# quantum_AnalougeEngine_V5_0.net
KiCad netlist of a schematic drawn in EAGLE
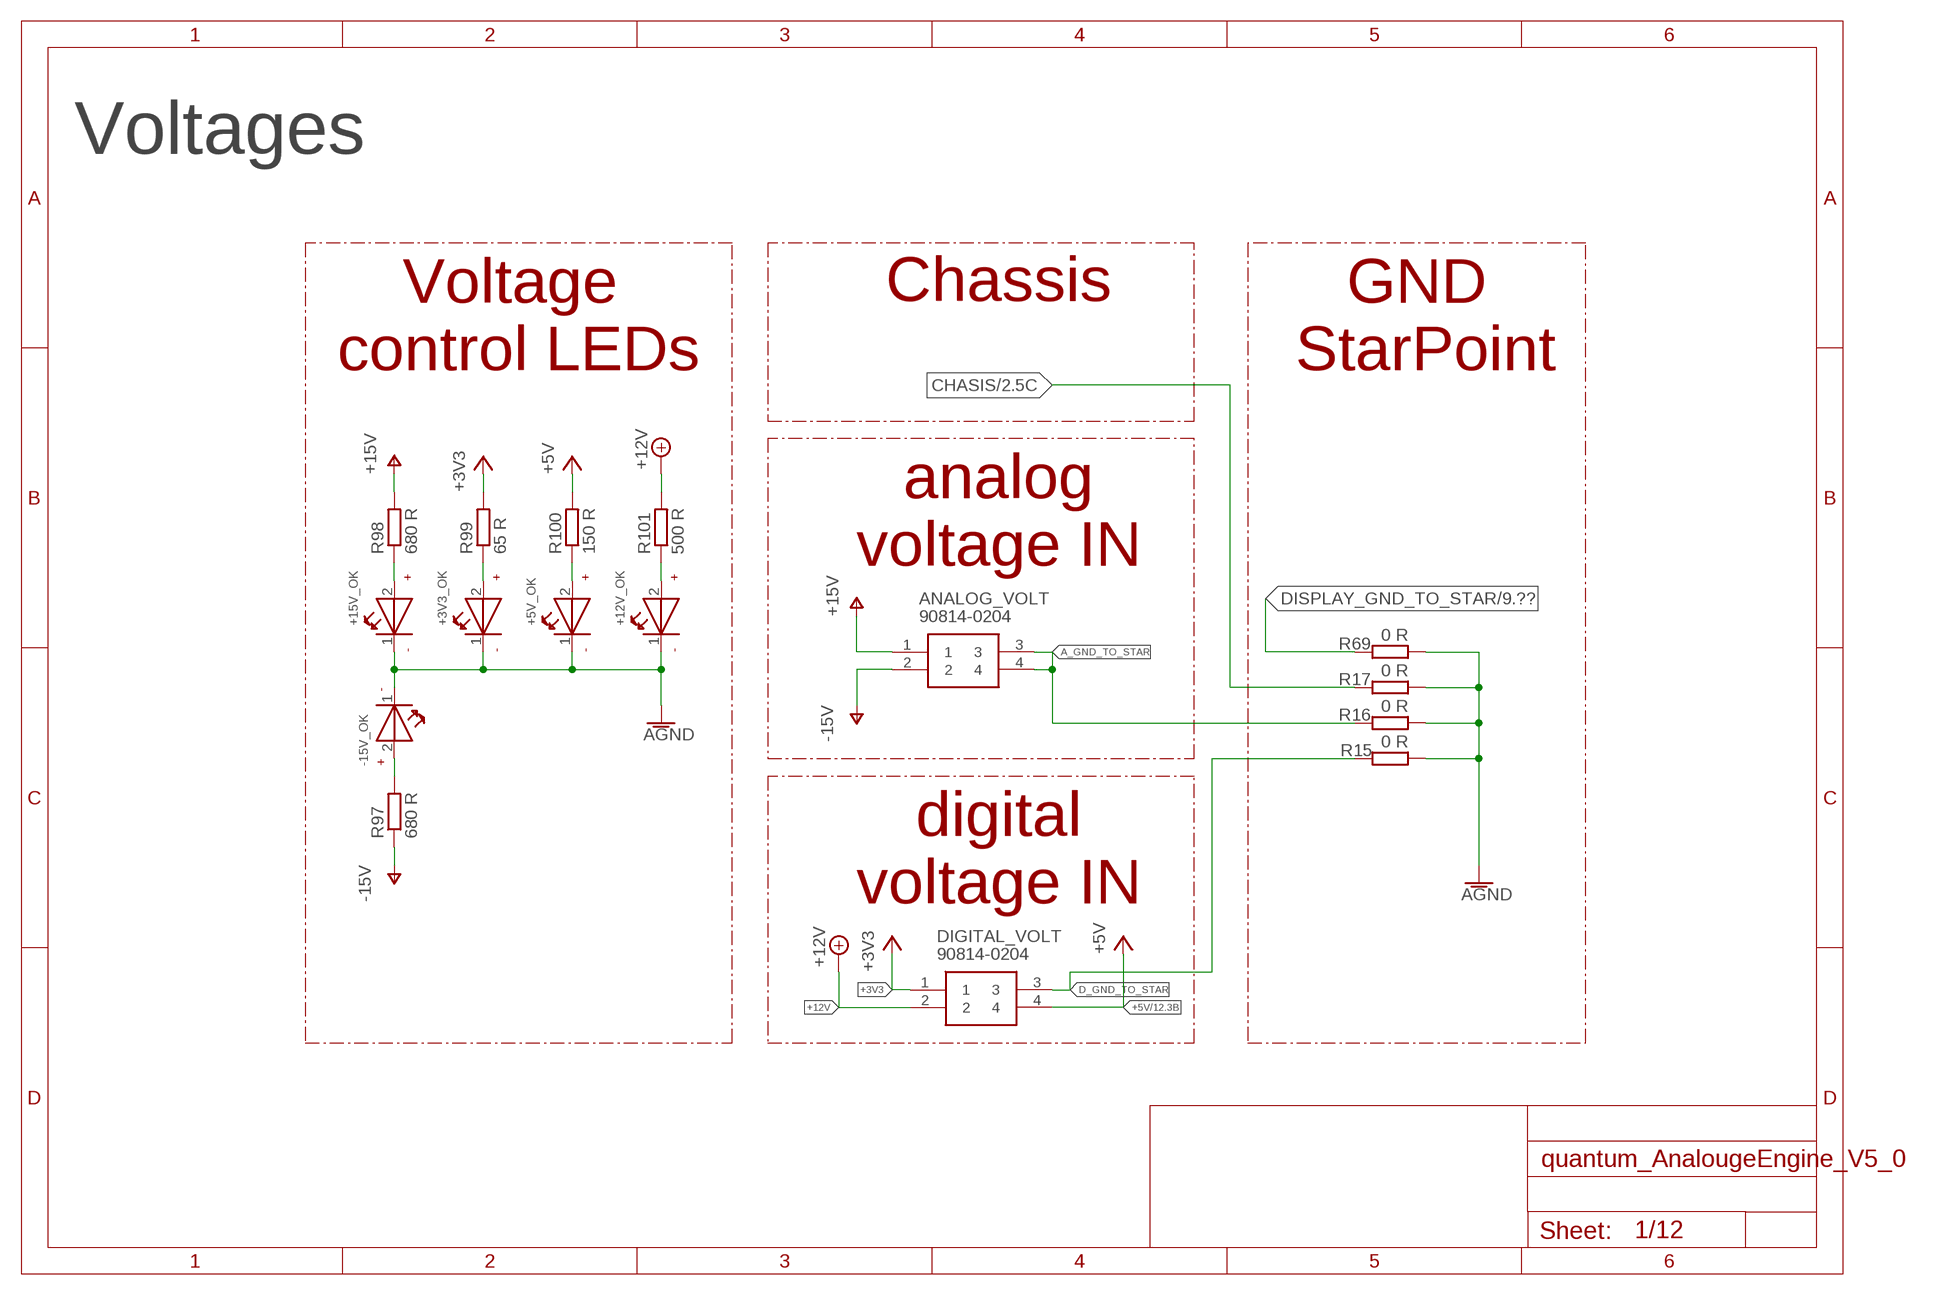
[diagram p0: schematic, sheet 1]
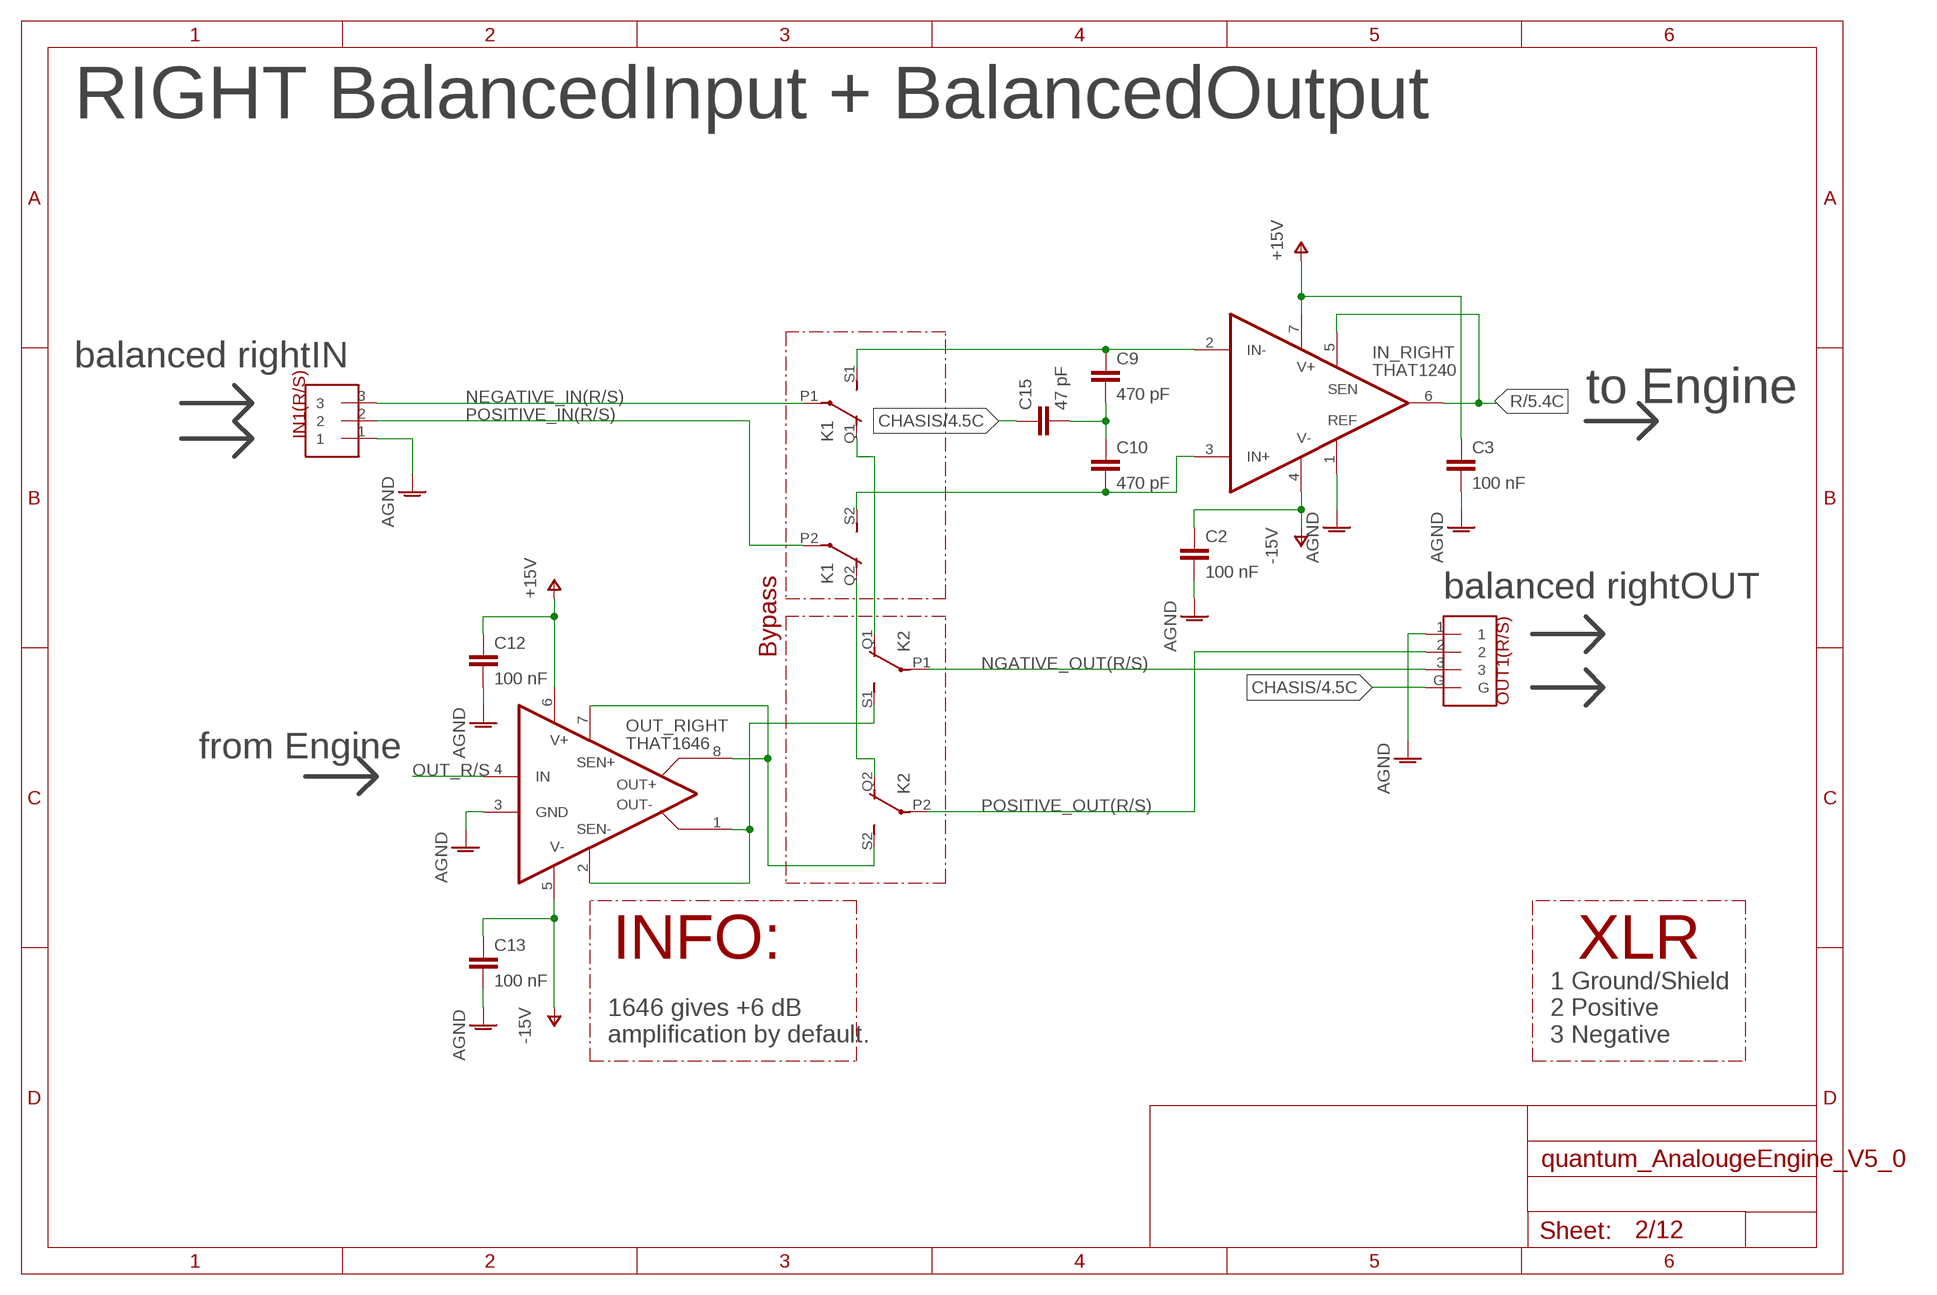
[diagram p1: schematic, sheet 2]
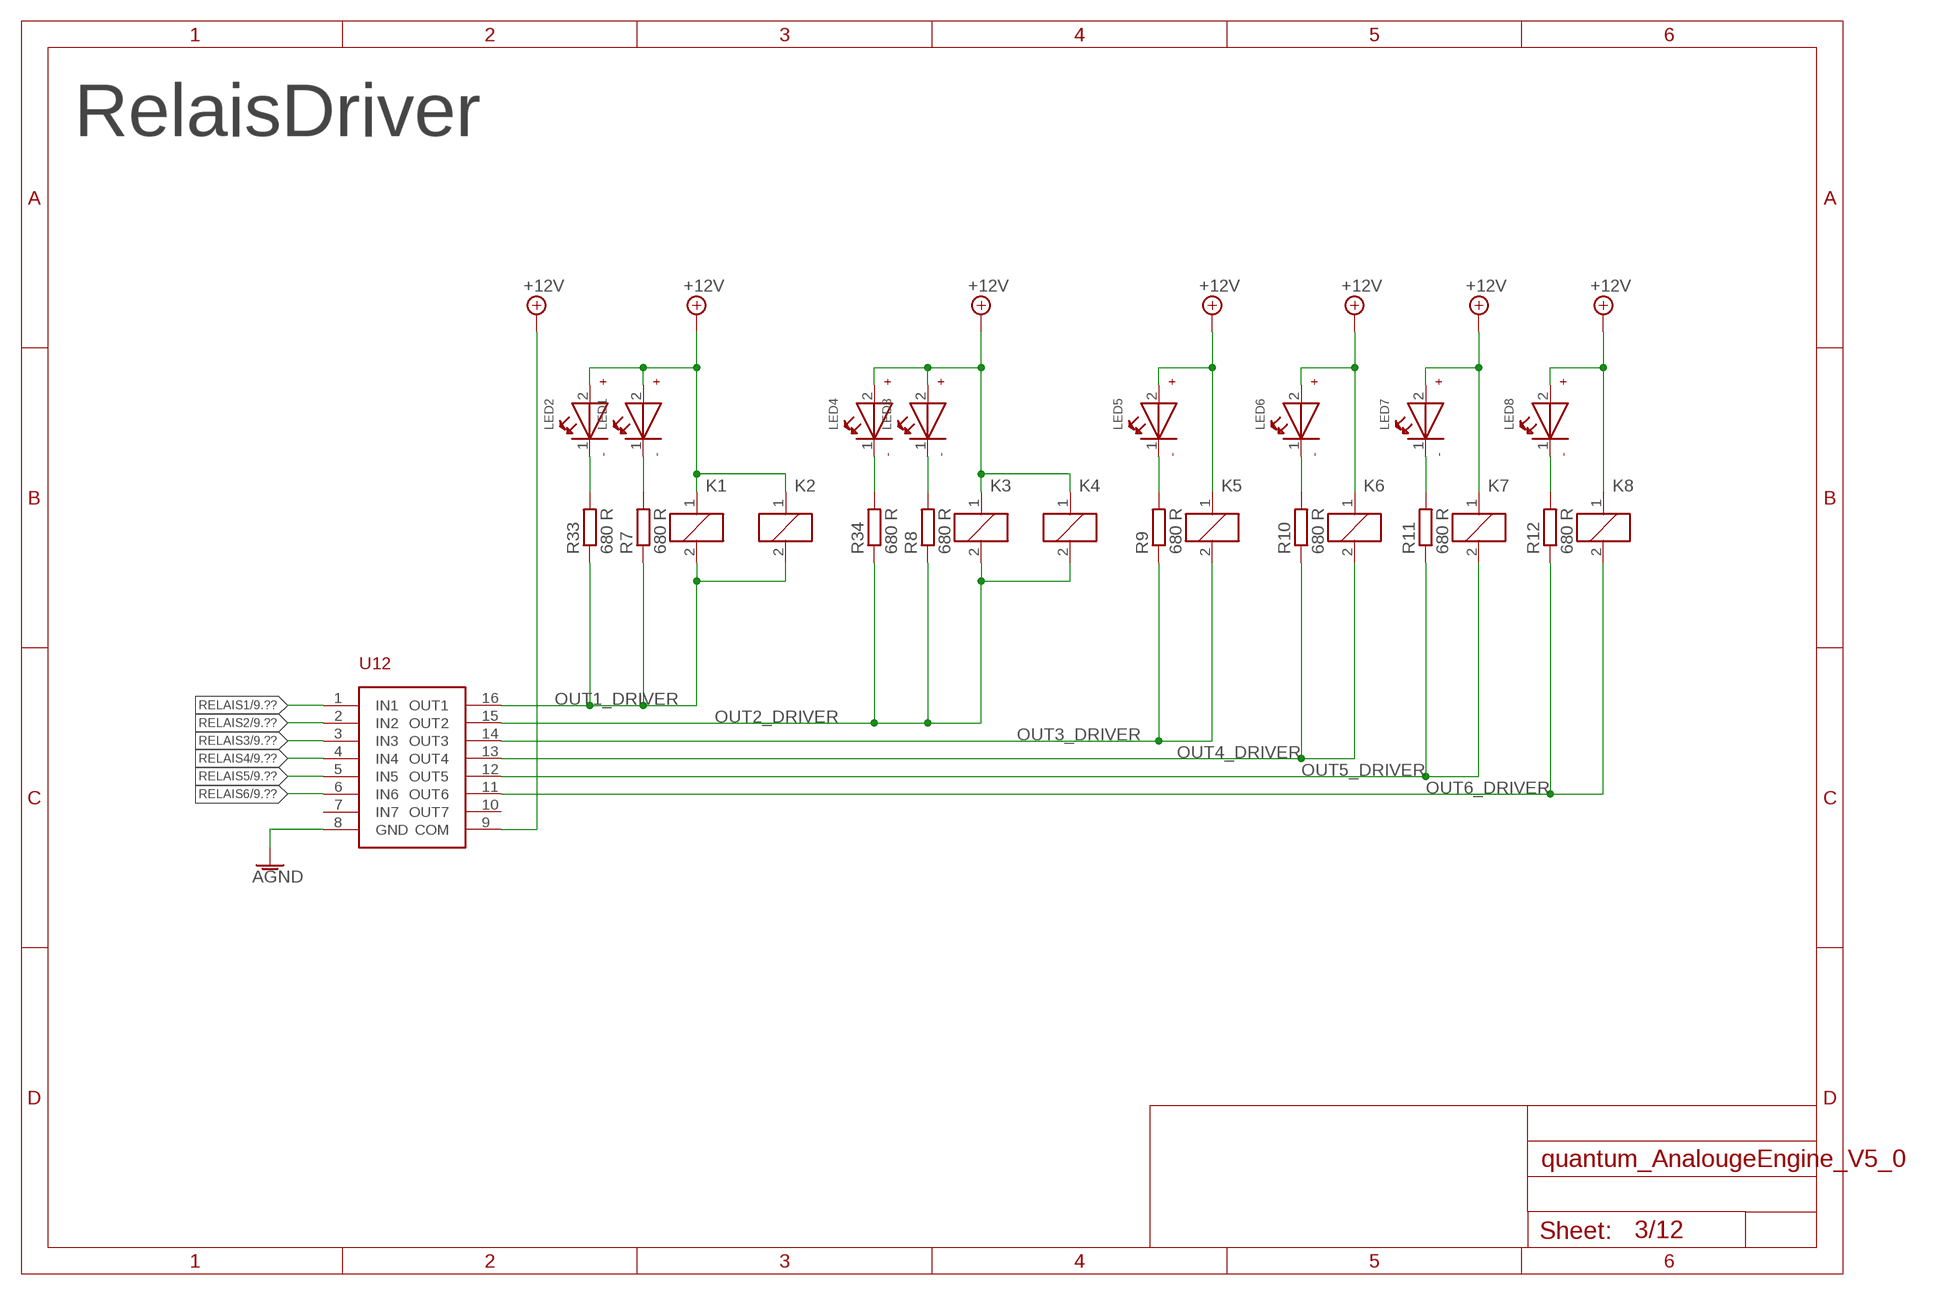
[diagram p2: schematic, sheet 3]
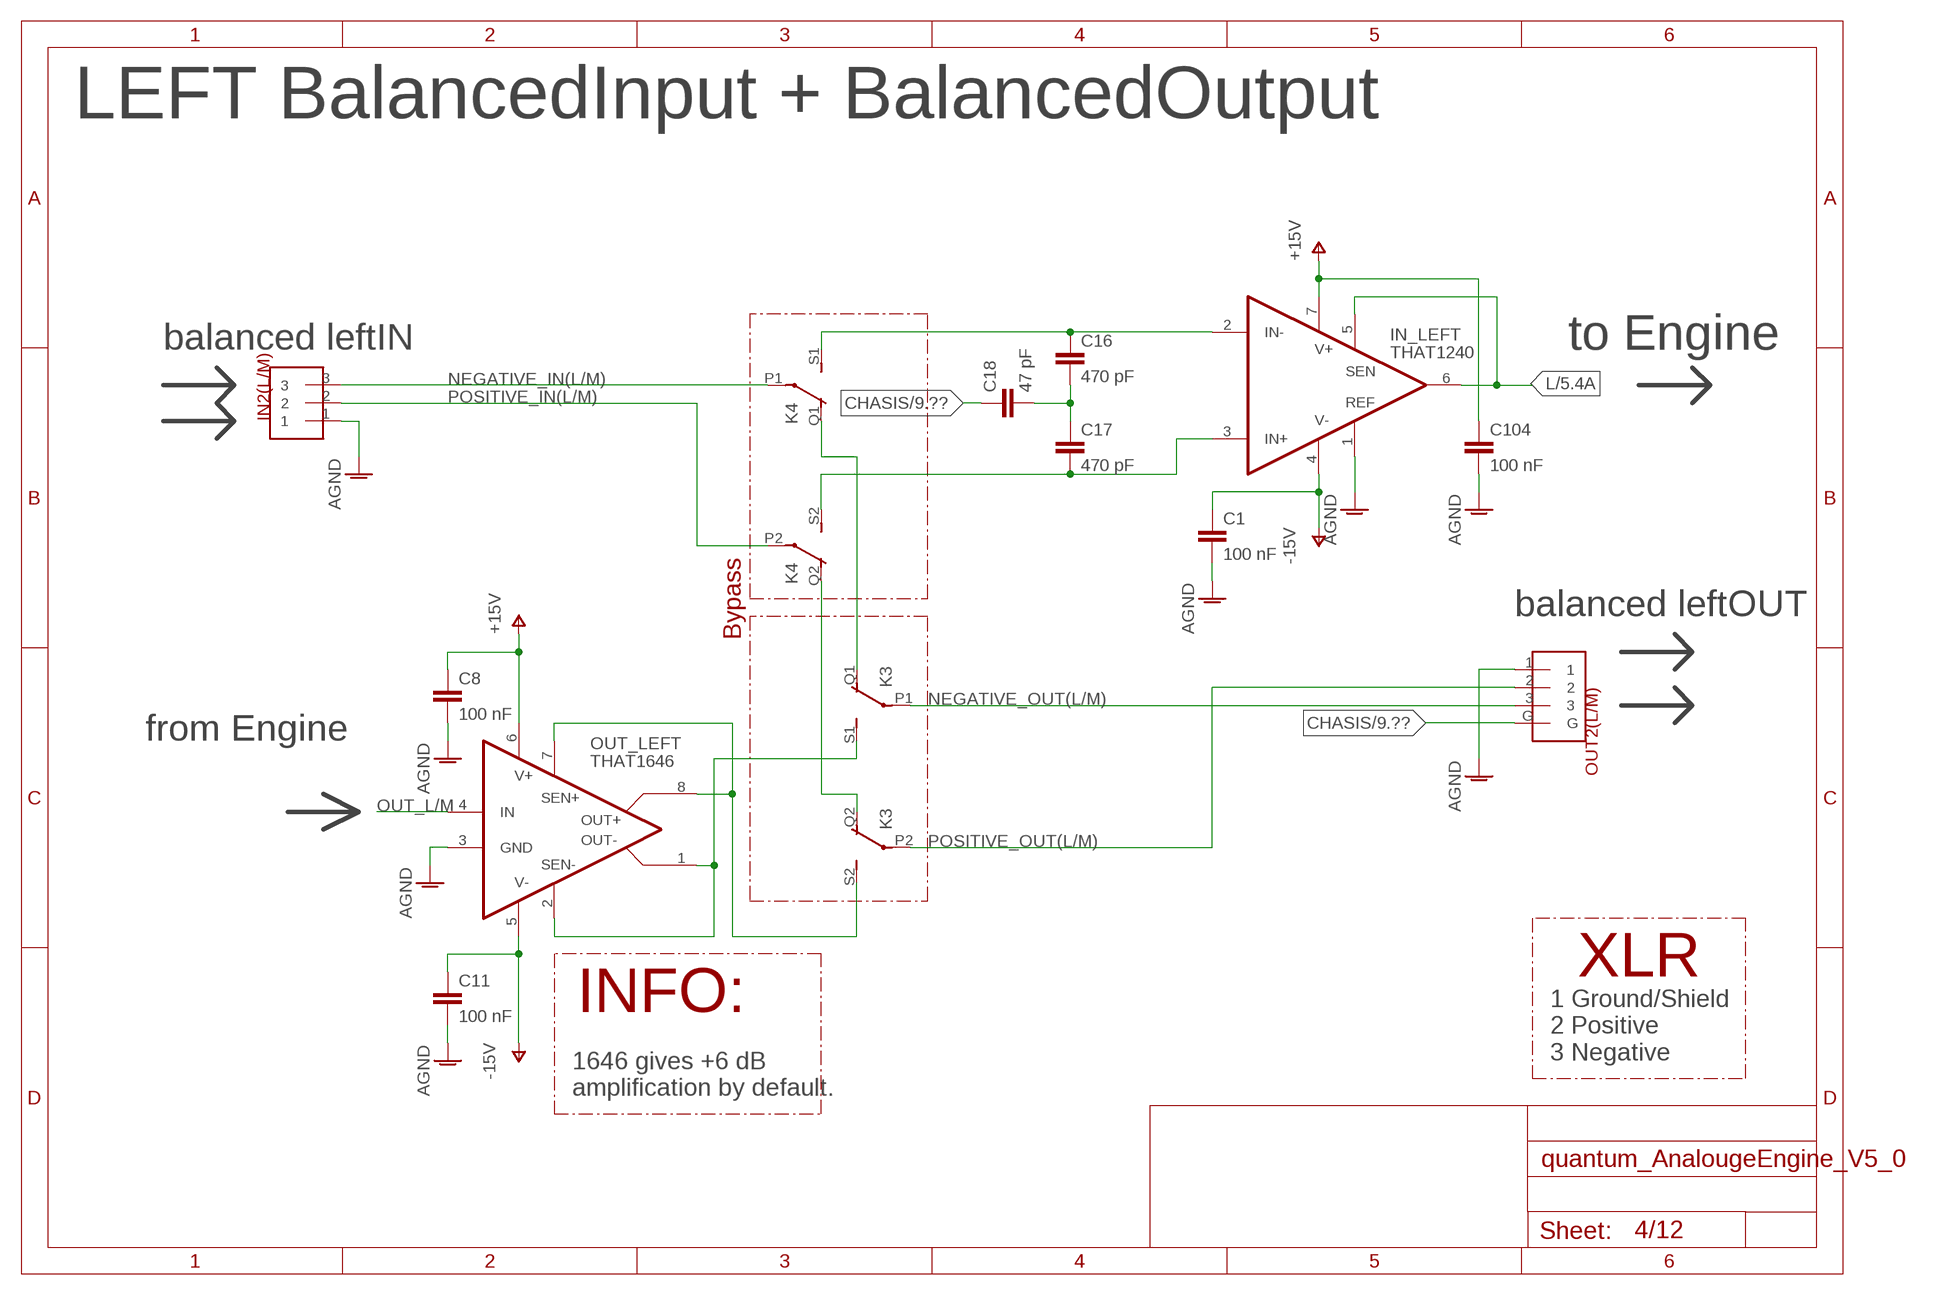
[diagram p3: schematic, sheet 4]
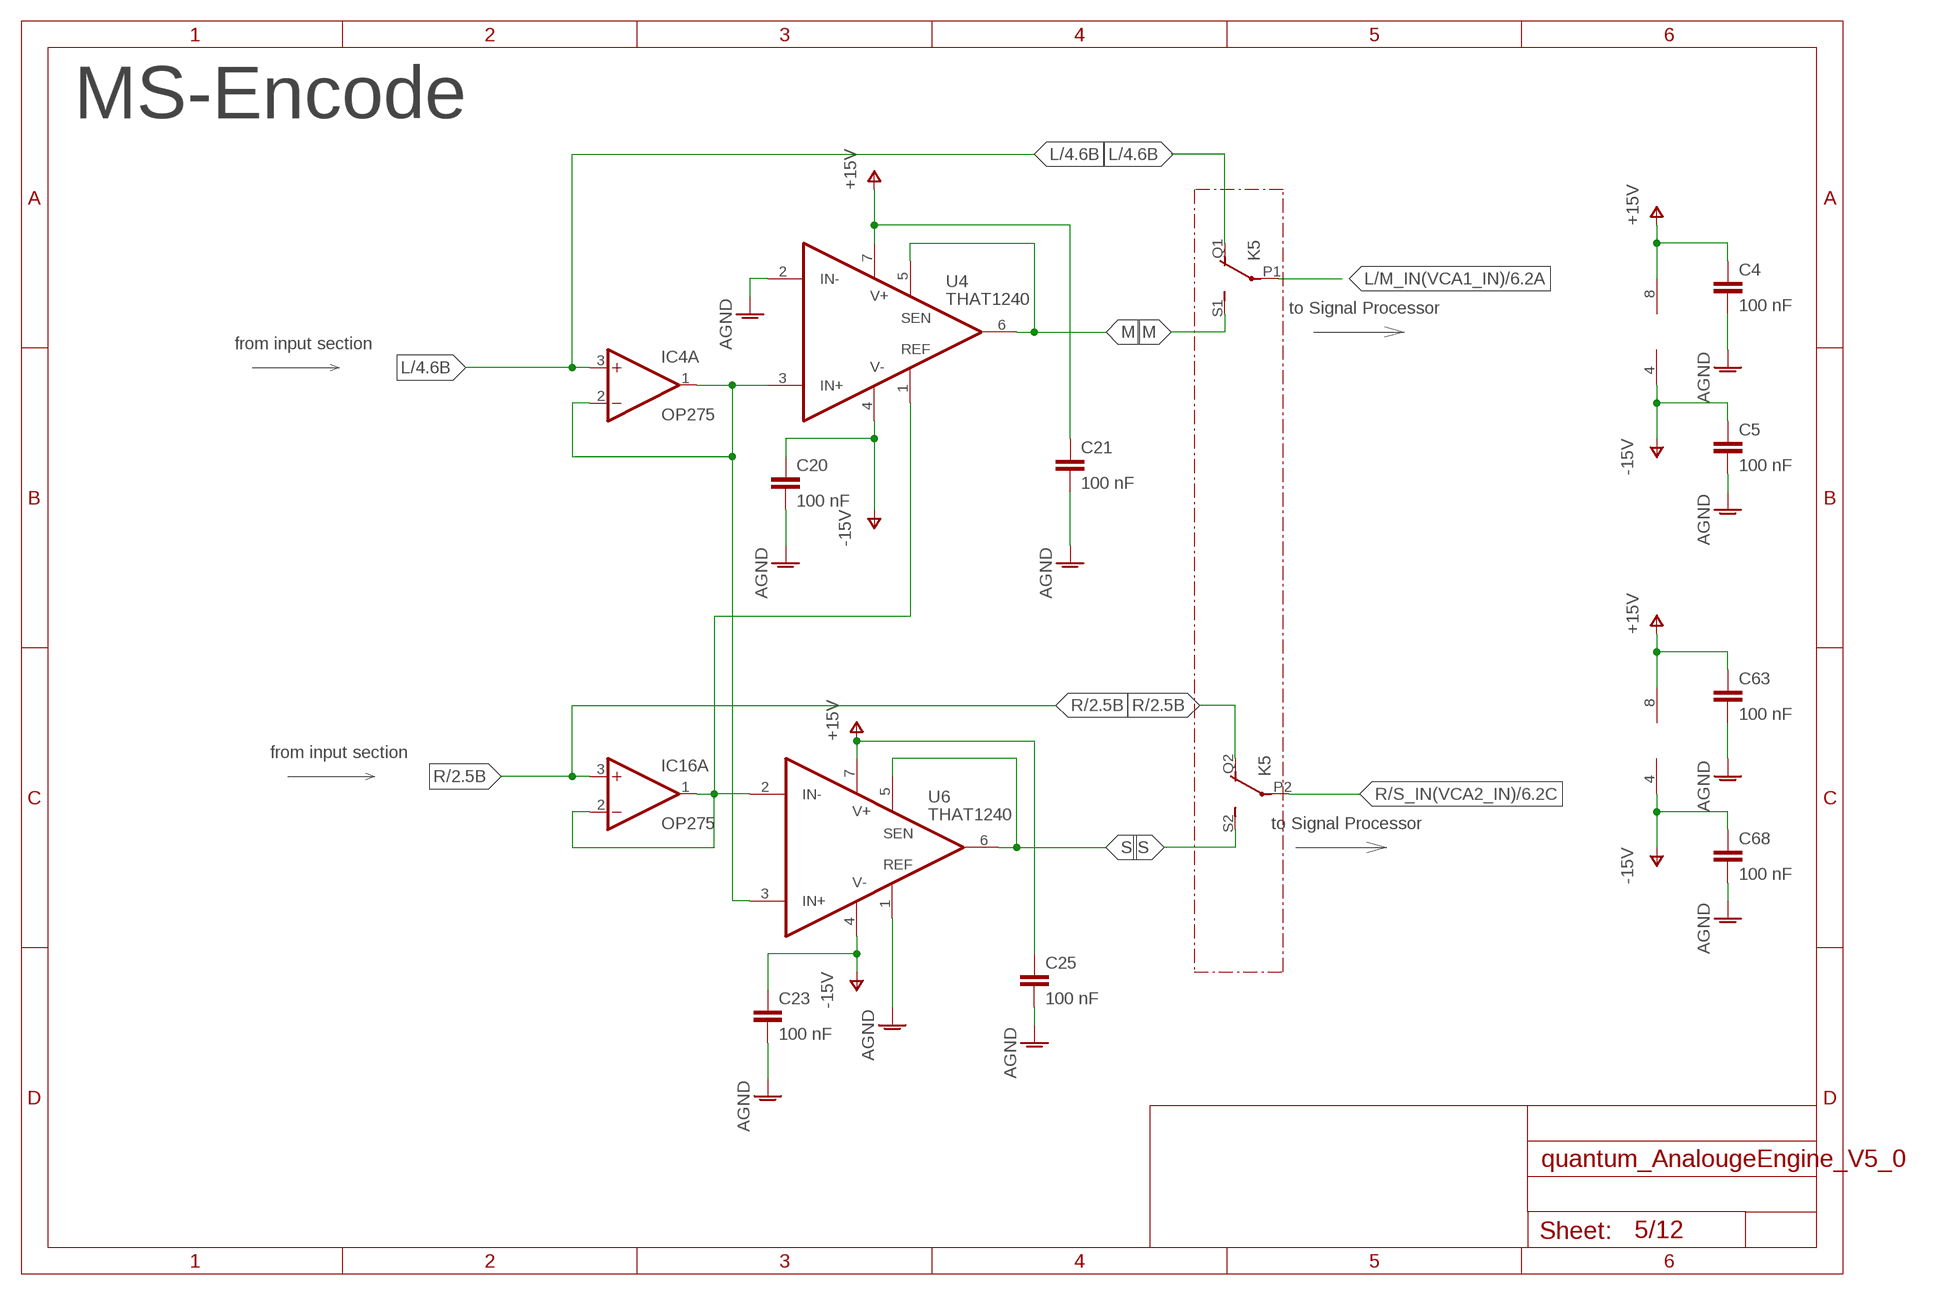
[diagram p4: schematic, sheet 5]
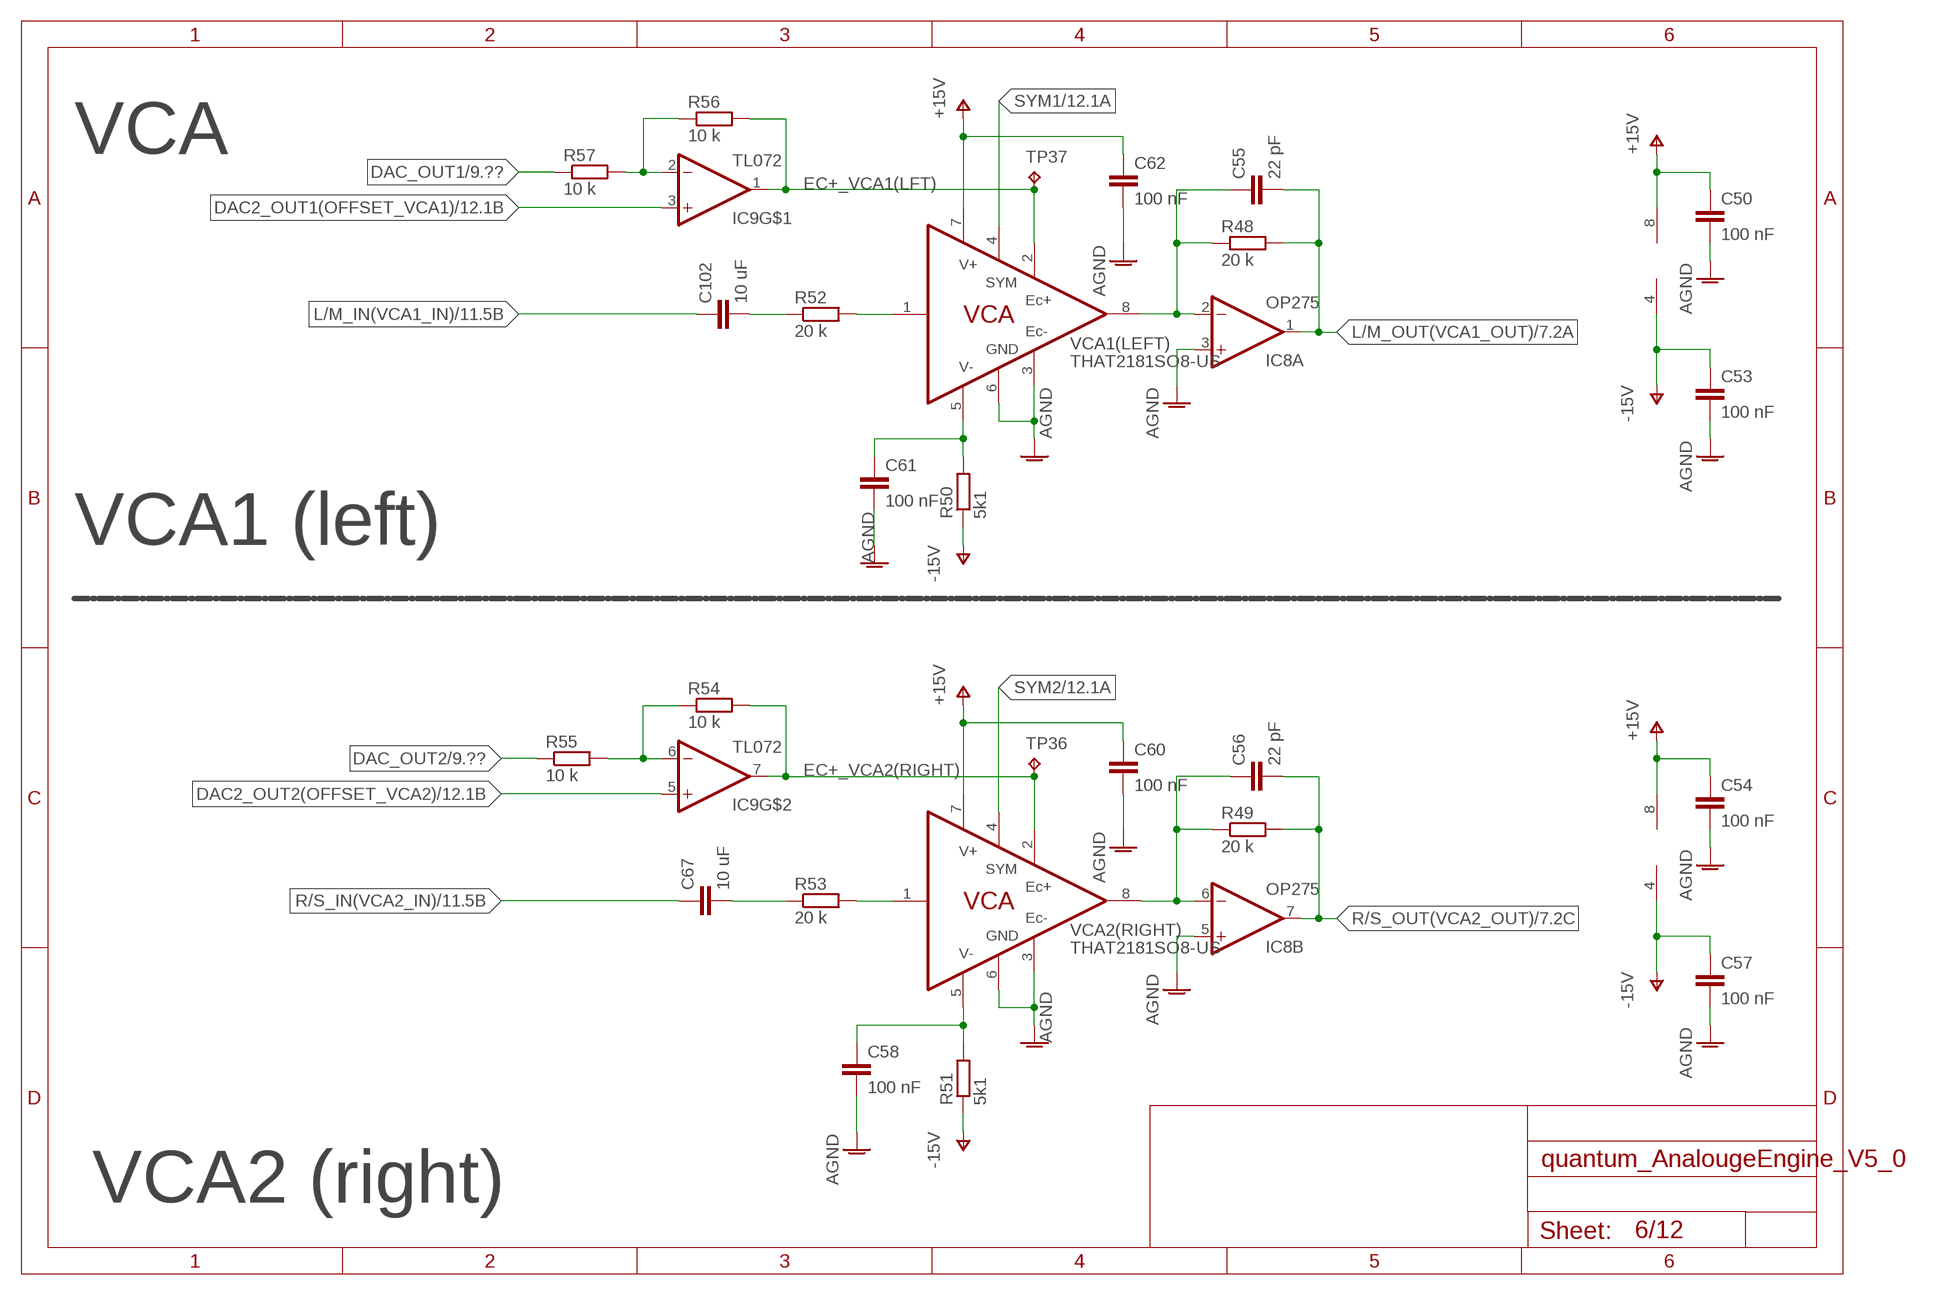
[diagram p5: schematic, sheet 6]
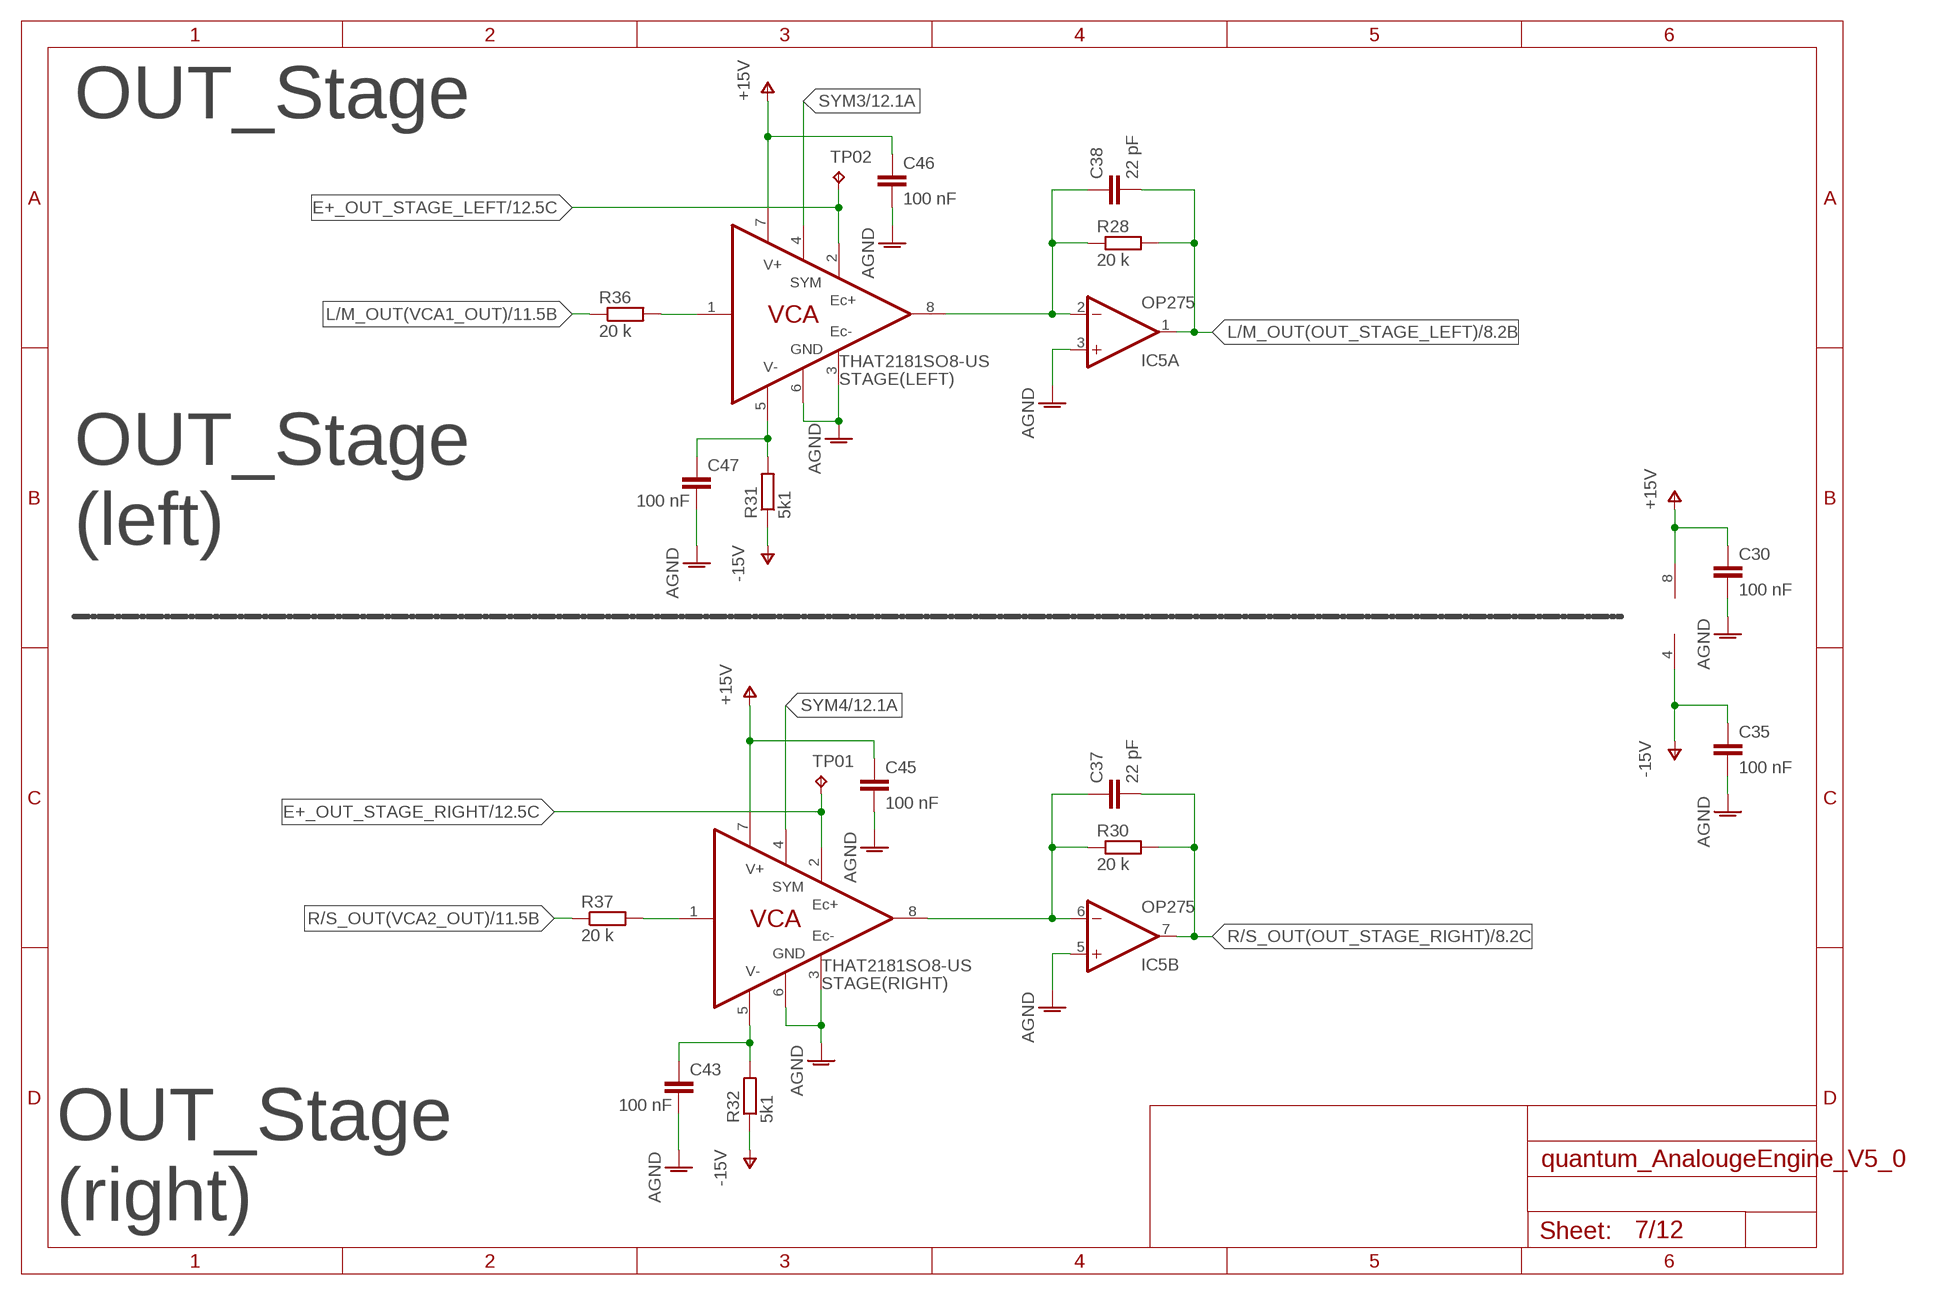
[diagram p6: schematic, sheet 7]
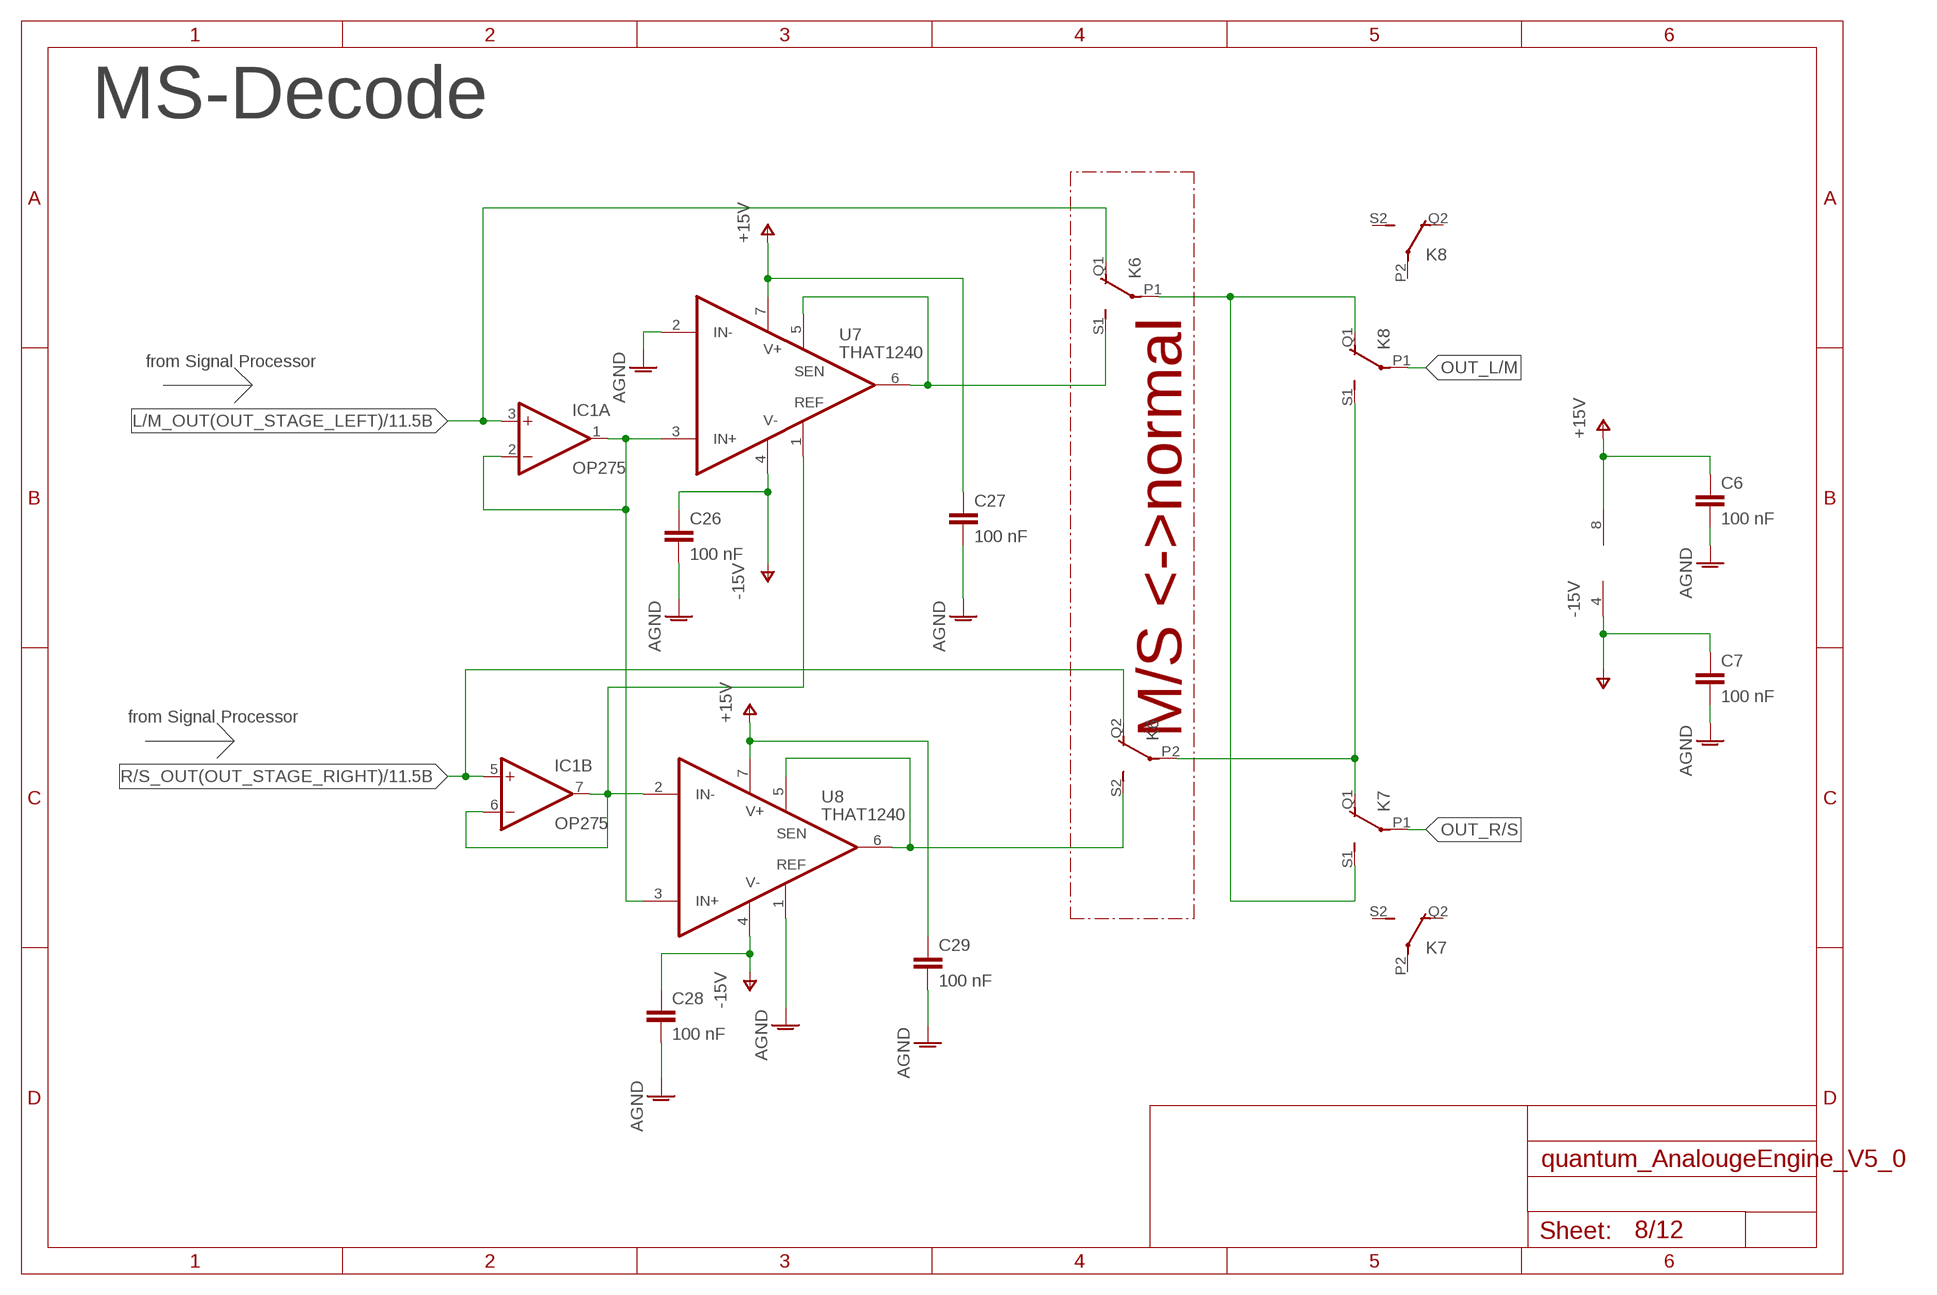
[diagram p7: schematic, sheet 8]
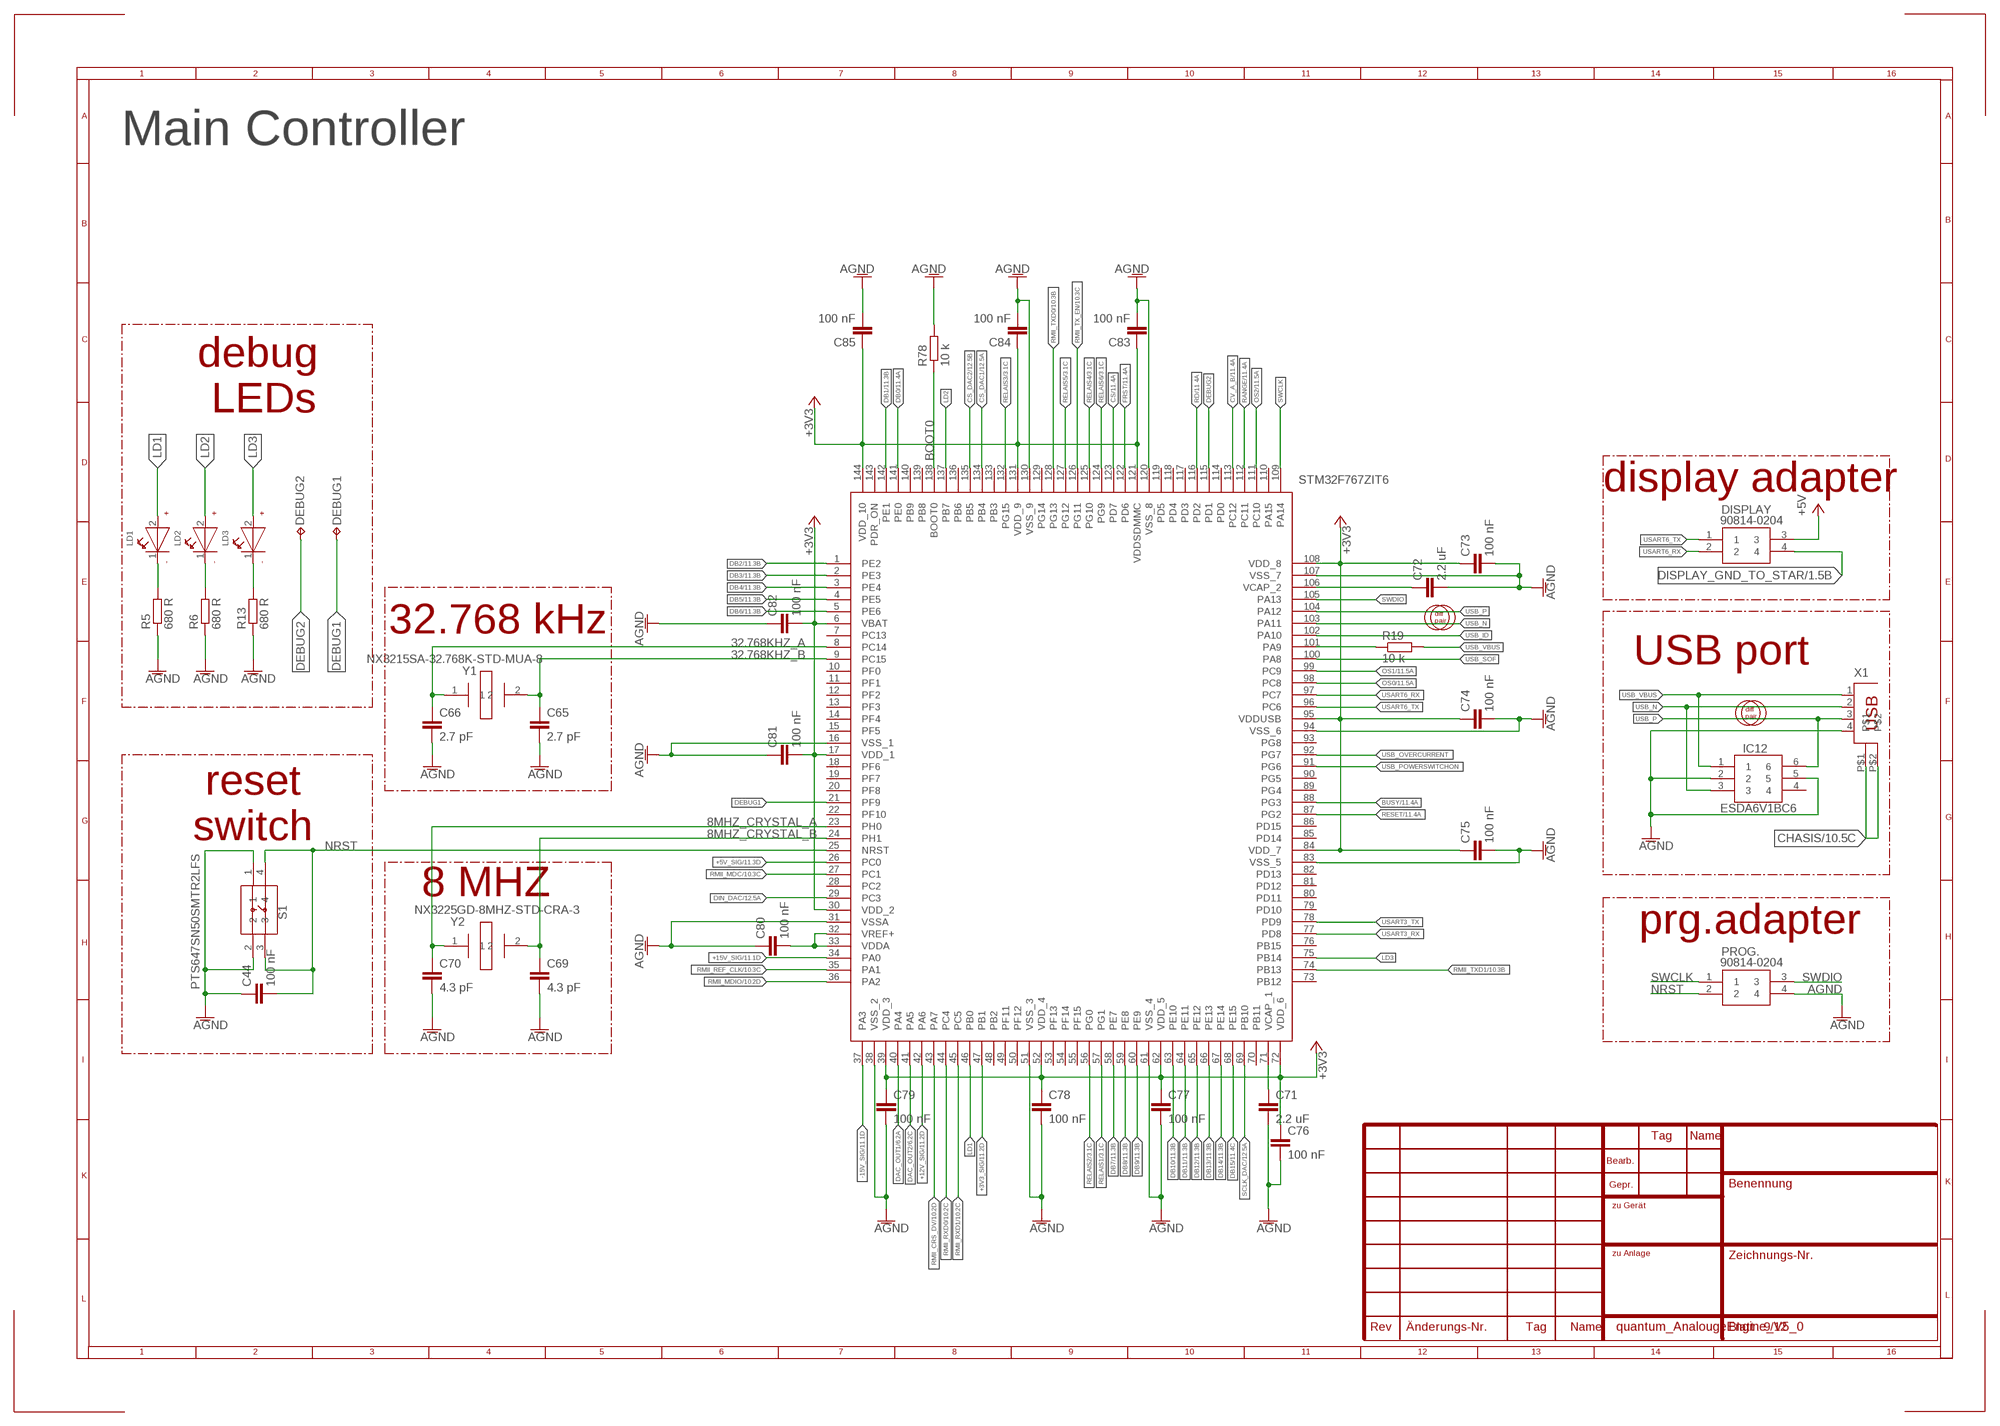
[diagram p8: schematic, sheet 9]
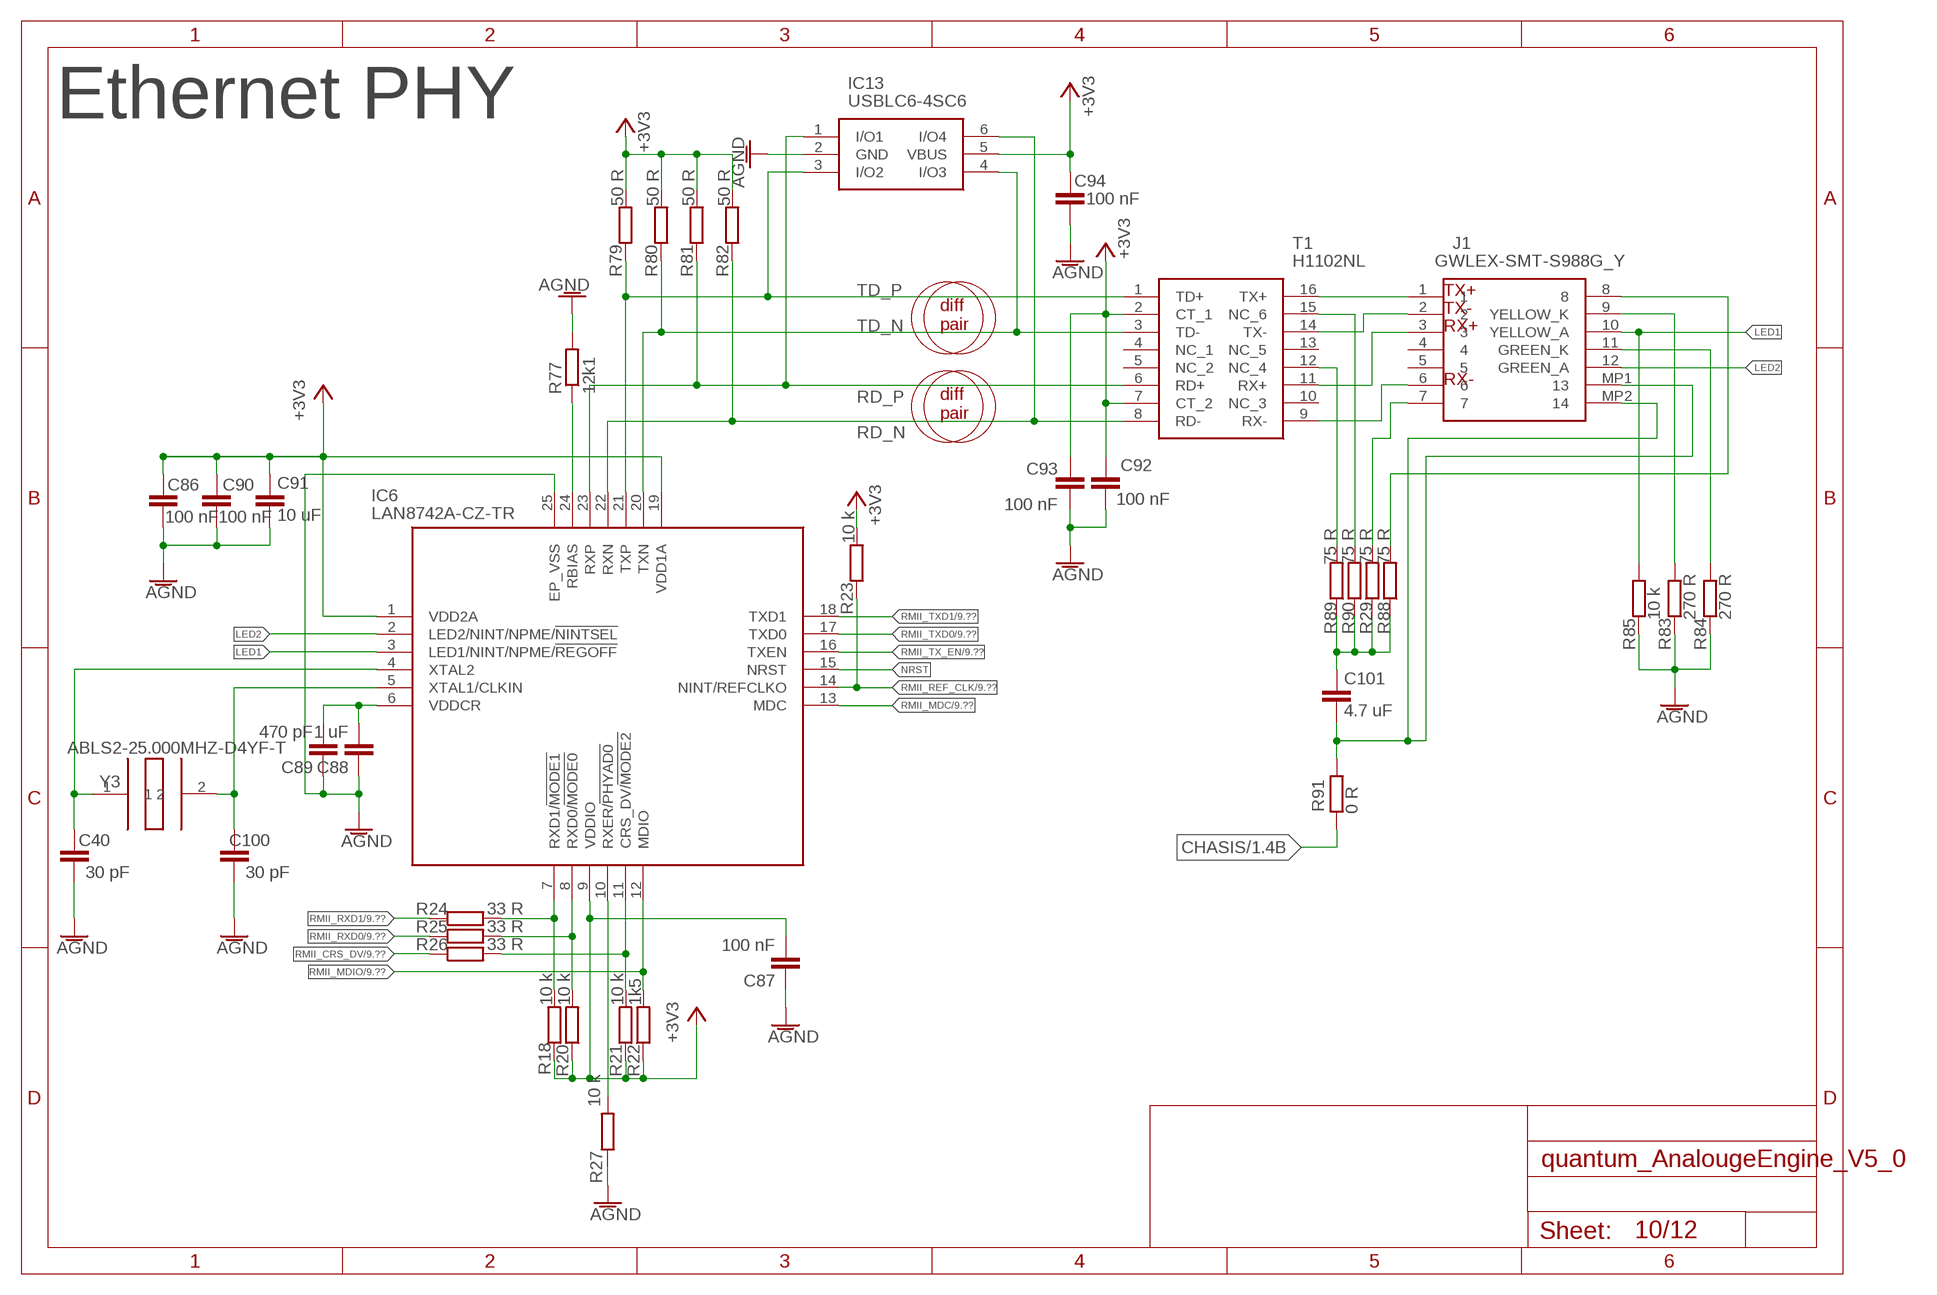
[diagram p9: schematic, sheet 10]
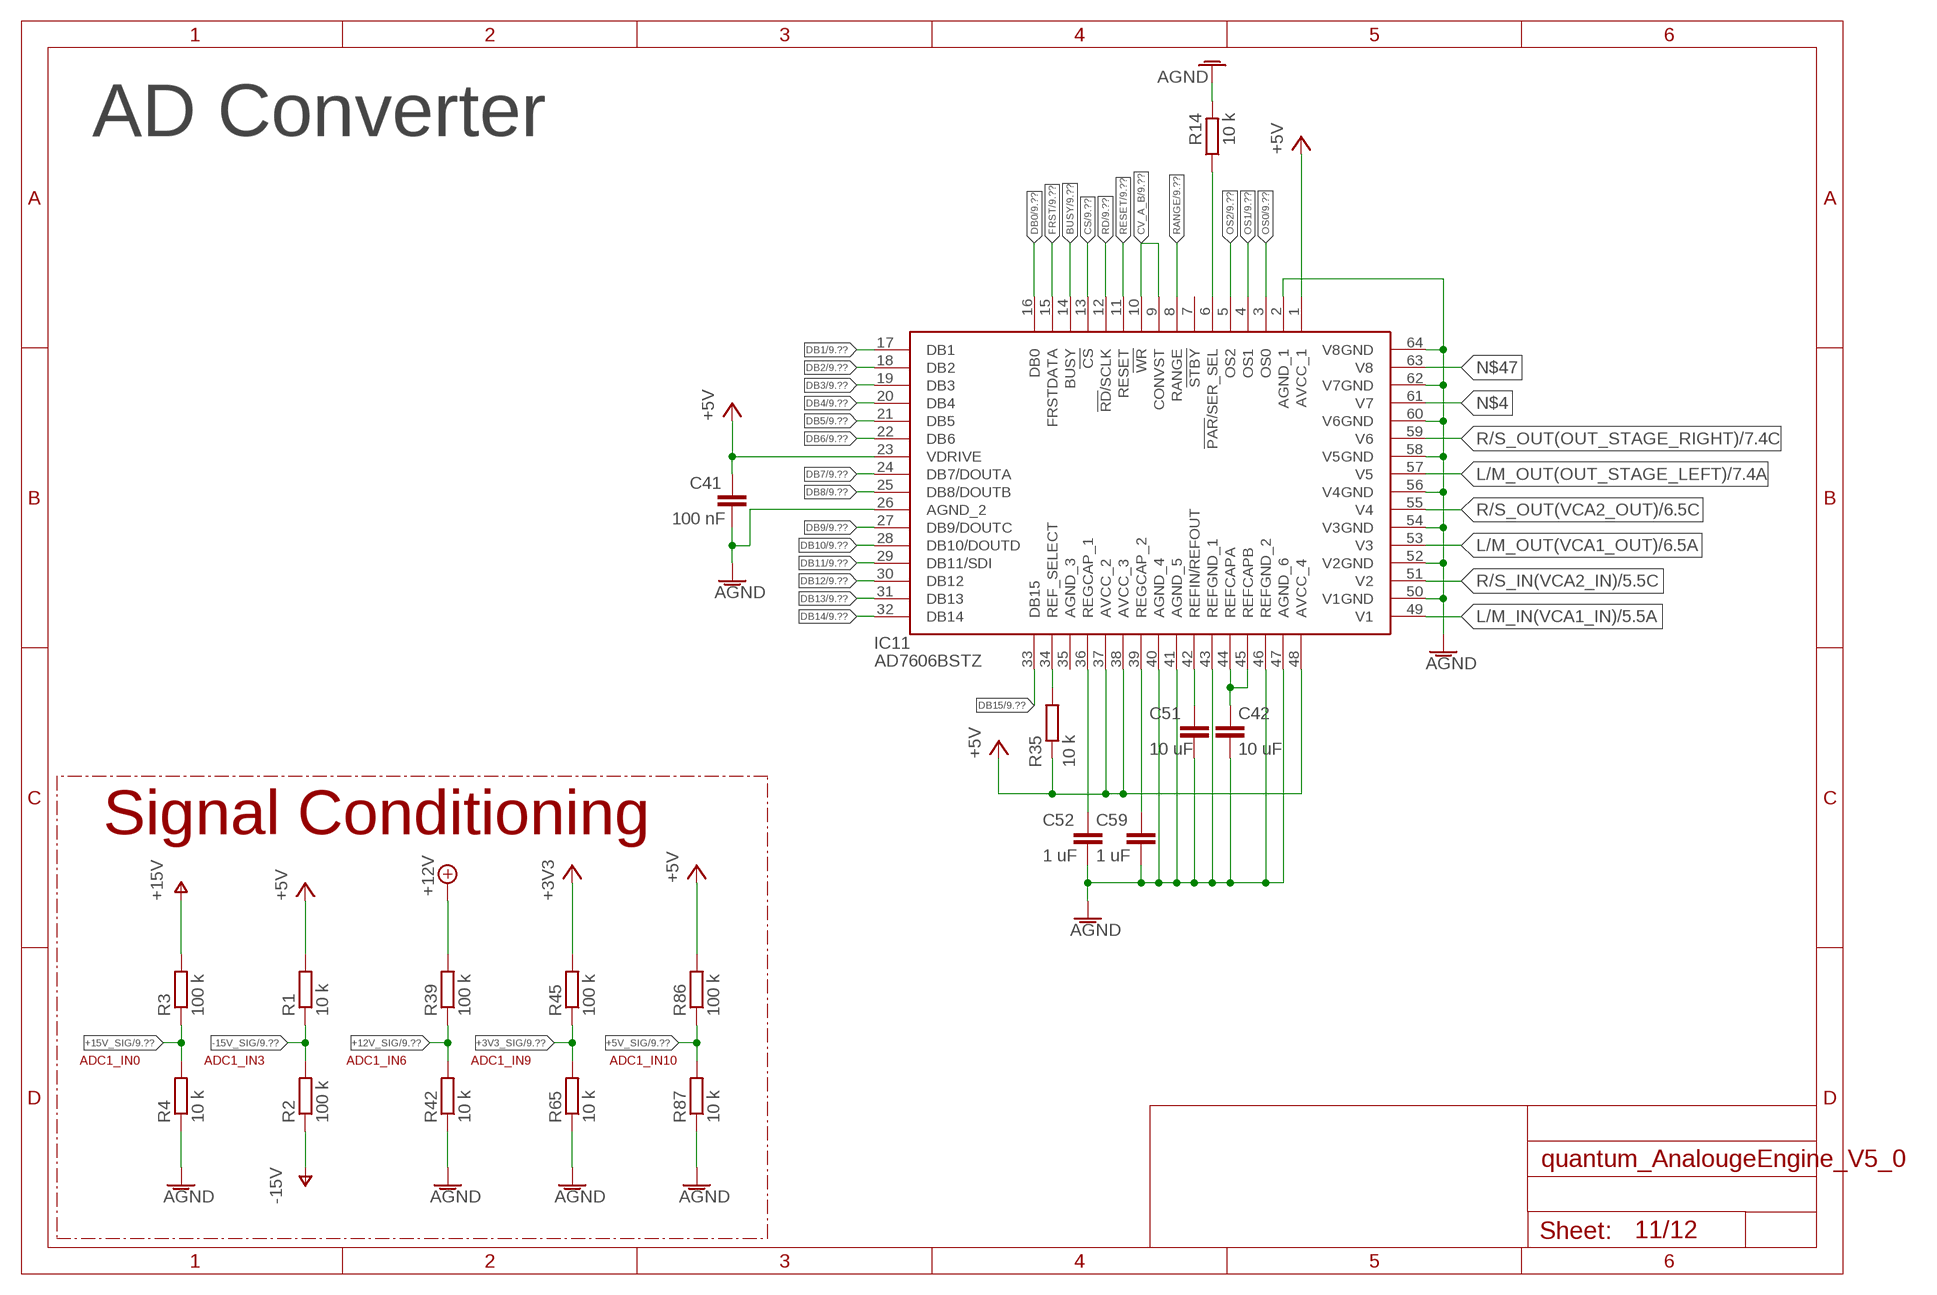
[diagram p10: schematic, sheet 11]
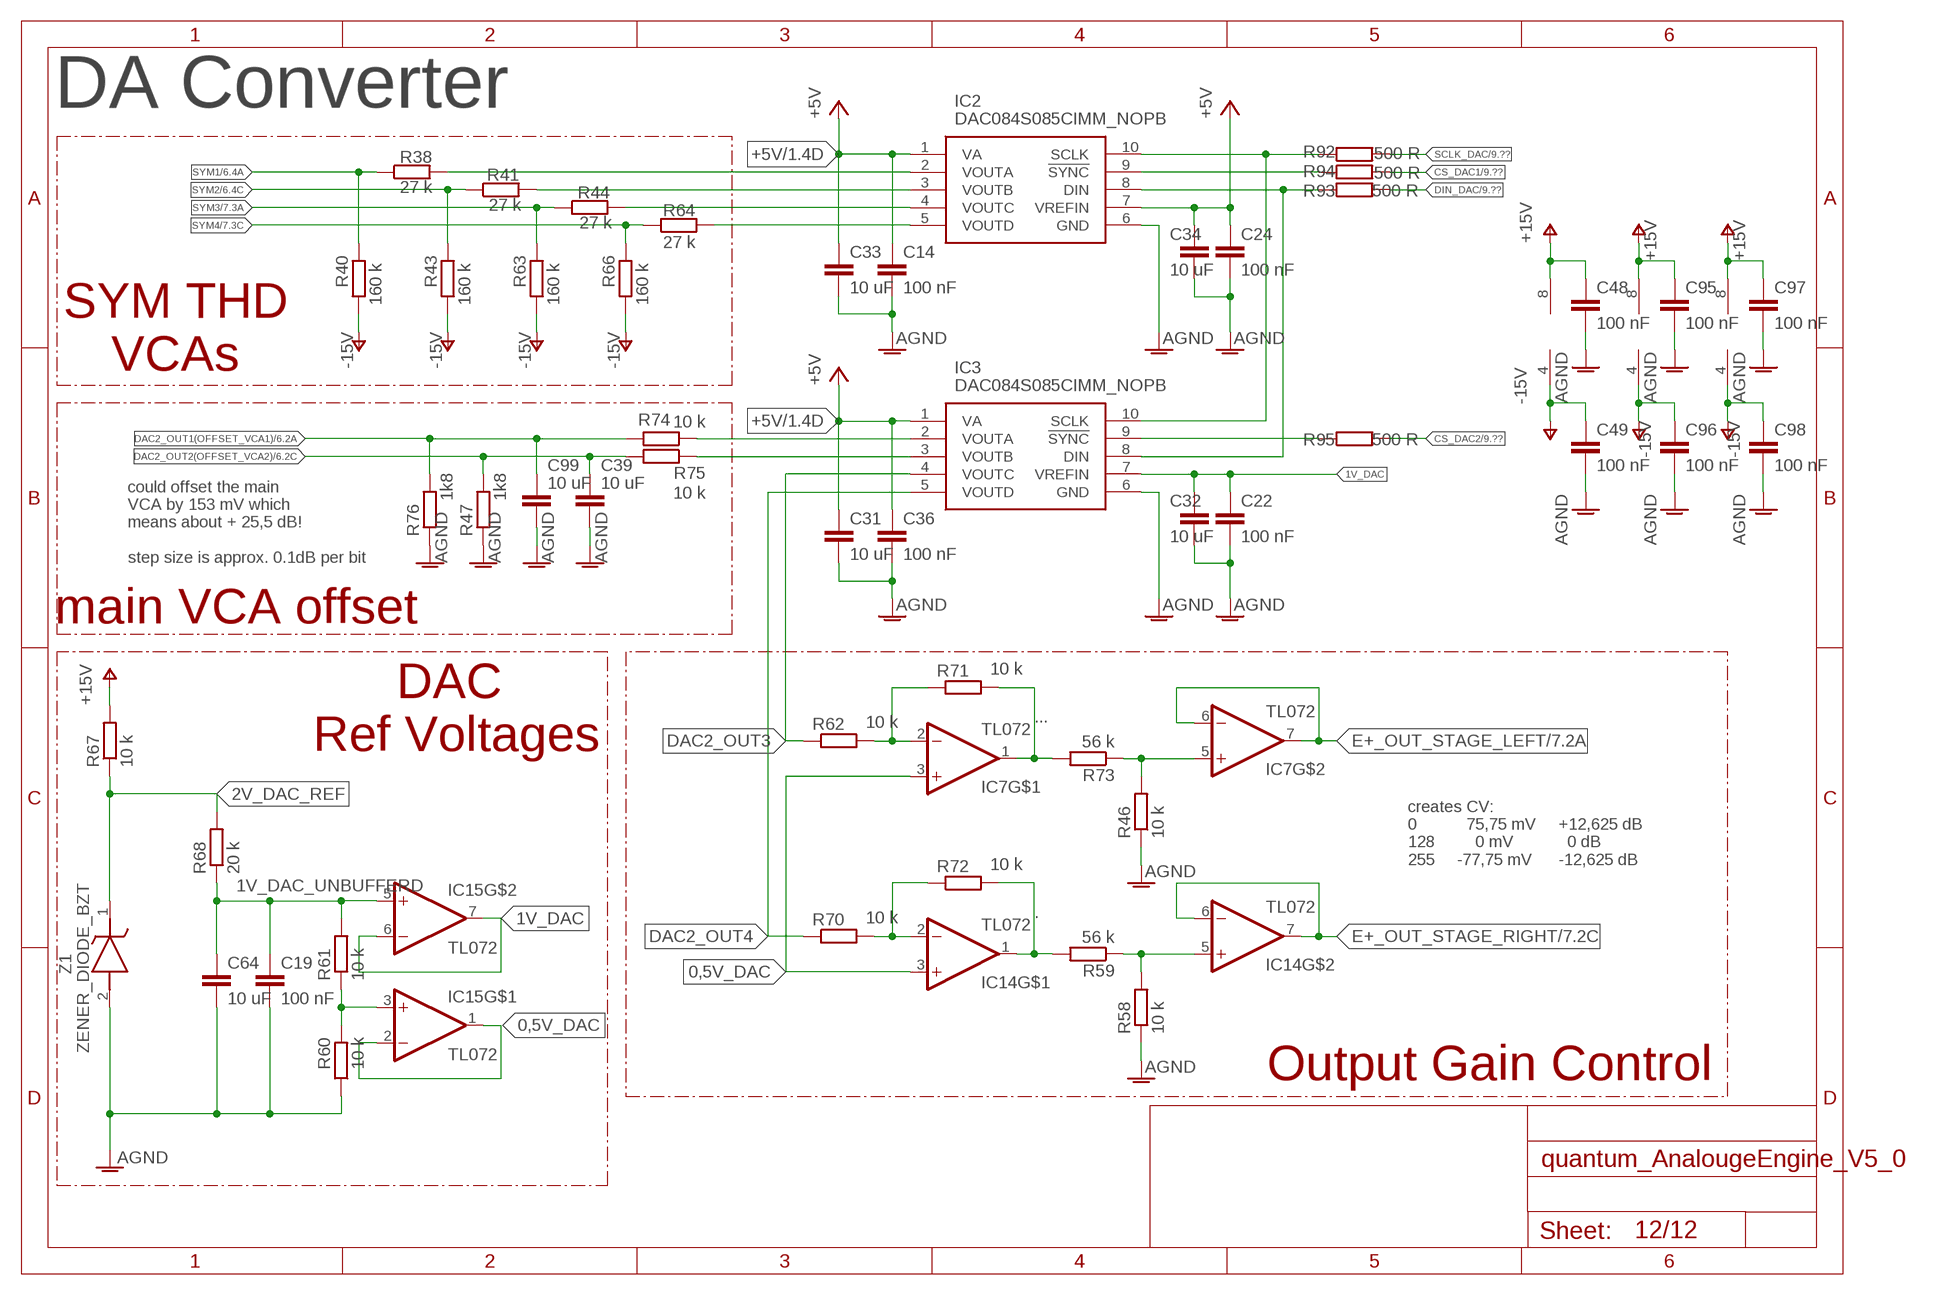
[diagram p11: schematic, sheet 12]

(export (version "E")
  (design (tool "Eeschema 10.0.6"))
  (components
    (comp (ref "C1")
      (value "100 nF")
      (footprint "eagle-import:C0603")
      (libsource (lib "eagle-import") (part "CAPACITOR_0603"))
    )
    (comp (ref "C8")
      (value "100 nF")
      (footprint "eagle-import:C0603")
      (libsource (lib "eagle-import") (part "CAPACITOR_0603"))
    )
    (comp (ref "C11")
      (value "100 nF")
      (footprint "eagle-import:C0603")
      (libsource (lib "eagle-import") (part "CAPACITOR_0603"))
    )
    (comp (ref "C16")
      (value "470 pF")
      (footprint "eagle-import:C0603")
      (libsource (lib "eagle-import") (part "CAPACITOR_0603"))
    )
    (comp (ref "C17")
      (value "470 pF")
      (footprint "eagle-import:C0603")
      (libsource (lib "eagle-import") (part "CAPACITOR_0603"))
    )
    (comp (ref "C18")
      (value "47 pF")
      (footprint "eagle-import:C0603")
      (libsource (lib "eagle-import") (part "CAPACITOR_0603"))
    )
    (comp (ref "C104")
      (value "100 nF")
      (footprint "eagle-import:C0603")
      (libsource (lib "eagle-import") (part "CAPACITOR_0603"))
    )
    (comp (ref "IN2(L/M)")
      (value "NEUTRIK_NC3FAH")
      (footprint "eagle-import:NEUTRIK_NC3FAH")
      (libsource (lib "eagle-import") (part "NEUTRIK_NC3FAH"))
    )
    (comp (ref "IN_LEFT")
      (value "THAT1240")
      (footprint "eagle-import:SO08")
      (fields (field (name "MOUSER_PART_NUMBER") "887-1240S08-U"))
      (libsource (lib "eagle-import") (part "THAT1240SO8-USO8-U"))
    )
    (comp (ref "K3")
      (value "Relay")
      (footprint "eagle-import:351")
      (libsource (lib "eagle-import") (part "RELAY_EE2-5NU"))
    )
    (comp (ref "K4")
      (value "Relay")
      (footprint "eagle-import:351")
      (libsource (lib "eagle-import") (part "RELAY_EE2-5NU"))
    )
    (comp (ref "OUT2(L/M)")
      (value "NEUTRIK_NC3MAH")
      (footprint "eagle-import:NEUTRIK_NC3MAH")
      (libsource (lib "eagle-import") (part "NEUTRIK_NC3MAH"))
    )
    (comp (ref "OUT_LEFT")
      (value "THAT1646")
      (footprint "eagle-import:SO08")
      (fields (field (name "MOUSER_PART_NUMBER") "887-1646S08-U"))
      (libsource (lib "eagle-import") (part "THAT1646SO8-USO8-U"))
    )
    (comp (ref "C40")
      (value "30 pF")
      (footprint "eagle-import:C0603")
      (libsource (lib "eagle-import") (part "CAPACITOR_0603"))
    )
    (comp (ref "C86")
      (value "100 nF")
      (footprint "eagle-import:C0603")
      (libsource (lib "eagle-import") (part "CAPACITOR_0603"))
    )
    (comp (ref "C87")
      (value "100 nF")
      (footprint "eagle-import:C0603")
      (libsource (lib "eagle-import") (part "CAPACITOR_0603"))
    )
    (comp (ref "C88")
      (value "1 uF")
      (footprint "eagle-import:C0603")
      (libsource (lib "eagle-import") (part "CAPACITOR_0603"))
    )
    (comp (ref "C89")
      (value "470 pF")
      (footprint "eagle-import:C0603")
      (libsource (lib "eagle-import") (part "CAPACITOR_0603"))
    )
    (comp (ref "C90")
      (value "100 nF")
      (footprint "eagle-import:C0603")
      (libsource (lib "eagle-import") (part "CAPACITOR_0603"))
    )
    (comp (ref "C91")
      (value "10 uF")
      (footprint "eagle-import:C1206")
      (libsource (lib "eagle-import") (part "CAPACITOR_1206"))
    )
    (comp (ref "C92")
      (value "100 nF")
      (footprint "eagle-import:C0603")
      (libsource (lib "eagle-import") (part "CAPACITOR_0603"))
    )
    (comp (ref "C93")
      (value "100 nF")
      (footprint "eagle-import:C0603")
      (libsource (lib "eagle-import") (part "CAPACITOR_0603"))
    )
    (comp (ref "C94")
      (value "100 nF")
      (footprint "eagle-import:C0603")
      (libsource (lib "eagle-import") (part "CAPACITOR_0603"))
    )
    (comp (ref "C100")
      (value "30 pF")
      (footprint "eagle-import:C0603")
      (libsource (lib "eagle-import") (part "CAPACITOR_0603"))
    )
    (comp (ref "C101")
      (value "4.7 uF")
      (footprint "eagle-import:C1206")
      (libsource (lib "eagle-import") (part "CAPACITOR_1206"))
    )
    (comp (ref "IC6")
      (value "LAN8742A-CZ-TR")
      (footprint "eagle-import:QFN50P400X400X100-25N")
      (fields (field (name "MOUSER_PART_NUMBER") "579-LAN8742A-CZ-TR"))
      (libsource (lib "eagle-import") (part "LAN8742A-CZ-TR"))
    )
    (comp (ref "IC13")
      (value "USBLC6-4SC6")
      (footprint "eagle-import:SOT95P280X145-6N")
      (fields (field (name "MOUSER_PART_NUMBER") "511-USBLC6-4SC6"))
      (libsource (lib "eagle-import") (part "USBLC6-4SC6"))
    )
    (comp (ref "J1")
      (value "GWLEX-SMT-S988G_Y")
      (footprint "eagle-import:GWLEXSMTS988GY")
      (fields
        (field (name "MANUFACTURER_PART_NUMBER") "GWLEX-SMT-S988G/Y")
        (field (name "MOUSER_PART_NUMBER") "806-GWLEX-SMT-S988GY")
      )
      (libsource (lib "eagle-import") (part "GWLEX-SMT-S988G_Y"))
    )
    (comp (ref "R18")
      (value "10 k")
      (footprint "eagle-import:R0603")
      (libsource (lib "eagle-import") (part "RESISTOR_0603"))
    )
    (comp (ref "R20")
      (value "10 k")
      (footprint "eagle-import:R0603")
      (libsource (lib "eagle-import") (part "RESISTOR_0603"))
    )
    (comp (ref "R21")
      (value "10 k")
      (footprint "eagle-import:R0603")
      (libsource (lib "eagle-import") (part "RESISTOR_0603"))
    )
    (comp (ref "R22")
      (value "1k5")
      (footprint "eagle-import:R0603")
      (libsource (lib "eagle-import") (part "RESISTOR_0603"))
    )
    (comp (ref "R23")
      (value "10 k")
      (footprint "eagle-import:R0603")
      (libsource (lib "eagle-import") (part "RESISTOR_0603"))
    )
    (comp (ref "R24")
      (value "33 R")
      (footprint "eagle-import:R0603")
      (libsource (lib "eagle-import") (part "RESISTOR_0603"))
    )
    (comp (ref "R25")
      (value "33 R")
      (footprint "eagle-import:R0603")
      (libsource (lib "eagle-import") (part "RESISTOR_0603"))
    )
    (comp (ref "R26")
      (value "33 R")
      (footprint "eagle-import:R0603")
      (libsource (lib "eagle-import") (part "RESISTOR_0603"))
    )
    (comp (ref "R27")
      (value "10 k")
      (footprint "eagle-import:R0603")
      (libsource (lib "eagle-import") (part "RESISTOR_0603"))
    )
    (comp (ref "R29")
      (value "75 R")
      (footprint "eagle-import:R0603")
      (libsource (lib "eagle-import") (part "RESISTOR_0603"))
    )
    (comp (ref "R77")
      (value "12k1")
      (footprint "eagle-import:R0603")
      (libsource (lib "eagle-import") (part "RESISTOR_0603"))
    )
    (comp (ref "R79")
      (value "50 R")
      (footprint "eagle-import:R0603")
      (libsource (lib "eagle-import") (part "RESISTOR_0603"))
    )
    (comp (ref "R80")
      (value "50 R")
      (footprint "eagle-import:R0603")
      (libsource (lib "eagle-import") (part "RESISTOR_0603"))
    )
    (comp (ref "R81")
      (value "50 R")
      (footprint "eagle-import:R0603")
      (libsource (lib "eagle-import") (part "RESISTOR_0603"))
    )
    (comp (ref "R82")
      (value "50 R")
      (footprint "eagle-import:R0603")
      (libsource (lib "eagle-import") (part "RESISTOR_0603"))
    )
    (comp (ref "R83")
      (value "270 R")
      (footprint "eagle-import:R0603")
      (libsource (lib "eagle-import") (part "RESISTOR_0603"))
    )
    (comp (ref "R84")
      (value "270 R")
      (footprint "eagle-import:R0603")
      (libsource (lib "eagle-import") (part "RESISTOR_0603"))
    )
    (comp (ref "R85")
      (value "10 k")
      (footprint "eagle-import:R0603")
      (libsource (lib "eagle-import") (part "RESISTOR_0603"))
    )
    (comp (ref "R88")
      (value "75 R")
      (footprint "eagle-import:R0603")
      (libsource (lib "eagle-import") (part "RESISTOR_0603"))
    )
    (comp (ref "R89")
      (value "75 R")
      (footprint "eagle-import:R0603")
      (libsource (lib "eagle-import") (part "RESISTOR_0603"))
    )
    (comp (ref "R90")
      (value "75 R")
      (footprint "eagle-import:R0603")
      (libsource (lib "eagle-import") (part "RESISTOR_0603"))
    )
    (comp (ref "R91")
      (value "0 R")
      (footprint "eagle-import:R0603")
      (libsource (lib "eagle-import") (part "RESISTOR_0603"))
    )
    (comp (ref "T1")
      (value "H1102NL")
      (footprint "eagle-import:SOIC127P940X597-16N")
      (fields (field (name "MOUSER_PART_NUMBER") "673-H1102NL"))
      (libsource (lib "eagle-import") (part "H1102NL"))
    )
    (comp (ref "Y3")
      (value "ABLS2-25.000MHZ-D4YF-T")
      (footprint "eagle-import:ABLS")
      (fields (field (name "MOUSER_PART_NUMBER") "815-ABLS2-25-D4YF-T"))
      (libsource (lib "eagle-import") (part "ABLS2-25.000MHZ-D4YF-T"))
    )
    (comp (ref "C14")
      (value "100 nF")
      (footprint "eagle-import:C0603")
      (libsource (lib "eagle-import") (part "CAPACITOR_0603"))
    )
    (comp (ref "C19")
      (value "100 nF")
      (footprint "eagle-import:C0603")
      (libsource (lib "eagle-import") (part "CAPACITOR_0603"))
    )
    (comp (ref "C22")
      (value "100 nF")
      (footprint "eagle-import:C0603")
      (libsource (lib "eagle-import") (part "CAPACITOR_0603"))
    )
    (comp (ref "C24")
      (value "100 nF")
      (footprint "eagle-import:C0603")
      (libsource (lib "eagle-import") (part "CAPACITOR_0603"))
    )
    (comp (ref "C31")
      (value "10 uF")
      (footprint "eagle-import:C1206")
      (libsource (lib "eagle-import") (part "CAPACITOR_1206"))
    )
    (comp (ref "C32")
      (value "10 uF")
      (footprint "eagle-import:C1206")
      (libsource (lib "eagle-import") (part "CAPACITOR_1206"))
    )
    (comp (ref "C33")
      (value "10 uF")
      (footprint "eagle-import:C1206")
      (libsource (lib "eagle-import") (part "CAPACITOR_1206"))
    )
    (comp (ref "C34")
      (value "10 uF")
      (footprint "eagle-import:C1206")
      (libsource (lib "eagle-import") (part "CAPACITOR_1206"))
    )
    (comp (ref "C36")
      (value "100 nF")
      (footprint "eagle-import:C0603")
      (libsource (lib "eagle-import") (part "CAPACITOR_0603"))
    )
    (comp (ref "C39")
      (value "10 uF")
      (footprint "eagle-import:C1206")
      (libsource (lib "eagle-import") (part "CAPACITOR_1206"))
    )
    (comp (ref "C48")
      (value "100 nF")
      (footprint "eagle-import:C0603")
      (libsource (lib "eagle-import") (part "CAPACITOR_0603"))
    )
    (comp (ref "C49")
      (value "100 nF")
      (footprint "eagle-import:C0603")
      (libsource (lib "eagle-import") (part "CAPACITOR_0603"))
    )
    (comp (ref "C64")
      (value "10 uF")
      (footprint "eagle-import:C1206")
      (libsource (lib "eagle-import") (part "CAPACITOR_1206"))
    )
    (comp (ref "C95")
      (value "100 nF")
      (footprint "eagle-import:C0603")
      (libsource (lib "eagle-import") (part "CAPACITOR_0603"))
    )
    (comp (ref "C96")
      (value "100 nF")
      (footprint "eagle-import:C0603")
      (libsource (lib "eagle-import") (part "CAPACITOR_0603"))
    )
    (comp (ref "C97")
      (value "100 nF")
      (footprint "eagle-import:C0603")
      (libsource (lib "eagle-import") (part "CAPACITOR_0603"))
    )
    (comp (ref "C98")
      (value "100 nF")
      (footprint "eagle-import:C0603")
      (libsource (lib "eagle-import") (part "CAPACITOR_0603"))
    )
    (comp (ref "C99")
      (value "10 uF")
      (footprint "eagle-import:C1206")
      (libsource (lib "eagle-import") (part "CAPACITOR_1206"))
    )
    (comp (ref "IC2")
      (value "DAC084S085CIMM_NOPB")
      (footprint "eagle-import:SOP50P490X110-10N")
      (fields (field (name "MOUSER_PART_NUMBER") "926-DAC084S085CIMMNO"))
      (libsource (lib "eagle-import") (part "DAC084S085CIMM_NOPB"))
    )
    (comp (ref "IC3")
      (value "DAC084S085CIMM_NOPB")
      (footprint "eagle-import:SOP50P490X110-10N")
      (fields (field (name "MOUSER_PART_NUMBER") "926-DAC084S085CIMMNO"))
      (libsource (lib "eagle-import") (part "DAC084S085CIMM_NOPB"))
    )
    (comp (ref "IC7")
      (value "TL072")
      (footprint "eagle-import:SOIC8")
      (libsource (lib "eagle-import") (part "TL072"))
    )
    (comp (ref "IC14")
      (value "TL072")
      (footprint "eagle-import:SOIC8")
      (libsource (lib "eagle-import") (part "TL072"))
    )
    (comp (ref "IC15")
      (value "TL072")
      (footprint "eagle-import:SOIC8")
      (libsource (lib "eagle-import") (part "TL072"))
    )
    (comp (ref "R38")
      (value "27 k")
      (footprint "eagle-import:R0603")
      (libsource (lib "eagle-import") (part "RESISTOR_0603"))
    )
    (comp (ref "R40")
      (value "160 k")
      (footprint "eagle-import:R0603")
      (libsource (lib "eagle-import") (part "RESISTOR_0603"))
    )
    (comp (ref "R41")
      (value "27 k")
      (footprint "eagle-import:R0603")
      (libsource (lib "eagle-import") (part "RESISTOR_0603"))
    )
    (comp (ref "R43")
      (value "160 k")
      (footprint "eagle-import:R0603")
      (libsource (lib "eagle-import") (part "RESISTOR_0603"))
    )
    (comp (ref "R44")
      (value "27 k")
      (footprint "eagle-import:R0603")
      (libsource (lib "eagle-import") (part "RESISTOR_0603"))
    )
    (comp (ref "R46")
      (value "10 k")
      (footprint "eagle-import:R0603")
      (libsource (lib "eagle-import") (part "RESISTOR_0603"))
    )
    (comp (ref "R47")
      (value "1k8")
      (footprint "eagle-import:R0603")
      (libsource (lib "eagle-import") (part "RESISTOR_0603"))
    )
    (comp (ref "R58")
      (value "10 k")
      (footprint "eagle-import:R0603")
      (libsource (lib "eagle-import") (part "RESISTOR_0603"))
    )
    (comp (ref "R59")
      (value "56 k")
      (footprint "eagle-import:R0603")
      (libsource (lib "eagle-import") (part "RESISTOR_0603"))
    )
    (comp (ref "R60")
      (value "10 k")
      (footprint "eagle-import:R0603")
      (libsource (lib "eagle-import") (part "RESISTOR_0603"))
    )
    (comp (ref "R61")
      (value "10 k")
      (footprint "eagle-import:R0603")
      (libsource (lib "eagle-import") (part "RESISTOR_0603"))
    )
    (comp (ref "R62")
      (value "10 k")
      (footprint "eagle-import:R0603")
      (libsource (lib "eagle-import") (part "RESISTOR_0603"))
    )
    (comp (ref "R63")
      (value "160 k")
      (footprint "eagle-import:R0603")
      (libsource (lib "eagle-import") (part "RESISTOR_0603"))
    )
    (comp (ref "R64")
      (value "27 k")
      (footprint "eagle-import:R0603")
      (libsource (lib "eagle-import") (part "RESISTOR_0603"))
    )
    (comp (ref "R66")
      (value "160 k")
      (footprint "eagle-import:R0603")
      (libsource (lib "eagle-import") (part "RESISTOR_0603"))
    )
    (comp (ref "R67")
      (value "10 k")
      (footprint "eagle-import:R0603")
      (libsource (lib "eagle-import") (part "RESISTOR_0603"))
    )
    (comp (ref "R68")
      (value "20 k")
      (footprint "eagle-import:R0603")
      (libsource (lib "eagle-import") (part "RESISTOR_0603"))
    )
    (comp (ref "R70")
      (value "10 k")
      (footprint "eagle-import:R0603")
      (libsource (lib "eagle-import") (part "RESISTOR_0603"))
    )
    (comp (ref "R71")
      (value "10 k")
      (footprint "eagle-import:R0603")
      (libsource (lib "eagle-import") (part "RESISTOR_0603"))
    )
    (comp (ref "R72")
      (value "10 k")
      (footprint "eagle-import:R0603")
      (libsource (lib "eagle-import") (part "RESISTOR_0603"))
    )
    (comp (ref "R73")
      (value "56 k")
      (footprint "eagle-import:R0603")
      (libsource (lib "eagle-import") (part "RESISTOR_0603"))
    )
    (comp (ref "R74")
      (value "10 k")
      (footprint "eagle-import:R0603")
      (libsource (lib "eagle-import") (part "RESISTOR_0603"))
    )
    (comp (ref "R75")
      (value "10 k")
      (footprint "eagle-import:R0603")
      (libsource (lib "eagle-import") (part "RESISTOR_0603"))
    )
    (comp (ref "R76")
      (value "1k8")
      (footprint "eagle-import:R0603")
      (libsource (lib "eagle-import") (part "RESISTOR_0603"))
    )
    (comp (ref "R92")
      (value "500 R")
      (footprint "eagle-import:R0603")
      (libsource (lib "eagle-import") (part "RESISTOR_0603"))
    )
    (comp (ref "R93")
      (value "500 R")
      (footprint "eagle-import:R0603")
      (libsource (lib "eagle-import") (part "RESISTOR_0603"))
    )
    (comp (ref "R94")
      (value "500 R")
      (footprint "eagle-import:R0603")
      (libsource (lib "eagle-import") (part "RESISTOR_0603"))
    )
    (comp (ref "R95")
      (value "500 R")
      (footprint "eagle-import:R0603")
      (libsource (lib "eagle-import") (part "RESISTOR_0603"))
    )
    (comp (ref "Z1")
      (value "ZENER_DIODE_BZT")
      (footprint "eagle-import:SODFL1608X65N")
      (fields (field (name "MOUSER_PART_NUMBER") "621-BZT52C2V0T-7"))
      (libsource (lib "eagle-import") (part "ZENER_DIODE_BZT"))
    )
    (comp (ref "C44")
      (value "100 nF")
      (footprint "eagle-import:C0603")
      (libsource (lib "eagle-import") (part "CAPACITOR_0603"))
    )
    (comp (ref "C65")
      (value "2.7 pF")
      (footprint "eagle-import:C0603")
      (libsource (lib "eagle-import") (part "CAPACITOR_0603"))
    )
    (comp (ref "C66")
      (value "2.7 pF")
      (footprint "eagle-import:C0603")
      (libsource (lib "eagle-import") (part "CAPACITOR_0603"))
    )
    (comp (ref "C69")
      (value "4.3 pF")
      (footprint "eagle-import:C0603")
      (libsource (lib "eagle-import") (part "CAPACITOR_0603"))
    )
    (comp (ref "C70")
      (value "4.3 pF")
      (footprint "eagle-import:C0603")
      (libsource (lib "eagle-import") (part "CAPACITOR_0603"))
    )
    (comp (ref "C71")
      (value "2.2 uF")
      (footprint "eagle-import:C1206")
      (libsource (lib "eagle-import") (part "CAPACITOR_1206"))
    )
    (comp (ref "C72")
      (value "2.2 uF")
      (footprint "eagle-import:C1206")
      (libsource (lib "eagle-import") (part "CAPACITOR_1206"))
    )
    (comp (ref "C73")
      (value "100 nF")
      (footprint "eagle-import:C0603")
      (libsource (lib "eagle-import") (part "CAPACITOR_0603"))
    )
    (comp (ref "C74")
      (value "100 nF")
      (footprint "eagle-import:C0603")
      (libsource (lib "eagle-import") (part "CAPACITOR_0603"))
    )
    (comp (ref "C75")
      (value "100 nF")
      (footprint "eagle-import:C0603")
      (libsource (lib "eagle-import") (part "CAPACITOR_0603"))
    )
    (comp (ref "C76")
      (value "100 nF")
      (footprint "eagle-import:C0603")
      (libsource (lib "eagle-import") (part "CAPACITOR_0603"))
    )
    (comp (ref "C77")
      (value "100 nF")
      (footprint "eagle-import:C0603")
      (libsource (lib "eagle-import") (part "CAPACITOR_0603"))
    )
    (comp (ref "C78")
      (value "100 nF")
      (footprint "eagle-import:C0603")
      (libsource (lib "eagle-import") (part "CAPACITOR_0603"))
    )
    (comp (ref "C79")
      (value "100 nF")
      (footprint "eagle-import:C0603")
      (libsource (lib "eagle-import") (part "CAPACITOR_0603"))
    )
    (comp (ref "C80")
      (value "100 nF")
      (footprint "eagle-import:C0603")
      (libsource (lib "eagle-import") (part "CAPACITOR_0603"))
    )
    (comp (ref "C81")
      (value "100 nF")
      (footprint "eagle-import:C0603")
      (libsource (lib "eagle-import") (part "CAPACITOR_0603"))
    )
    (comp (ref "C82")
      (value "100 nF")
      (footprint "eagle-import:C0603")
      (libsource (lib "eagle-import") (part "CAPACITOR_0603"))
    )
    (comp (ref "C83")
      (value "100 nF")
      (footprint "eagle-import:C0603")
      (libsource (lib "eagle-import") (part "CAPACITOR_0603"))
    )
    (comp (ref "C84")
      (value "100 nF")
      (footprint "eagle-import:C0603")
      (libsource (lib "eagle-import") (part "CAPACITOR_0603"))
    )
    (comp (ref "C85")
      (value "100 nF")
      (footprint "eagle-import:C0603")
      (libsource (lib "eagle-import") (part "CAPACITOR_0603"))
    )
    (comp (ref "DEBUG1")
      (value "TPTHT")
      (footprint "eagle-import:THT_PIN")
      (libsource (lib "eagle-import") (part "TPTHT"))
    )
    (comp (ref "DEBUG2")
      (value "TPTHT")
      (footprint "eagle-import:THT_PIN")
      (libsource (lib "eagle-import") (part "TPTHT"))
    )
    (comp (ref "DISPLAY")
      (value "90814-0204")
      (footprint "eagle-import:MOLEX_90814-0204")
      (fields (field (name "MOUSER_PART_NUMBER") "538-90814-0204"))
      (libsource (lib "eagle-import") (part "90814-0204"))
    )
    (comp (ref "IC10")
      (value "STM32F767ZIT6")
      (footprint "eagle-import:QFP50P2200X2200X160-144N")
      (fields (field (name "MOUSER_PART_NUMBER") "511-STM32F767ZIT6"))
      (libsource (lib "eagle-import") (part "STM32F767ZIT6"))
    )
    (comp (ref "IC12")
      (value "ESDA6V1BC6")
      (footprint "eagle-import:SOT95P280X145-6N")
      (fields (field (name "MOUSER_PART_NUMBER") "511-ESDA6V1BC6"))
      (libsource (lib "eagle-import") (part "ESDA6V1BC6"))
    )
    (comp (ref "LD1")
      (value "LED_YELOW_SMD")
      (footprint "eagle-import:WL-SMCW_0603")
      (fields (field (name "MOUSER_PART_NUMBER") "..."))
      (libsource (lib "eagle-import") (part "LED_SMD_YELOW"))
    )
    (comp (ref "LD2")
      (value "LED_RED_SMD")
      (footprint "eagle-import:WL-SMCW_0603")
      (fields (field (name "MOUSER_PART_NUMBER") "..."))
      (libsource (lib "eagle-import") (part "LED_SMD_RED"))
    )
    (comp (ref "LD3")
      (value "LED_GREEN_SMD")
      (footprint "eagle-import:WL-SMCW_0603")
      (fields (field (name "MOUSER_PART_NUMBER") "..."))
      (libsource (lib "eagle-import") (part "LED_SMD_GREEN"))
    )
    (comp (ref "PROG.")
      (value "90814-0204")
      (footprint "eagle-import:MOLEX_90814-0204")
      (fields (field (name "MOUSER_PART_NUMBER") "538-90814-0204"))
      (libsource (lib "eagle-import") (part "90814-0204"))
    )
    (comp (ref "R5")
      (value "680 R")
      (footprint "eagle-import:R0603")
      (libsource (lib "eagle-import") (part "RESISTOR_0603"))
    )
    (comp (ref "R6")
      (value "680 R")
      (footprint "eagle-import:R0603")
      (libsource (lib "eagle-import") (part "RESISTOR_0603"))
    )
    (comp (ref "R13")
      (value "680 R")
      (footprint "eagle-import:R0603")
      (libsource (lib "eagle-import") (part "RESISTOR_0603"))
    )
    (comp (ref "R19")
      (value "10 k")
      (footprint "eagle-import:R0603")
      (libsource (lib "eagle-import") (part "RESISTOR_0603"))
    )
    (comp (ref "R78")
      (value "10 k")
      (footprint "eagle-import:R0603")
      (libsource (lib "eagle-import") (part "RESISTOR_0603"))
    )
    (comp (ref "S1")
      (value "PTS647SN50SMTR2LFS")
      (footprint "eagle-import:PTS647SN50SMTR2LFS")
      (fields (field (name "MOUSER_PART_NUMBER") "611-PTS647SN50SMTR2L"))
      (libsource (lib "eagle-import") (part "PTS647SN50SMTR2LFS"))
    )
    (comp (ref "X1")
      (value "USB_B_CONNECTOR")
      (footprint "eagle-import:SMARTPRJ_PN61729")
      (fields (field (name "MOUSER_PART_NUMBER") "649-61729-0010BLF"))
      (libsource (lib "eagle-import") (part "USB_B_CONNECTOR"))
    )
    (comp (ref "Y1")
      (value "NX3215SA-32.768K-STD-MUA-8")
      (footprint "eagle-import:NX3215SA")
      (fields (field (name "MOUSER_PART_NUMBER") "344-NX3215SA32768K8"))
      (libsource (lib "eagle-import") (part "NX3215SA-32.768K-STD-MUA-8"))
    )
    (comp (ref "Y2")
      (value "NX3225GD-8MHZ-STD-CRA-3")
      (footprint "eagle-import:RESC3226X100N")
      (fields (field (name "MOUSER_PART_NUMBER") "344-NX3225GD8MCRA3"))
      (libsource (lib "eagle-import") (part "NX3225GD-8MHZ-STD-CRA-3"))
    )
    (comp (ref "K1")
      (value "Relay")
      (footprint "eagle-import:351")
      (libsource (lib "eagle-import") (part "RELAY_EE2-5NU"))
    )
    (comp (ref "K2")
      (value "Relay")
      (footprint "eagle-import:351")
      (libsource (lib "eagle-import") (part "RELAY_EE2-5NU"))
    )
    (comp (ref "K5")
      (value "Relay")
      (footprint "eagle-import:351")
      (fields (field (name "SPICEPREFIX") "B"))
      (libsource (lib "eagle-import") (part "RELAY_EE2-5NU"))
    )
    (comp (ref "K6")
      (value "Relay")
      (footprint "eagle-import:351")
      (fields (field (name "SPICEPREFIX") "B"))
      (libsource (lib "eagle-import") (part "RELAY_EE2-5NU"))
    )
    (comp (ref "K7")
      (value "Relay")
      (footprint "eagle-import:351")
      (libsource (lib "eagle-import") (part "RELAY_EE2-5NU"))
    )
    (comp (ref "K8")
      (value "Relay")
      (footprint "eagle-import:351")
      (libsource (lib "eagle-import") (part "RELAY_EE2-5NU"))
    )
    (comp (ref "LED1")
      (value "LED_BLUE_SMD")
      (footprint "eagle-import:WL-SMCW_0603")
      (fields (field (name "MOUSER_PART_NUMBER") "..."))
      (libsource (lib "eagle-import") (part "LED_SMD_BLUE"))
    )
    (comp (ref "LED2")
      (value "LED_BLUE_SMD")
      (footprint "eagle-import:WL-SMCW_0603")
      (fields (field (name "MOUSER_PART_NUMBER") "..."))
      (libsource (lib "eagle-import") (part "LED_SMD_BLUE"))
    )
    (comp (ref "LED3")
      (value "LED_BLUE_SMD")
      (footprint "eagle-import:WL-SMCW_0603")
      (fields (field (name "MOUSER_PART_NUMBER") "..."))
      (libsource (lib "eagle-import") (part "LED_SMD_BLUE"))
    )
    (comp (ref "LED4")
      (value "LED_BLUE_SMD")
      (footprint "eagle-import:WL-SMCW_0603")
      (fields (field (name "MOUSER_PART_NUMBER") "..."))
      (libsource (lib "eagle-import") (part "LED_SMD_BLUE"))
    )
    (comp (ref "LED5")
      (value "LED_BLUE_SMD")
      (footprint "eagle-import:WL-SMCW_0603")
      (fields (field (name "MOUSER_PART_NUMBER") "..."))
      (libsource (lib "eagle-import") (part "LED_SMD_BLUE"))
    )
    (comp (ref "LED6")
      (value "LED_BLUE_SMD")
      (footprint "eagle-import:WL-SMCW_0603")
      (fields (field (name "MOUSER_PART_NUMBER") "..."))
      (libsource (lib "eagle-import") (part "LED_SMD_BLUE"))
    )
    (comp (ref "LED7")
      (value "LED_BLUE_SMD")
      (footprint "eagle-import:WL-SMCW_0603")
      (fields (field (name "MOUSER_PART_NUMBER") "..."))
      (libsource (lib "eagle-import") (part "LED_SMD_BLUE"))
    )
    (comp (ref "LED8")
      (value "LED_BLUE_SMD")
      (footprint "eagle-import:WL-SMCW_0603")
      (fields (field (name "MOUSER_PART_NUMBER") "..."))
      (libsource (lib "eagle-import") (part "LED_SMD_BLUE"))
    )
    (comp (ref "R7")
      (value "680 R")
      (footprint "eagle-import:R0603")
      (libsource (lib "eagle-import") (part "RESISTOR_0603"))
    )
    (comp (ref "R8")
      (value "680 R")
      (footprint "eagle-import:R0603")
      (libsource (lib "eagle-import") (part "RESISTOR_0603"))
    )
    (comp (ref "R9")
      (value "680 R")
      (footprint "eagle-import:R0603")
      (libsource (lib "eagle-import") (part "RESISTOR_0603"))
    )
    (comp (ref "R10")
      (value "680 R")
      (footprint "eagle-import:R0603")
      (libsource (lib "eagle-import") (part "RESISTOR_0603"))
    )
    (comp (ref "R11")
      (value "680 R")
      (footprint "eagle-import:R0603")
      (libsource (lib "eagle-import") (part "RESISTOR_0603"))
    )
    (comp (ref "R12")
      (value "680 R")
      (footprint "eagle-import:R0603")
      (libsource (lib "eagle-import") (part "RESISTOR_0603"))
    )
    (comp (ref "R33")
      (value "680 R")
      (footprint "eagle-import:R0603")
      (libsource (lib "eagle-import") (part "RESISTOR_0603"))
    )
    (comp (ref "R34")
      (value "680 R")
      (footprint "eagle-import:R0603")
      (libsource (lib "eagle-import") (part "RESISTOR_0603"))
    )
    (comp (ref "U12")
      (value "ULN2003")
      (footprint "eagle-import:SOIC16")
      (libsource (lib "eagle-import") (part "ULN2003"))
    )
    (comp (ref "C41")
      (value "100 nF")
      (footprint "eagle-import:C0603")
      (libsource (lib "eagle-import") (part "CAPACITOR_0603"))
    )
    (comp (ref "C42")
      (value "10 uF")
      (footprint "eagle-import:C1206")
      (libsource (lib "eagle-import") (part "CAPACITOR_1206"))
    )
    (comp (ref "C51")
      (value "10 uF")
      (footprint "eagle-import:C1206")
      (libsource (lib "eagle-import") (part "CAPACITOR_1206"))
    )
    (comp (ref "C52")
      (value "1 uF")
      (footprint "eagle-import:C0603")
      (libsource (lib "eagle-import") (part "CAPACITOR_0603"))
    )
    (comp (ref "C59")
      (value "1 uF")
      (footprint "eagle-import:C0603")
      (libsource (lib "eagle-import") (part "CAPACITOR_0603"))
    )
    (comp (ref "IC11")
      (value "AD7606BSTZ")
      (footprint "eagle-import:QFP50P1200X1200X160-64N")
      (fields (field (name "MOUSER_PART_NUMBER") "584-AD7606BSTZ"))
      (libsource (lib "eagle-import") (part "AD7606BSTZ"))
    )
    (comp (ref "R1")
      (value "10 k")
      (footprint "eagle-import:R0603")
      (libsource (lib "eagle-import") (part "RESISTOR_0603"))
    )
    (comp (ref "R2")
      (value "100 k")
      (footprint "eagle-import:R0603")
      (libsource (lib "eagle-import") (part "RESISTOR_0603"))
    )
    (comp (ref "R3")
      (value "100 k")
      (footprint "eagle-import:R0603")
      (libsource (lib "eagle-import") (part "RESISTOR_0603"))
    )
    (comp (ref "R4")
      (value "10 k")
      (footprint "eagle-import:R0603")
      (libsource (lib "eagle-import") (part "RESISTOR_0603"))
    )
    (comp (ref "R14")
      (value "10 k")
      (footprint "eagle-import:R0603")
      (libsource (lib "eagle-import") (part "RESISTOR_0603"))
    )
    (comp (ref "R35")
      (value "10 k")
      (footprint "eagle-import:R0603")
      (libsource (lib "eagle-import") (part "RESISTOR_0603"))
    )
    (comp (ref "R39")
      (value "100 k")
      (footprint "eagle-import:R0603")
      (libsource (lib "eagle-import") (part "RESISTOR_0603"))
    )
    (comp (ref "R42")
      (value "10 k")
      (footprint "eagle-import:R0603")
      (libsource (lib "eagle-import") (part "RESISTOR_0603"))
    )
    (comp (ref "R45")
      (value "100 k")
      (footprint "eagle-import:R0603")
      (libsource (lib "eagle-import") (part "RESISTOR_0603"))
    )
    (comp (ref "R65")
      (value "10 k")
      (footprint "eagle-import:R0603")
      (libsource (lib "eagle-import") (part "RESISTOR_0603"))
    )
    (comp (ref "R86")
      (value "100 k")
      (footprint "eagle-import:R0603")
      (libsource (lib "eagle-import") (part "RESISTOR_0603"))
    )
    (comp (ref "R87")
      (value "10 k")
      (footprint "eagle-import:R0603")
      (libsource (lib "eagle-import") (part "RESISTOR_0603"))
    )
    (comp (ref "C50")
      (value "100 nF")
      (footprint "eagle-import:C0603")
      (libsource (lib "eagle-import") (part "CAPACITOR_0603"))
    )
    (comp (ref "C53")
      (value "100 nF")
      (footprint "eagle-import:C0603")
      (libsource (lib "eagle-import") (part "CAPACITOR_0603"))
    )
    (comp (ref "C54")
      (value "100 nF")
      (footprint "eagle-import:C0603")
      (libsource (lib "eagle-import") (part "CAPACITOR_0603"))
    )
    (comp (ref "C55")
      (value "22 pF")
      (footprint "eagle-import:C0603")
      (libsource (lib "eagle-import") (part "CAPACITOR_0603"))
    )
    (comp (ref "C56")
      (value "22 pF")
      (footprint "eagle-import:C0603")
      (libsource (lib "eagle-import") (part "CAPACITOR_0603"))
    )
    (comp (ref "C57")
      (value "100 nF")
      (footprint "eagle-import:C0603")
      (libsource (lib "eagle-import") (part "CAPACITOR_0603"))
    )
    (comp (ref "C58")
      (value "100 nF")
      (footprint "eagle-import:C0603")
      (libsource (lib "eagle-import") (part "CAPACITOR_0603"))
    )
    (comp (ref "C60")
      (value "100 nF")
      (footprint "eagle-import:C0603")
      (libsource (lib "eagle-import") (part "CAPACITOR_0603"))
    )
    (comp (ref "C61")
      (value "100 nF")
      (footprint "eagle-import:C0603")
      (libsource (lib "eagle-import") (part "CAPACITOR_0603"))
    )
    (comp (ref "C62")
      (value "100 nF")
      (footprint "eagle-import:C0603")
      (libsource (lib "eagle-import") (part "CAPACITOR_0603"))
    )
    (comp (ref "C67")
      (value "10 uF")
      (footprint "eagle-import:C1206")
      (libsource (lib "eagle-import") (part "CAPACITOR_1206"))
    )
    (comp (ref "C102")
      (value "10 uF")
      (footprint "eagle-import:C1206")
      (libsource (lib "eagle-import") (part "CAPACITOR_1206"))
    )
    (comp (ref "IC8")
      (value "OP275")
      (footprint "eagle-import:SOIC8")
      (libsource (lib "eagle-import") (part "OP275"))
    )
    (comp (ref "IC9")
      (value "TL072")
      (footprint "eagle-import:SOIC8")
      (libsource (lib "eagle-import") (part "TL072"))
    )
    (comp (ref "R48")
      (value "20 k")
      (footprint "eagle-import:R0603")
      (libsource (lib "eagle-import") (part "RESISTOR_0603"))
    )
    (comp (ref "R49")
      (value "20 k")
      (footprint "eagle-import:R0603")
      (libsource (lib "eagle-import") (part "RESISTOR_0603"))
    )
    (comp (ref "R50")
      (value "5k1")
      (footprint "eagle-import:R0603")
      (libsource (lib "eagle-import") (part "RESISTOR_0603"))
    )
    (comp (ref "R51")
      (value "5k1")
      (footprint "eagle-import:R0603")
      (libsource (lib "eagle-import") (part "RESISTOR_0603"))
    )
    (comp (ref "R52")
      (value "20 k")
      (footprint "eagle-import:R0603")
      (libsource (lib "eagle-import") (part "RESISTOR_0603"))
    )
    (comp (ref "R53")
      (value "20 k")
      (footprint "eagle-import:R0603")
      (libsource (lib "eagle-import") (part "RESISTOR_0603"))
    )
    (comp (ref "R54")
      (value "10 k")
      (footprint "eagle-import:R0603")
      (libsource (lib "eagle-import") (part "RESISTOR_0603"))
    )
    (comp (ref "R55")
      (value "10 k")
      (footprint "eagle-import:R0603")
      (libsource (lib "eagle-import") (part "RESISTOR_0603"))
    )
    (comp (ref "R56")
      (value "10 k")
      (footprint "eagle-import:R0603")
      (libsource (lib "eagle-import") (part "RESISTOR_0603"))
    )
    (comp (ref "R57")
      (value "10 k")
      (footprint "eagle-import:R0603")
      (libsource (lib "eagle-import") (part "RESISTOR_0603"))
    )
    (comp (ref "TP36")
      (value "TPTHT")
      (footprint "eagle-import:THT_PIN")
      (libsource (lib "eagle-import") (part "TPTHT"))
    )
    (comp (ref "TP37")
      (value "TPTHT")
      (footprint "eagle-import:THT_PIN")
      (libsource (lib "eagle-import") (part "TPTHT"))
    )
    (comp (ref "VCA1(LEFT)")
      (value "THAT2181SO8-US")
      (footprint "eagle-import:SO08")
      (fields (field (name "MOUSER_PART_NUMBER") "887-2181CS08-U"))
      (libsource (lib "eagle-import") (part "THAT2181SSO8-U"))
    )
    (comp (ref "VCA2(RIGHT)")
      (value "THAT2181SO8-US")
      (footprint "eagle-import:SO08")
      (fields (field (name "MOUSER_PART_NUMBER") "887-2181CS08-U"))
      (libsource (lib "eagle-import") (part "THAT2181SSO8-U"))
    )
    (comp (ref "C6")
      (value "100 nF")
      (footprint "eagle-import:C0603")
      (libsource (lib "eagle-import") (part "CAPACITOR_0603"))
    )
    (comp (ref "C7")
      (value "100 nF")
      (footprint "eagle-import:C0603")
      (libsource (lib "eagle-import") (part "CAPACITOR_0603"))
    )
    (comp (ref "C26")
      (value "100 nF")
      (footprint "eagle-import:C0603")
      (libsource (lib "eagle-import") (part "CAPACITOR_0603"))
    )
    (comp (ref "C27")
      (value "100 nF")
      (footprint "eagle-import:C0603")
      (libsource (lib "eagle-import") (part "CAPACITOR_0603"))
    )
    (comp (ref "C28")
      (value "100 nF")
      (footprint "eagle-import:C0603")
      (libsource (lib "eagle-import") (part "CAPACITOR_0603"))
    )
    (comp (ref "C29")
      (value "100 nF")
      (footprint "eagle-import:C0603")
      (libsource (lib "eagle-import") (part "CAPACITOR_0603"))
    )
    (comp (ref "IC1")
      (value "OP275")
      (footprint "eagle-import:SOIC8")
      (libsource (lib "eagle-import") (part "OP275"))
    )
    (comp (ref "U7")
      (value "THAT1240")
      (footprint "eagle-import:SO08")
      (fields (field (name "MOUSER_PART_NUMBER") "887-1240S08-U"))
      (libsource (lib "eagle-import") (part "THAT1240SO8-USO8-U"))
    )
    (comp (ref "U8")
      (value "THAT1240")
      (footprint "eagle-import:SO08")
      (fields (field (name "MOUSER_PART_NUMBER") "887-1240S08-U"))
      (libsource (lib "eagle-import") (part "THAT1240SO8-USO8-U"))
    )
    (comp (ref "C2")
      (value "100 nF")
      (footprint "eagle-import:C0603")
      (libsource (lib "eagle-import") (part "CAPACITOR_0603"))
    )
    (comp (ref "C3")
      (value "100 nF")
      (footprint "eagle-import:C0603")
      (libsource (lib "eagle-import") (part "CAPACITOR_0603"))
    )
    (comp (ref "C9")
      (value "470 pF")
      (footprint "eagle-import:C0603")
      (libsource (lib "eagle-import") (part "CAPACITOR_0603"))
    )
    (comp (ref "C10")
      (value "470 pF")
      (footprint "eagle-import:C0603")
      (libsource (lib "eagle-import") (part "CAPACITOR_0603"))
    )
    (comp (ref "C12")
      (value "100 nF")
      (footprint "eagle-import:C0603")
      (libsource (lib "eagle-import") (part "CAPACITOR_0603"))
    )
    (comp (ref "C13")
      (value "100 nF")
      (footprint "eagle-import:C0603")
      (libsource (lib "eagle-import") (part "CAPACITOR_0603"))
    )
    (comp (ref "C15")
      (value "47 pF")
      (footprint "eagle-import:C0603")
      (libsource (lib "eagle-import") (part "CAPACITOR_0603"))
    )
    (comp (ref "IN1(R/S)")
      (value "NEUTRIK_NC3FAH")
      (footprint "eagle-import:NEUTRIK_NC3FAH")
      (libsource (lib "eagle-import") (part "NEUTRIK_NC3FAH"))
    )
    (comp (ref "IN_RIGHT")
      (value "THAT1240")
      (footprint "eagle-import:SO08")
      (fields (field (name "MOUSER_PART_NUMBER") "887-1240S08-U"))
      (libsource (lib "eagle-import") (part "THAT1240SO8-USO8-U"))
    )
    (comp (ref "OUT1(R/S)")
      (value "NEUTRIK_NC3MAH")
      (footprint "eagle-import:NEUTRIK_NC3MAH")
      (libsource (lib "eagle-import") (part "NEUTRIK_NC3MAH"))
    )
    (comp (ref "OUT_RIGHT")
      (value "THAT1646")
      (footprint "eagle-import:SO08")
      (fields (field (name "MOUSER_PART_NUMBER") "887-1646S08-U"))
      (libsource (lib "eagle-import") (part "THAT1646SO8-USO8-U"))
    )
    (comp (ref "C4")
      (value "100 nF")
      (footprint "eagle-import:C0603")
      (libsource (lib "eagle-import") (part "CAPACITOR_0603"))
    )
    (comp (ref "C5")
      (value "100 nF")
      (footprint "eagle-import:C0603")
      (libsource (lib "eagle-import") (part "CAPACITOR_0603"))
    )
    (comp (ref "C20")
      (value "100 nF")
      (footprint "eagle-import:C0603")
      (libsource (lib "eagle-import") (part "CAPACITOR_0603"))
    )
    (comp (ref "C21")
      (value "100 nF")
      (footprint "eagle-import:C0603")
      (libsource (lib "eagle-import") (part "CAPACITOR_0603"))
    )
    (comp (ref "C23")
      (value "100 nF")
      (footprint "eagle-import:C0603")
      (libsource (lib "eagle-import") (part "CAPACITOR_0603"))
    )
    (comp (ref "C25")
      (value "100 nF")
      (footprint "eagle-import:C0603")
      (libsource (lib "eagle-import") (part "CAPACITOR_0603"))
    )
    (comp (ref "C63")
      (value "100 nF")
      (footprint "eagle-import:C0603")
      (libsource (lib "eagle-import") (part "CAPACITOR_0603"))
    )
    (comp (ref "C68")
      (value "100 nF")
      (footprint "eagle-import:C0603")
      (libsource (lib "eagle-import") (part "CAPACITOR_0603"))
    )
    (comp (ref "IC4")
      (value "OP275")
      (footprint "eagle-import:SOIC8")
      (libsource (lib "eagle-import") (part "OP275"))
    )
    (comp (ref "IC16")
      (value "OP275")
      (footprint "eagle-import:SOIC8")
      (libsource (lib "eagle-import") (part "OP275"))
    )
    (comp (ref "U4")
      (value "THAT1240")
      (footprint "eagle-import:SO08")
      (fields (field (name "MOUSER_PART_NUMBER") "887-1240S08-U"))
      (libsource (lib "eagle-import") (part "THAT1240SO8-USO8-U"))
    )
    (comp (ref "U6")
      (value "THAT1240")
      (footprint "eagle-import:SO08")
      (fields (field (name "MOUSER_PART_NUMBER") "887-1240S08-U"))
      (libsource (lib "eagle-import") (part "THAT1240SO8-USO8-U"))
    )
    (comp (ref "C30")
      (value "100 nF")
      (footprint "eagle-import:C0603")
      (libsource (lib "eagle-import") (part "CAPACITOR_0603"))
    )
    (comp (ref "C35")
      (value "100 nF")
      (footprint "eagle-import:C0603")
      (libsource (lib "eagle-import") (part "CAPACITOR_0603"))
    )
    (comp (ref "C37")
      (value "22 pF")
      (footprint "eagle-import:C0603")
      (libsource (lib "eagle-import") (part "CAPACITOR_0603"))
    )
    (comp (ref "C38")
      (value "22 pF")
      (footprint "eagle-import:C0603")
      (libsource (lib "eagle-import") (part "CAPACITOR_0603"))
    )
    (comp (ref "C43")
      (value "100 nF")
      (footprint "eagle-import:C0603")
      (libsource (lib "eagle-import") (part "CAPACITOR_0603"))
    )
    (comp (ref "C45")
      (value "100 nF")
      (footprint "eagle-import:C0603")
      (libsource (lib "eagle-import") (part "CAPACITOR_0603"))
    )
    (comp (ref "C46")
      (value "100 nF")
      (footprint "eagle-import:C0603")
      (libsource (lib "eagle-import") (part "CAPACITOR_0603"))
    )
    (comp (ref "C47")
      (value "100 nF")
      (footprint "eagle-import:C0603")
      (libsource (lib "eagle-import") (part "CAPACITOR_0603"))
    )
    (comp (ref "IC5")
      (value "OP275")
      (footprint "eagle-import:SOIC8")
      (libsource (lib "eagle-import") (part "OP275"))
    )
    (comp (ref "R28")
      (value "20 k")
      (footprint "eagle-import:R0603")
      (libsource (lib "eagle-import") (part "RESISTOR_0603"))
    )
    (comp (ref "R30")
      (value "20 k")
      (footprint "eagle-import:R0603")
      (libsource (lib "eagle-import") (part "RESISTOR_0603"))
    )
    (comp (ref "R31")
      (value "5k1")
      (footprint "eagle-import:R0603")
      (libsource (lib "eagle-import") (part "RESISTOR_0603"))
    )
    (comp (ref "R32")
      (value "5k1")
      (footprint "eagle-import:R0603")
      (libsource (lib "eagle-import") (part "RESISTOR_0603"))
    )
    (comp (ref "R36")
      (value "20 k")
      (footprint "eagle-import:R0603")
      (libsource (lib "eagle-import") (part "RESISTOR_0603"))
    )
    (comp (ref "R37")
      (value "20 k")
      (footprint "eagle-import:R0603")
      (libsource (lib "eagle-import") (part "RESISTOR_0603"))
    )
    (comp (ref "STAGE(LEFT)")
      (value "THAT2181SO8-US")
      (footprint "eagle-import:SO08")
      (fields (field (name "MOUSER_PART_NUMBER") "887-2181CS08-U"))
      (libsource (lib "eagle-import") (part "THAT2181SSO8-U"))
    )
    (comp (ref "STAGE(RIGHT)")
      (value "THAT2181SO8-US")
      (footprint "eagle-import:SO08")
      (fields (field (name "MOUSER_PART_NUMBER") "887-2181CS08-U"))
      (libsource (lib "eagle-import") (part "THAT2181SSO8-U"))
    )
    (comp (ref "TP01")
      (value "TPTHT")
      (footprint "eagle-import:THT_PIN")
      (libsource (lib "eagle-import") (part "TPTHT"))
    )
    (comp (ref "TP02")
      (value "TPTHT")
      (footprint "eagle-import:THT_PIN")
      (libsource (lib "eagle-import") (part "TPTHT"))
    )
    (comp (ref "+3V3_OK")
      (value "LED_GREEN_SMD")
      (footprint "eagle-import:WL-SMCW_0603")
      (fields (field (name "MOUSER_PART_NUMBER") "..."))
      (libsource (lib "eagle-import") (part "LED_SMD_GREEN"))
    )
    (comp (ref "+5V_OK")
      (value "LED_GREEN_SMD")
      (footprint "eagle-import:WL-SMCW_0603")
      (fields (field (name "MOUSER_PART_NUMBER") "..."))
      (libsource (lib "eagle-import") (part "LED_SMD_GREEN"))
    )
    (comp (ref "+12V_OK")
      (value "LED_GREEN_SMD")
      (footprint "eagle-import:WL-SMCW_0603")
      (fields (field (name "MOUSER_PART_NUMBER") "..."))
      (libsource (lib "eagle-import") (part "LED_SMD_GREEN"))
    )
    (comp (ref "+15V_OK")
      (value "LED_GREEN_SMD")
      (footprint "eagle-import:WL-SMCW_0603")
      (fields (field (name "MOUSER_PART_NUMBER") "..."))
      (libsource (lib "eagle-import") (part "LED_SMD_GREEN"))
    )
    (comp (ref "-15V_OK")
      (value "LED_GREEN_SMD")
      (footprint "eagle-import:WL-SMCW_0603")
      (fields (field (name "MOUSER_PART_NUMBER") "..."))
      (libsource (lib "eagle-import") (part "LED_SMD_GREEN"))
    )
    (comp (ref "ANALOG_VOLT")
      (value "90814-0204")
      (footprint "eagle-import:MOLEX_90814-0204")
      (fields (field (name "MOUSER_PART_NUMBER") "538-90814-0204"))
      (libsource (lib "eagle-import") (part "90814-0204"))
    )
    (comp (ref "DIGITAL_VOLT")
      (value "90814-0204")
      (footprint "eagle-import:MOLEX_90814-0204")
      (fields (field (name "MOUSER_PART_NUMBER") "538-90814-0204"))
      (libsource (lib "eagle-import") (part "90814-0204"))
    )
    (comp (ref "R15")
      (value "0 R")
      (footprint "eagle-import:R0603")
      (libsource (lib "eagle-import") (part "RESISTOR_0603"))
    )
    (comp (ref "R16")
      (value "0 R")
      (footprint "eagle-import:R0603")
      (libsource (lib "eagle-import") (part "RESISTOR_0603"))
    )
    (comp (ref "R17")
      (value "0 R")
      (footprint "eagle-import:R0603")
      (libsource (lib "eagle-import") (part "RESISTOR_0603"))
    )
    (comp (ref "R69")
      (value "0 R")
      (footprint "eagle-import:R0603")
      (libsource (lib "eagle-import") (part "RESISTOR_0603"))
    )
    (comp (ref "R97")
      (value "680 R")
      (footprint "eagle-import:R0603")
      (libsource (lib "eagle-import") (part "RESISTOR_0603"))
    )
    (comp (ref "R98")
      (value "680 R")
      (footprint "eagle-import:R0603")
      (libsource (lib "eagle-import") (part "RESISTOR_0603"))
    )
    (comp (ref "R99")
      (value "65 R")
      (footprint "eagle-import:R0603")
      (libsource (lib "eagle-import") (part "RESISTOR_0603"))
    )
    (comp (ref "R100")
      (value "150 R")
      (footprint "eagle-import:R0603")
      (libsource (lib "eagle-import") (part "RESISTOR_0603"))
    )
    (comp (ref "R101")
      (value "500 R")
      (footprint "eagle-import:R0603")
      (libsource (lib "eagle-import") (part "RESISTOR_0603"))
    )
  )
  (nets
    (net (code "1") (name "+3V3") (class "Default")
      (node (ref "C73") (pin "1") (pinfunction "1_1") (pintype "passive"))
      (node (ref "C74") (pin "1") (pinfunction "1_1") (pintype "passive"))
      (node (ref "C75") (pin "1") (pinfunction "1_1") (pintype "passive"))
      (node (ref "C76") (pin "1") (pinfunction "1_1") (pintype "passive"))
      (node (ref "C77") (pin "1") (pinfunction "1_1") (pintype "passive"))
      (node (ref "C78") (pin "1") (pinfunction "1_1") (pintype "passive"))
      (node (ref "C79") (pin "1") (pinfunction "1_1") (pintype "passive"))
      (node (ref "C81") (pin "2") (pinfunction "2_2") (pintype "passive"))
      (node (ref "C82") (pin "2") (pinfunction "2_2") (pintype "passive"))
      (node (ref "C83") (pin "1") (pinfunction "1_1") (pintype "passive"))
      (node (ref "C84") (pin "1") (pinfunction "1_1") (pintype "passive"))
      (node (ref "C85") (pin "1") (pinfunction "1_1") (pintype "passive"))
      (node (ref "C86") (pin "2") (pinfunction "2_2") (pintype "passive"))
      (node (ref "C87") (pin "2") (pinfunction "2_2") (pintype "passive"))
      (node (ref "C90") (pin "2") (pinfunction "2_2") (pintype "passive"))
      (node (ref "C91") (pin "1") (pinfunction "1_1") (pintype "passive"))
      (node (ref "C92") (pin "2") (pinfunction "2_2") (pintype "passive"))
      (node (ref "C93") (pin "2") (pinfunction "2_2") (pintype "passive"))
      (node (ref "C94") (pin "2") (pinfunction "2_2") (pintype "passive"))
      (node (ref "DIGITAL_VOLT") (pin "1") (pinfunction "1_1") (pintype "bidirectional"))
      (node (ref "IC10") (pin "108") (pinfunction "VDD_8_108") (pintype "bidirectional"))
      (node (ref "IC10") (pin "121") (pinfunction "VDDSDMMC_121") (pintype "bidirectional"))
      (node (ref "IC10") (pin "131") (pinfunction "VDD_9_131") (pintype "bidirectional"))
      (node (ref "IC10") (pin "144") (pinfunction "VDD_10_144") (pintype "bidirectional"))
      (node (ref "IC10") (pin "17") (pinfunction "VDD_1_17") (pintype "bidirectional"))
      (node (ref "IC10") (pin "30") (pinfunction "VDD_2_30") (pintype "bidirectional"))
      (node (ref "IC10") (pin "39") (pinfunction "VDD_3_39") (pintype "bidirectional"))
      (node (ref "IC10") (pin "52") (pinfunction "VDD_4_52") (pintype "bidirectional"))
      (node (ref "IC10") (pin "6") (pinfunction "VBAT_6") (pintype "bidirectional"))
      (node (ref "IC10") (pin "62") (pinfunction "VDD_5_62") (pintype "bidirectional"))
      (node (ref "IC10") (pin "72") (pinfunction "VDD_6_72") (pintype "bidirectional"))
      (node (ref "IC10") (pin "84") (pinfunction "VDD_7_84") (pintype "bidirectional"))
      (node (ref "IC10") (pin "95") (pinfunction "VDDUSB_95") (pintype "bidirectional"))
      (node (ref "IC13") (pin "5") (pinfunction "VBUS_5") (pintype "bidirectional"))
      (node (ref "IC6") (pin "1") (pinfunction "VDD2A_1") (pintype "power_in"))
      (node (ref "IC6") (pin "19") (pinfunction "VDD1A_19") (pintype "power_in"))
      (node (ref "IC6") (pin "9") (pinfunction "VDDIO_9") (pintype "power_in"))
      (node (ref "R18") (pin "1") (pinfunction "1_1") (pintype "passive"))
      (node (ref "R20") (pin "1") (pinfunction "1_1") (pintype "passive"))
      (node (ref "R21") (pin "1") (pinfunction "1_1") (pintype "passive"))
      (node (ref "R22") (pin "1") (pinfunction "1_1") (pintype "passive"))
      (node (ref "R23") (pin "2") (pinfunction "2_2") (pintype "passive"))
      (node (ref "R45") (pin "2") (pinfunction "2_2") (pintype "passive"))
      (node (ref "R79") (pin "2") (pinfunction "2_2") (pintype "passive"))
      (node (ref "R80") (pin "2") (pinfunction "2_2") (pintype "passive"))
      (node (ref "R81") (pin "2") (pinfunction "2_2") (pintype "passive"))
      (node (ref "R82") (pin "2") (pinfunction "2_2") (pintype "passive"))
      (node (ref "R99") (pin "2") (pinfunction "2_2") (pintype "passive"))
      (node (ref "T1") (pin "2") (pinfunction "CT_1_2") (pintype "bidirectional"))
      (node (ref "T1") (pin "7") (pinfunction "CT_2_7") (pintype "bidirectional"))
    )
    (net (code "2") (name "+3V3_SIG") (class "Default")
      (node (ref "IC10") (pin "47") (pinfunction "PB1_47") (pintype "bidirectional"))
      (node (ref "R45") (pin "1") (pinfunction "1_1") (pintype "passive"))
      (node (ref "R65") (pin "2") (pinfunction "2_2") (pintype "passive"))
    )
    (net (code "3") (name "+5V") (class "Default")
      (node (ref "C14") (pin "1") (pinfunction "1_1") (pintype "passive"))
      (node (ref "C24") (pin "1") (pinfunction "1_1") (pintype "passive"))
      (node (ref "C31") (pin "1") (pinfunction "1_1") (pintype "passive"))
      (node (ref "C33") (pin "1") (pinfunction "1_1") (pintype "passive"))
      (node (ref "C34") (pin "1") (pinfunction "1_1") (pintype "passive"))
      (node (ref "C36") (pin "1") (pinfunction "1_1") (pintype "passive"))
      (node (ref "C41") (pin "1") (pinfunction "1_1") (pintype "passive"))
      (node (ref "DIGITAL_VOLT") (pin "4") (pinfunction "4_4") (pintype "bidirectional"))
      (node (ref "DISPLAY") (pin "3") (pinfunction "3_3") (pintype "bidirectional"))
      (node (ref "IC11") (pin "1") (pinfunction "AVCC_1_1") (pintype "bidirectional"))
      (node (ref "IC11") (pin "23") (pinfunction "VDRIVE_23") (pintype "bidirectional"))
      (node (ref "IC11") (pin "37") (pinfunction "AVCC_2_37") (pintype "bidirectional"))
      (node (ref "IC11") (pin "38") (pinfunction "AVCC_3_38") (pintype "bidirectional"))
      (node (ref "IC11") (pin "48") (pinfunction "AVCC_4_48") (pintype "bidirectional"))
      (node (ref "IC2") (pin "1") (pinfunction "VA_1") (pintype "bidirectional"))
      (node (ref "IC2") (pin "7") (pinfunction "VREFIN_7") (pintype "bidirectional"))
      (node (ref "IC3") (pin "1") (pinfunction "VA_1") (pintype "bidirectional"))
      (node (ref "R1") (pin "2") (pinfunction "2_2") (pintype "passive"))
      (node (ref "R100") (pin "2") (pinfunction "2_2") (pintype "passive"))
      (node (ref "R35") (pin "1") (pinfunction "1_1") (pintype "passive"))
      (node (ref "R86") (pin "2") (pinfunction "2_2") (pintype "passive"))
    )
    (net (code "4") (name "+5V_SIG") (class "Default")
      (node (ref "IC10") (pin "26") (pinfunction "PC0_26") (pintype "bidirectional"))
      (node (ref "R86") (pin "1") (pinfunction "1_1") (pintype "passive"))
      (node (ref "R87") (pin "2") (pinfunction "2_2") (pintype "passive"))
    )
    (net (code "5") (name "+12V") (class "Default")
      (node (ref "DIGITAL_VOLT") (pin "2") (pinfunction "2_2") (pintype "bidirectional"))
      (node (ref "K1") (pin "1") (pinfunction "1_1") (pintype "passive"))
      (node (ref "K2") (pin "1") (pinfunction "1_1") (pintype "passive"))
      (node (ref "K3") (pin "1") (pinfunction "1_1") (pintype "passive"))
      (node (ref "K4") (pin "1") (pinfunction "1_1") (pintype "passive"))
      (node (ref "K5") (pin "1") (pinfunction "1_1") (pintype "passive"))
      (node (ref "K6") (pin "1") (pinfunction "1_1") (pintype "passive"))
      (node (ref "K7") (pin "1") (pinfunction "1_1") (pintype "passive"))
      (node (ref "K8") (pin "1") (pinfunction "1_1") (pintype "passive"))
      (node (ref "LED1") (pin "2") (pinfunction "+_2") (pintype "passive"))
      (node (ref "LED2") (pin "2") (pinfunction "+_2") (pintype "passive"))
      (node (ref "LED3") (pin "2") (pinfunction "+_2") (pintype "passive"))
      (node (ref "LED4") (pin "2") (pinfunction "+_2") (pintype "passive"))
      (node (ref "LED5") (pin "2") (pinfunction "+_2") (pintype "passive"))
      (node (ref "LED6") (pin "2") (pinfunction "+_2") (pintype "passive"))
      (node (ref "LED7") (pin "2") (pinfunction "+_2") (pintype "passive"))
      (node (ref "LED8") (pin "2") (pinfunction "+_2") (pintype "passive"))
      (node (ref "R101") (pin "2") (pinfunction "2_2") (pintype "passive"))
      (node (ref "R39") (pin "2") (pinfunction "2_2") (pintype "passive"))
      (node (ref "U12") (pin "9") (pinfunction "COM_9") (pintype "bidirectional"))
    )
    (net (code "6") (name "+12V_SIG") (class "Default")
      (node (ref "IC10") (pin "42") (pinfunction "PA6_42") (pintype "bidirectional"))
      (node (ref "R39") (pin "1") (pinfunction "1_1") (pintype "passive"))
      (node (ref "R42") (pin "2") (pinfunction "2_2") (pintype "passive"))
    )
    (net (code "7") (name "+15V_SIG") (class "Default")
      (node (ref "IC10") (pin "34") (pinfunction "PA0_34") (pintype "bidirectional"))
      (node (ref "R3") (pin "1") (pinfunction "1_1") (pintype "passive"))
      (node (ref "R4") (pin "2") (pinfunction "2_2") (pintype "passive"))
    )
    (net (code "8") (name "-15V_SIG") (class "Default")
      (node (ref "IC10") (pin "37") (pinfunction "PA3_37") (pintype "bidirectional"))
      (node (ref "R1") (pin "1") (pinfunction "1_1") (pintype "passive"))
      (node (ref "R2") (pin "2") (pinfunction "2_2") (pintype "passive"))
    )
    (net (code "9") (name ".") (class "Default")
      (node (ref "IC14") (pin "1") (pinfunction "OUT_1") (pintype "output"))
      (node (ref "R59") (pin "2") (pinfunction "2_2") (pintype "passive"))
      (node (ref "R72") (pin "2") (pinfunction "2_2") (pintype "passive"))
    )
    (net (code "10") (name "...") (class "Default")
      (node (ref "IC7") (pin "1") (pinfunction "OUT_1") (pintype "output"))
      (node (ref "R71") (pin "2") (pinfunction "2_2") (pintype "passive"))
      (node (ref "R73") (pin "2") (pinfunction "2_2") (pintype "passive"))
    )
    (net (code "11") (name "0,5V_DAC") (class "Default")
      (node (ref "IC14") (pin "3") (pinfunction "+IN_3") (pintype "input"))
      (node (ref "IC15") (pin "1") (pinfunction "OUT_1") (pintype "output"))
      (node (ref "IC15") (pin "2") (pinfunction "-IN_2") (pintype "input"))
      (node (ref "IC7") (pin "3") (pinfunction "+IN_3") (pintype "input"))
    )
    (net (code "12") (name "1V_DAC") (class "Default")
      (node (ref "C22") (pin "1") (pinfunction "1_1") (pintype "passive"))
      (node (ref "C32") (pin "1") (pinfunction "1_1") (pintype "passive"))
      (node (ref "IC15") (pin "6") (pinfunction "-IN_6") (pintype "input"))
      (node (ref "IC15") (pin "7") (pinfunction "OUT_7") (pintype "output"))
      (node (ref "IC3") (pin "7") (pinfunction "VREFIN_7") (pintype "bidirectional"))
    )
    (net (code "13") (name "1V_DAC_UNBUFFERD") (class "Default")
      (node (ref "C19") (pin "1") (pinfunction "1_1") (pintype "passive"))
      (node (ref "C64") (pin "1") (pinfunction "1_1") (pintype "passive"))
      (node (ref "IC15") (pin "5") (pinfunction "+IN_5") (pintype "input"))
      (node (ref "R61") (pin "2") (pinfunction "2_2") (pintype "passive"))
      (node (ref "R68") (pin "1") (pinfunction "1_1") (pintype "passive"))
    )
    (net (code "14") (name "2V_DAC_REF") (class "Default")
      (node (ref "R67") (pin "1") (pinfunction "1_1") (pintype "passive"))
      (node (ref "R68") (pin "2") (pinfunction "2_2") (pintype "passive"))
      (node (ref "Z1") (pin "1") (pinfunction "K_1") (pintype "bidirectional"))
    )
    (net (code "15") (name "8MHZ_CRYSTAL_A") (class "Default")
      (node (ref "C70") (pin "1") (pinfunction "1_1") (pintype "passive"))
      (node (ref "IC10") (pin "23") (pinfunction "PH0_23") (pintype "bidirectional"))
      (node (ref "Y2") (pin "1") (pinfunction "1_1") (pintype "bidirectional"))
    )
    (net (code "16") (name "8MHZ_CRYSTAL_B") (class "Default")
      (node (ref "C69") (pin "1") (pinfunction "1_1") (pintype "passive"))
      (node (ref "IC10") (pin "24") (pinfunction "PH1_24") (pintype "bidirectional"))
      (node (ref "Y2") (pin "2") (pinfunction "2_2") (pintype "bidirectional"))
    )
    (net (code "17") (name "32.768KHZ_A") (class "Default")
      (node (ref "C66") (pin "1") (pinfunction "1_1") (pintype "passive"))
      (node (ref "IC10") (pin "8") (pinfunction "PC14_8") (pintype "bidirectional"))
      (node (ref "Y1") (pin "1") (pinfunction "1_1") (pintype "bidirectional"))
    )
    (net (code "18") (name "32.768KHZ_B") (class "Default")
      (node (ref "C65") (pin "1") (pinfunction "1_1") (pintype "passive"))
      (node (ref "IC10") (pin "9") (pinfunction "PC15_9") (pintype "bidirectional"))
      (node (ref "Y1") (pin "2") (pinfunction "2_2") (pintype "bidirectional"))
    )
    (net (code "19") (name "AGND") (class "Default")
      (node (ref "+12V_OK") (pin "1") (pinfunction "-_1") (pintype "passive"))
      (node (ref "+15V_OK") (pin "1") (pinfunction "-_1") (pintype "passive"))
      (node (ref "+3V3_OK") (pin "1") (pinfunction "-_1") (pintype "passive"))
      (node (ref "+5V_OK") (pin "1") (pinfunction "-_1") (pintype "passive"))
      (node (ref "-15V_OK") (pin "1") (pinfunction "-_1") (pintype "passive"))
      (node (ref "C1") (pin "2") (pinfunction "2_2") (pintype "passive"))
      (node (ref "C100") (pin "1") (pinfunction "1_1") (pintype "passive"))
      (node (ref "C104") (pin "2") (pinfunction "2_2") (pintype "passive"))
      (node (ref "C11") (pin "2") (pinfunction "2_2") (pintype "passive"))
      (node (ref "C12") (pin "2") (pinfunction "2_2") (pintype "passive"))
      (node (ref "C13") (pin "2") (pinfunction "2_2") (pintype "passive"))
      (node (ref "C14") (pin "2") (pinfunction "2_2") (pintype "passive"))
      (node (ref "C19") (pin "2") (pinfunction "2_2") (pintype "passive"))
      (node (ref "C2") (pin "2") (pinfunction "2_2") (pintype "passive"))
      (node (ref "C20") (pin "2") (pinfunction "2_2") (pintype "passive"))
      (node (ref "C21") (pin "2") (pinfunction "2_2") (pintype "passive"))
      (node (ref "C22") (pin "2") (pinfunction "2_2") (pintype "passive"))
      (node (ref "C23") (pin "2") (pinfunction "2_2") (pintype "passive"))
      (node (ref "C24") (pin "2") (pinfunction "2_2") (pintype "passive"))
      (node (ref "C25") (pin "2") (pinfunction "2_2") (pintype "passive"))
      (node (ref "C26") (pin "2") (pinfunction "2_2") (pintype "passive"))
      (node (ref "C27") (pin "2") (pinfunction "2_2") (pintype "passive"))
      (node (ref "C28") (pin "2") (pinfunction "2_2") (pintype "passive"))
      (node (ref "C29") (pin "2") (pinfunction "2_2") (pintype "passive"))
      (node (ref "C3") (pin "2") (pinfunction "2_2") (pintype "passive"))
      (node (ref "C30") (pin "2") (pinfunction "2_2") (pintype "passive"))
      (node (ref "C31") (pin "2") (pinfunction "2_2") (pintype "passive"))
      (node (ref "C32") (pin "2") (pinfunction "2_2") (pintype "passive"))
      (node (ref "C33") (pin "2") (pinfunction "2_2") (pintype "passive"))
      (node (ref "C34") (pin "2") (pinfunction "2_2") (pintype "passive"))
      (node (ref "C35") (pin "2") (pinfunction "2_2") (pintype "passive"))
      (node (ref "C36") (pin "2") (pinfunction "2_2") (pintype "passive"))
      (node (ref "C39") (pin "2") (pinfunction "2_2") (pintype "passive"))
      (node (ref "C4") (pin "2") (pinfunction "2_2") (pintype "passive"))
      (node (ref "C40") (pin "1") (pinfunction "1_1") (pintype "passive"))
      (node (ref "C41") (pin "2") (pinfunction "2_2") (pintype "passive"))
      (node (ref "C42") (pin "2") (pinfunction "2_2") (pintype "passive"))
      (node (ref "C43") (pin "2") (pinfunction "2_2") (pintype "passive"))
      (node (ref "C44") (pin "1") (pinfunction "1_1") (pintype "passive"))
      (node (ref "C45") (pin "2") (pinfunction "2_2") (pintype "passive"))
      (node (ref "C46") (pin "2") (pinfunction "2_2") (pintype "passive"))
      (node (ref "C47") (pin "2") (pinfunction "2_2") (pintype "passive"))
      (node (ref "C48") (pin "2") (pinfunction "2_2") (pintype "passive"))
      (node (ref "C49") (pin "2") (pinfunction "2_2") (pintype "passive"))
      (node (ref "C5") (pin "2") (pinfunction "2_2") (pintype "passive"))
      (node (ref "C50") (pin "2") (pinfunction "2_2") (pintype "passive"))
      (node (ref "C51") (pin "2") (pinfunction "2_2") (pintype "passive"))
      (node (ref "C52") (pin "2") (pinfunction "2_2") (pintype "passive"))
      (node (ref "C53") (pin "2") (pinfunction "2_2") (pintype "passive"))
      (node (ref "C54") (pin "2") (pinfunction "2_2") (pintype "passive"))
      (node (ref "C57") (pin "2") (pinfunction "2_2") (pintype "passive"))
      (node (ref "C58") (pin "2") (pinfunction "2_2") (pintype "passive"))
      (node (ref "C59") (pin "2") (pinfunction "2_2") (pintype "passive"))
      (node (ref "C6") (pin "2") (pinfunction "2_2") (pintype "passive"))
      (node (ref "C60") (pin "2") (pinfunction "2_2") (pintype "passive"))
      (node (ref "C61") (pin "2") (pinfunction "2_2") (pintype "passive"))
      (node (ref "C62") (pin "2") (pinfunction "2_2") (pintype "passive"))
      (node (ref "C63") (pin "2") (pinfunction "2_2") (pintype "passive"))
      (node (ref "C64") (pin "2") (pinfunction "2_2") (pintype "passive"))
      (node (ref "C65") (pin "2") (pinfunction "2_2") (pintype "passive"))
      (node (ref "C66") (pin "2") (pinfunction "2_2") (pintype "passive"))
      (node (ref "C68") (pin "2") (pinfunction "2_2") (pintype "passive"))
      (node (ref "C69") (pin "2") (pinfunction "2_2") (pintype "passive"))
      (node (ref "C7") (pin "2") (pinfunction "2_2") (pintype "passive"))
      (node (ref "C70") (pin "2") (pinfunction "2_2") (pintype "passive"))
      (node (ref "C71") (pin "2") (pinfunction "2_2") (pintype "passive"))
      (node (ref "C72") (pin "2") (pinfunction "2_2") (pintype "passive"))
      (node (ref "C73") (pin "2") (pinfunction "2_2") (pintype "passive"))
      (node (ref "C74") (pin "2") (pinfunction "2_2") (pintype "passive"))
      (node (ref "C75") (pin "2") (pinfunction "2_2") (pintype "passive"))
      (node (ref "C76") (pin "2") (pinfunction "2_2") (pintype "passive"))
      (node (ref "C77") (pin "2") (pinfunction "2_2") (pintype "passive"))
      (node (ref "C78") (pin "2") (pinfunction "2_2") (pintype "passive"))
      (node (ref "C79") (pin "2") (pinfunction "2_2") (pintype "passive"))
      (node (ref "C8") (pin "2") (pinfunction "2_2") (pintype "passive"))
      (node (ref "C80") (pin "1") (pinfunction "1_1") (pintype "passive"))
      (node (ref "C81") (pin "1") (pinfunction "1_1") (pintype "passive"))
      (node (ref "C82") (pin "1") (pinfunction "1_1") (pintype "passive"))
      (node (ref "C83") (pin "2") (pinfunction "2_2") (pintype "passive"))
      (node (ref "C84") (pin "2") (pinfunction "2_2") (pintype "passive"))
      (node (ref "C85") (pin "2") (pinfunction "2_2") (pintype "passive"))
      (node (ref "C86") (pin "1") (pinfunction "1_1") (pintype "passive"))
      (node (ref "C87") (pin "1") (pinfunction "1_1") (pintype "passive"))
      (node (ref "C88") (pin "1") (pinfunction "1_1") (pintype "passive"))
      (node (ref "C89") (pin "1") (pinfunction "1_1") (pintype "passive"))
      (node (ref "C90") (pin "1") (pinfunction "1_1") (pintype "passive"))
      (node (ref "C91") (pin "2") (pinfunction "2_2") (pintype "passive"))
      (node (ref "C92") (pin "1") (pinfunction "1_1") (pintype "passive"))
      (node (ref "C93") (pin "1") (pinfunction "1_1") (pintype "passive"))
      (node (ref "C94") (pin "1") (pinfunction "1_1") (pintype "passive"))
      (node (ref "C95") (pin "2") (pinfunction "2_2") (pintype "passive"))
      (node (ref "C96") (pin "2") (pinfunction "2_2") (pintype "passive"))
      (node (ref "C97") (pin "2") (pinfunction "2_2") (pintype "passive"))
      (node (ref "C98") (pin "2") (pinfunction "2_2") (pintype "passive"))
      (node (ref "C99") (pin "2") (pinfunction "2_2") (pintype "passive"))
      (node (ref "IC10") (pin "107") (pinfunction "VSS_7_107") (pintype "bidirectional"))
      (node (ref "IC10") (pin "120") (pinfunction "VSS_8_120") (pintype "bidirectional"))
      (node (ref "IC10") (pin "130") (pinfunction "VSS_9_130") (pintype "bidirectional"))
      (node (ref "IC10") (pin "16") (pinfunction "VSS_1_16") (pintype "bidirectional"))
      (node (ref "IC10") (pin "31") (pinfunction "VSSA_31") (pintype "bidirectional"))
      (node (ref "IC10") (pin "38") (pinfunction "VSS_2_38") (pintype "bidirectional"))
      (node (ref "IC10") (pin "51") (pinfunction "VSS_3_51") (pintype "bidirectional"))
      (node (ref "IC10") (pin "61") (pinfunction "VSS_4_61") (pintype "bidirectional"))
      (node (ref "IC10") (pin "83") (pinfunction "VSS_5_83") (pintype "bidirectional"))
      (node (ref "IC10") (pin "94") (pinfunction "VSS_6_94") (pintype "bidirectional"))
      (node (ref "IC11") (pin "2") (pinfunction "AGND_1_2") (pintype "bidirectional"))
      (node (ref "IC11") (pin "26") (pinfunction "AGND_2_26") (pintype "bidirectional"))
      (node (ref "IC11") (pin "40") (pinfunction "AGND_4_40") (pintype "bidirectional"))
      (node (ref "IC11") (pin "41") (pinfunction "AGND_5_41") (pintype "bidirectional"))
      (node (ref "IC11") (pin "43") (pinfunction "REFGND_1_43") (pintype "bidirectional"))
      (node (ref "IC11") (pin "46") (pinfunction "REFGND_2_46") (pintype "bidirectional"))
      (node (ref "IC11") (pin "47") (pinfunction "AGND_6_47") (pintype "bidirectional"))
      (node (ref "IC11") (pin "50") (pinfunction "V1GND_50") (pintype "bidirectional"))
      (node (ref "IC11") (pin "52") (pinfunction "V2GND_52") (pintype "bidirectional"))
      (node (ref "IC11") (pin "54") (pinfunction "V3GND_54") (pintype "bidirectional"))
      (node (ref "IC11") (pin "56") (pinfunction "V4GND_56") (pintype "bidirectional"))
      (node (ref "IC11") (pin "58") (pinfunction "V5GND_58") (pintype "bidirectional"))
      (node (ref "IC11") (pin "60") (pinfunction "V6GND_60") (pintype "bidirectional"))
      (node (ref "IC11") (pin "62") (pinfunction "V7GND_62") (pintype "bidirectional"))
      (node (ref "IC11") (pin "64") (pinfunction "V8GND_64") (pintype "bidirectional"))
      (node (ref "IC12") (pin "2") (pinfunction "2_2") (pintype "bidirectional"))
      (node (ref "IC12") (pin "5") (pinfunction "5_5") (pintype "bidirectional"))
      (node (ref "IC13") (pin "2") (pinfunction "GND_2") (pintype "power_in"))
      (node (ref "IC2") (pin "6") (pinfunction "GND_6") (pintype "bidirectional"))
      (node (ref "IC3") (pin "6") (pinfunction "GND_6") (pintype "bidirectional"))
      (node (ref "IC5") (pin "3") (pinfunction "+IN_3") (pintype "input"))
      (node (ref "IC5") (pin "5") (pinfunction "+IN_5") (pintype "input"))
      (node (ref "IC6") (pin "25") (pinfunction "EP_VSS_25") (pintype "power_in"))
      (node (ref "IC8") (pin "3") (pinfunction "+IN_3") (pintype "input"))
      (node (ref "IC8") (pin "5") (pinfunction "+IN_5") (pintype "input"))
      (node (ref "IN1(R/S)") (pin "1") (pinfunction "1_1") (pintype "bidirectional"))
      (node (ref "IN2(L/M)") (pin "1") (pinfunction "1_1") (pintype "bidirectional"))
      (node (ref "IN_LEFT") (pin "1") (pinfunction "REF_1") (pintype "passive"))
      (node (ref "IN_RIGHT") (pin "1") (pinfunction "REF_1") (pintype "passive"))
      (node (ref "OUT1(R/S)") (pin "1") (pinfunction "1_1") (pintype "bidirectional"))
      (node (ref "OUT2(L/M)") (pin "1") (pinfunction "1_1") (pintype "bidirectional"))
      (node (ref "OUT_LEFT") (pin "3") (pinfunction "GND_3") (pintype "input"))
      (node (ref "OUT_RIGHT") (pin "3") (pinfunction "GND_3") (pintype "input"))
      (node (ref "PROG.") (pin "4") (pinfunction "4_4") (pintype "bidirectional"))
      (node (ref "R13") (pin "1") (pinfunction "1_1") (pintype "passive"))
      (node (ref "R14") (pin "2") (pinfunction "2_2") (pintype "passive"))
      (node (ref "R15") (pin "2") (pinfunction "2_2") (pintype "passive"))
      (node (ref "R16") (pin "2") (pinfunction "2_2") (pintype "passive"))
      (node (ref "R17") (pin "2") (pinfunction "2_2") (pintype "passive"))
      (node (ref "R27") (pin "1") (pinfunction "1_1") (pintype "passive"))
      (node (ref "R4") (pin "1") (pinfunction "1_1") (pintype "passive"))
      (node (ref "R42") (pin "1") (pinfunction "1_1") (pintype "passive"))
      (node (ref "R46") (pin "1") (pinfunction "1_1") (pintype "passive"))
      (node (ref "R47") (pin "1") (pinfunction "1_1") (pintype "passive"))
      (node (ref "R5") (pin "1") (pinfunction "1_1") (pintype "passive"))
      (node (ref "R58") (pin "1") (pinfunction "1_1") (pintype "passive"))
      (node (ref "R6") (pin "1") (pinfunction "1_1") (pintype "passive"))
      (node (ref "R60") (pin "1") (pinfunction "1_1") (pintype "passive"))
      (node (ref "R65") (pin "1") (pinfunction "1_1") (pintype "passive"))
      (node (ref "R69") (pin "2") (pinfunction "2_2") (pintype "passive"))
      (node (ref "R76") (pin "1") (pinfunction "1_1") (pintype "passive"))
      (node (ref "R77") (pin "2") (pinfunction "2_2") (pintype "passive"))
      (node (ref "R78") (pin "2") (pinfunction "2_2") (pintype "passive"))
      (node (ref "R83") (pin "1") (pinfunction "1_1") (pintype "passive"))
      (node (ref "R84") (pin "1") (pinfunction "1_1") (pintype "passive"))
      (node (ref "R85") (pin "1") (pinfunction "1_1") (pintype "passive"))
      (node (ref "R87") (pin "1") (pinfunction "1_1") (pintype "passive"))
      (node (ref "S1") (pin "1") (pinfunction "1_1") (pintype "bidirectional"))
      (node (ref "S1") (pin "2") (pinfunction "2_2") (pintype "bidirectional"))
      (node (ref "STAGE(LEFT)") (pin "3") (pinfunction "EC-_3") (pintype "output"))
      (node (ref "STAGE(LEFT)") (pin "6") (pinfunction "GND_6") (pintype "passive"))
      (node (ref "STAGE(RIGHT)") (pin "3") (pinfunction "EC-_3") (pintype "output"))
      (node (ref "STAGE(RIGHT)") (pin "6") (pinfunction "GND_6") (pintype "passive"))
      (node (ref "U12") (pin "8") (pinfunction "GND_8") (pintype "bidirectional"))
      (node (ref "U4") (pin "2") (pinfunction "IN-_2") (pintype "input"))
      (node (ref "U6") (pin "1") (pinfunction "REF_1") (pintype "passive"))
      (node (ref "U7") (pin "2") (pinfunction "IN-_2") (pintype "input"))
      (node (ref "U8") (pin "1") (pinfunction "REF_1") (pintype "passive"))
      (node (ref "VCA1(LEFT)") (pin "3") (pinfunction "EC-_3") (pintype "output"))
      (node (ref "VCA1(LEFT)") (pin "6") (pinfunction "GND_6") (pintype "passive"))
      (node (ref "VCA2(RIGHT)") (pin "3") (pinfunction "EC-_3") (pintype "output"))
      (node (ref "VCA2(RIGHT)") (pin "6") (pinfunction "GND_6") (pintype "passive"))
      (node (ref "X1") (pin "4") (pinfunction "4_4") (pintype "bidirectional"))
      (node (ref "Z1") (pin "2") (pinfunction "A_2") (pintype "bidirectional"))
    )
    (net (code "20") (name "A_GND_TO_STAR") (class "Default")
      (node (ref "ANALOG_VOLT") (pin "3") (pinfunction "3_3") (pintype "bidirectional"))
      (node (ref "ANALOG_VOLT") (pin "4") (pinfunction "4_4") (pintype "bidirectional"))
      (node (ref "R16") (pin "1") (pinfunction "1_1") (pintype "passive"))
    )
    (net (code "21") (name "BOOT0") (class "Default")
      (node (ref "IC10") (pin "138") (pinfunction "BOOT0_138") (pintype "bidirectional"))
      (node (ref "R78") (pin "1") (pinfunction "1_1") (pintype "passive"))
    )
    (net (code "22") (name "BUSY") (class "Default")
      (node (ref "IC10") (pin "88") (pinfunction "PG3_88") (pintype "bidirectional"))
      (node (ref "IC11") (pin "14") (pinfunction "BUSY_14") (pintype "bidirectional"))
    )
    (net (code "23") (name "CHASIS") (class "Default")
      (node (ref "C15") (pin "1") (pinfunction "1_1") (pintype "passive"))
      (node (ref "C18") (pin "1") (pinfunction "1_1") (pintype "passive"))
      (node (ref "OUT1(R/S)") (pin "G") (pinfunction "G_G") (pintype "bidirectional"))
      (node (ref "OUT2(L/M)") (pin "G") (pinfunction "G_G") (pintype "bidirectional"))
      (node (ref "R17") (pin "1") (pinfunction "1_1") (pintype "passive"))
      (node (ref "R91") (pin "1") (pinfunction "1_1") (pintype "passive"))
      (node (ref "X1") (pin "P$1") (pinfunction "P$1_P$1") (pintype "bidirectional"))
      (node (ref "X1") (pin "P$2") (pinfunction "P$2_P$2") (pintype "bidirectional"))
    )
    (net (code "24") (name "CS") (class "Default")
      (node (ref "IC10") (pin "123") (pinfunction "PD7_123") (pintype "bidirectional"))
      (node (ref "IC11") (pin "13") (pinfunction "~{CS}_13") (pintype "bidirectional"))
    )
    (net (code "25") (name "CS_DAC1") (class "Default")
      (node (ref "IC10") (pin "134") (pinfunction "PB4_134") (pintype "bidirectional"))
      (node (ref "R94") (pin "2") (pinfunction "2_2") (pintype "passive"))
    )
    (net (code "26") (name "CS_DAC2") (class "Default")
      (node (ref "IC10") (pin "135") (pinfunction "PB5_135") (pintype "bidirectional"))
      (node (ref "R95") (pin "2") (pinfunction "2_2") (pintype "passive"))
    )
    (net (code "27") (name "CV_A_B") (class "Default")
      (node (ref "IC10") (pin "113") (pinfunction "PC12_113") (pintype "bidirectional"))
      (node (ref "IC11") (pin "10") (pinfunction "~{WR}_10") (pintype "bidirectional"))
      (node (ref "IC11") (pin "9") (pinfunction "CONVST_9") (pintype "bidirectional"))
    )
    (net (code "28") (name "DAC2_OUT1(OFFSET_VCA1)") (class "Default")
      (node (ref "C99") (pin "1") (pinfunction "1_1") (pintype "passive"))
      (node (ref "IC9") (pin "3") (pinfunction "+IN_3") (pintype "input"))
      (node (ref "R74") (pin "2") (pinfunction "2_2") (pintype "passive"))
      (node (ref "R76") (pin "2") (pinfunction "2_2") (pintype "passive"))
    )
    (net (code "29") (name "DAC2_OUT2(OFFSET_VCA2)") (class "Default")
      (node (ref "C39") (pin "1") (pinfunction "1_1") (pintype "passive"))
      (node (ref "IC9") (pin "5") (pinfunction "+IN_5") (pintype "input"))
      (node (ref "R47") (pin "2") (pinfunction "2_2") (pintype "passive"))
      (node (ref "R75") (pin "2") (pinfunction "2_2") (pintype "passive"))
    )
    (net (code "30") (name "DAC2_OUT3") (class "Default")
      (node (ref "IC3") (pin "4") (pinfunction "VOUTC_4") (pintype "bidirectional"))
      (node (ref "R62") (pin "1") (pinfunction "1_1") (pintype "passive"))
    )
    (net (code "31") (name "DAC2_OUT4") (class "Default")
      (node (ref "IC3") (pin "5") (pinfunction "VOUTD_5") (pintype "bidirectional"))
      (node (ref "R70") (pin "1") (pinfunction "1_1") (pintype "passive"))
    )
    (net (code "32") (name "DAC_OUT1") (class "Default")
      (node (ref "IC10") (pin "40") (pinfunction "PA4_40") (pintype "bidirectional"))
      (node (ref "R57") (pin "1") (pinfunction "1_1") (pintype "passive"))
    )
    (net (code "33") (name "DAC_OUT2") (class "Default")
      (node (ref "IC10") (pin "41") (pinfunction "PA5_41") (pintype "bidirectional"))
      (node (ref "R55") (pin "1") (pinfunction "1_1") (pintype "passive"))
    )
    (net (code "34") (name "DB0") (class "Default")
      (node (ref "IC10") (pin "141") (pinfunction "PE0_141") (pintype "bidirectional"))
      (node (ref "IC11") (pin "16") (pinfunction "DB0_16") (pintype "bidirectional"))
    )
    (net (code "35") (name "DB1") (class "Default")
      (node (ref "IC10") (pin "142") (pinfunction "PE1_142") (pintype "bidirectional"))
      (node (ref "IC11") (pin "17") (pinfunction "DB1_17") (pintype "bidirectional"))
    )
    (net (code "36") (name "DB2") (class "Default")
      (node (ref "IC10") (pin "1") (pinfunction "PE2_1") (pintype "bidirectional"))
      (node (ref "IC11") (pin "18") (pinfunction "DB2_18") (pintype "bidirectional"))
    )
    (net (code "37") (name "DB3") (class "Default")
      (node (ref "IC10") (pin "2") (pinfunction "PE3_2") (pintype "bidirectional"))
      (node (ref "IC11") (pin "19") (pinfunction "DB3_19") (pintype "bidirectional"))
    )
    (net (code "38") (name "DB4") (class "Default")
      (node (ref "IC10") (pin "3") (pinfunction "PE4_3") (pintype "bidirectional"))
      (node (ref "IC11") (pin "20") (pinfunction "DB4_20") (pintype "bidirectional"))
    )
    (net (code "39") (name "DB5") (class "Default")
      (node (ref "IC10") (pin "4") (pinfunction "PE5_4") (pintype "bidirectional"))
      (node (ref "IC11") (pin "21") (pinfunction "DB5_21") (pintype "bidirectional"))
    )
    (net (code "40") (name "DB6") (class "Default")
      (node (ref "IC10") (pin "5") (pinfunction "PE6_5") (pintype "bidirectional"))
      (node (ref "IC11") (pin "22") (pinfunction "DB6_22") (pintype "bidirectional"))
    )
    (net (code "41") (name "DB7") (class "Default")
      (node (ref "IC10") (pin "58") (pinfunction "PE7_58") (pintype "bidirectional"))
      (node (ref "IC11") (pin "24") (pinfunction "DB7/DOUTA_24") (pintype "bidirectional"))
    )
    (net (code "42") (name "DB8") (class "Default")
      (node (ref "IC10") (pin "59") (pinfunction "PE8_59") (pintype "bidirectional"))
      (node (ref "IC11") (pin "25") (pinfunction "DB8/DOUTB_25") (pintype "bidirectional"))
    )
    (net (code "43") (name "DB9") (class "Default")
      (node (ref "IC10") (pin "60") (pinfunction "PE9_60") (pintype "bidirectional"))
      (node (ref "IC11") (pin "27") (pinfunction "DB9/DOUTC_27") (pintype "bidirectional"))
    )
    (net (code "44") (name "DB10") (class "Default")
      (node (ref "IC10") (pin "63") (pinfunction "PE10_63") (pintype "bidirectional"))
      (node (ref "IC11") (pin "28") (pinfunction "DB10/DOUTD_28") (pintype "bidirectional"))
    )
    (net (code "45") (name "DB11") (class "Default")
      (node (ref "IC10") (pin "64") (pinfunction "PE11_64") (pintype "bidirectional"))
      (node (ref "IC11") (pin "29") (pinfunction "DB11/SDI_29") (pintype "bidirectional"))
    )
    (net (code "46") (name "DB12") (class "Default")
      (node (ref "IC10") (pin "65") (pinfunction "PE12_65") (pintype "bidirectional"))
      (node (ref "IC11") (pin "30") (pinfunction "DB12_30") (pintype "bidirectional"))
    )
    (net (code "47") (name "DB13") (class "Default")
      (node (ref "IC10") (pin "66") (pinfunction "PE13_66") (pintype "bidirectional"))
      (node (ref "IC11") (pin "31") (pinfunction "DB13_31") (pintype "bidirectional"))
    )
    (net (code "48") (name "DB14") (class "Default")
      (node (ref "IC10") (pin "67") (pinfunction "PE14_67") (pintype "bidirectional"))
      (node (ref "IC11") (pin "32") (pinfunction "DB14_32") (pintype "bidirectional"))
    )
    (net (code "49") (name "DB15") (class "Default")
      (node (ref "IC10") (pin "68") (pinfunction "PE15_68") (pintype "bidirectional"))
      (node (ref "IC11") (pin "33") (pinfunction "DB15_33") (pintype "bidirectional"))
    )
    (net (code "50") (name "DEBUG1") (class "Default")
      (node (ref "DEBUG1") (pin "P$1") (pinfunction "TP_P$1") (pintype "input"))
      (node (ref "IC10") (pin "21") (pinfunction "PF9_21") (pintype "bidirectional"))
    )
    (net (code "51") (name "DEBUG2") (class "Default")
      (node (ref "DEBUG2") (pin "P$1") (pinfunction "TP_P$1") (pintype "input"))
      (node (ref "IC10") (pin "115") (pinfunction "PD1_115") (pintype "bidirectional"))
    )
    (net (code "52") (name "DIN_DAC") (class "Default")
      (node (ref "IC10") (pin "29") (pinfunction "PC3_29") (pintype "bidirectional"))
      (node (ref "R93") (pin "2") (pinfunction "2_2") (pintype "passive"))
    )
    (net (code "53") (name "DISPLAY_GND_TO_STAR") (class "Default")
      (node (ref "DISPLAY") (pin "4") (pinfunction "4_4") (pintype "bidirectional"))
      (node (ref "R69") (pin "1") (pinfunction "1_1") (pintype "passive"))
    )
    (net (code "54") (name "D_GND_TO_STAR") (class "Default")
      (node (ref "DIGITAL_VOLT") (pin "3") (pinfunction "3_3") (pintype "bidirectional"))
      (node (ref "R15") (pin "1") (pinfunction "1_1") (pintype "passive"))
    )
    (net (code "55") (name "E+_OUT_STAGE_LEFT") (class "Default")
      (node (ref "IC7") (pin "6") (pinfunction "-IN_6") (pintype "input"))
      (node (ref "IC7") (pin "7") (pinfunction "OUT_7") (pintype "output"))
      (node (ref "STAGE(LEFT)") (pin "2") (pinfunction "EC+_2") (pintype "passive"))
      (node (ref "TP02") (pin "P$1") (pinfunction "TP_P$1") (pintype "input"))
    )
    (net (code "56") (name "E+_OUT_STAGE_RIGHT") (class "Default")
      (node (ref "IC14") (pin "6") (pinfunction "-IN_6") (pintype "input"))
      (node (ref "IC14") (pin "7") (pinfunction "OUT_7") (pintype "output"))
      (node (ref "STAGE(RIGHT)") (pin "2") (pinfunction "EC+_2") (pintype "passive"))
      (node (ref "TP01") (pin "P$1") (pinfunction "TP_P$1") (pintype "input"))
    )
    (net (code "57") (name "EC+_VCA1(LFT)") (class "Default")
      (node (ref "IC9") (pin "1") (pinfunction "OUT_1") (pintype "output"))
      (node (ref "R56") (pin "2") (pinfunction "2_2") (pintype "passive"))
      (node (ref "TP37") (pin "P$1") (pinfunction "TP_P$1") (pintype "input"))
      (node (ref "VCA1(LEFT)") (pin "2") (pinfunction "EC+_2") (pintype "passive"))
    )
    (net (code "58") (name "EC+_VCA2(RIGHT)") (class "Default")
      (node (ref "IC9") (pin "7") (pinfunction "OUT_7") (pintype "output"))
      (node (ref "R54") (pin "2") (pinfunction "2_2") (pintype "passive"))
      (node (ref "TP36") (pin "P$1") (pinfunction "TP_P$1") (pintype "input"))
      (node (ref "VCA2(RIGHT)") (pin "2") (pinfunction "EC+_2") (pintype "passive"))
    )
    (net (code "59") (name "FRST") (class "Default")
      (node (ref "IC10") (pin "122") (pinfunction "PD6_122") (pintype "bidirectional"))
      (node (ref "IC11") (pin "15") (pinfunction "FRSTDATA_15") (pintype "bidirectional"))
    )
    (net (code "60") (name "L") (class "Default")
      (node (ref "IC4") (pin "3") (pinfunction "+IN_3") (pintype "input"))
      (node (ref "IN_LEFT") (pin "5") (pinfunction "SEN_5") (pintype "output"))
      (node (ref "IN_LEFT") (pin "6") (pinfunction "OUT_6") (pintype "output"))
      (node (ref "K5") (pin "Q1") (pinfunction "O_Q1") (pintype "passive"))
    )
    (net (code "61") (name "LD1") (class "Default")
      (node (ref "IC10") (pin "46") (pinfunction "PB0_46") (pintype "bidirectional"))
      (node (ref "LD1") (pin "2") (pinfunction "+_2") (pintype "passive"))
    )
    (net (code "62") (name "LD2") (class "Default")
      (node (ref "IC10") (pin "137") (pinfunction "PB7_137") (pintype "bidirectional"))
      (node (ref "LD2") (pin "2") (pinfunction "+_2") (pintype "passive"))
    )
    (net (code "63") (name "LD3") (class "Default")
      (node (ref "IC10") (pin "75") (pinfunction "PB14_75") (pintype "bidirectional"))
      (node (ref "LD3") (pin "2") (pinfunction "+_2") (pintype "passive"))
    )
    (net (code "64") (name "LED1") (class "Default")
      (node (ref "IC6") (pin "3") (pinfunction "LED1/NINT/NPME/~{REGOFF}_3") (pintype "input"))
      (node (ref "J1") (pin "10") (pinfunction "YELLOW_A_10") (pintype "bidirectional"))
      (node (ref "R85") (pin "2") (pinfunction "2_2") (pintype "passive"))
    )
    (net (code "65") (name "LED2") (class "Default")
      (node (ref "IC6") (pin "2") (pinfunction "LED2/NINT/NPME/~{NINTSEL}_2") (pintype "input"))
      (node (ref "J1") (pin "12") (pinfunction "GREEN_A_12") (pintype "bidirectional"))
    )
    (net (code "66") (name "L{slash}M_IN(VCA1_IN)") (class "Default")
      (node (ref "C102") (pin "1") (pinfunction "1_1") (pintype "passive"))
      (node (ref "IC11") (pin "49") (pinfunction "V1_49") (pintype "bidirectional"))
      (node (ref "K5") (pin "P1") (pinfunction "P_P1") (pintype "passive"))
    )
    (net (code "67") (name "L{slash}M_OUT(OUT_STAGE_LEFT)") (class "Default")
      (node (ref "C38") (pin "2") (pinfunction "2_2") (pintype "passive"))
      (node (ref "IC1") (pin "3") (pinfunction "+IN_3") (pintype "input"))
      (node (ref "IC11") (pin "57") (pinfunction "V5_57") (pintype "bidirectional"))
      (node (ref "IC5") (pin "1") (pinfunction "OUT_1") (pintype "output"))
      (node (ref "K6") (pin "Q1") (pinfunction "O_Q1") (pintype "passive"))
      (node (ref "R28") (pin "2") (pinfunction "2_2") (pintype "passive"))
    )
    (net (code "68") (name "L{slash}M_OUT(VCA1_OUT)") (class "Default")
      (node (ref "C55") (pin "2") (pinfunction "2_2") (pintype "passive"))
      (node (ref "IC11") (pin "53") (pinfunction "V3_53") (pintype "bidirectional"))
      (node (ref "IC8") (pin "1") (pinfunction "OUT_1") (pintype "output"))
      (node (ref "R36") (pin "1") (pinfunction "1_1") (pintype "passive"))
      (node (ref "R48") (pin "2") (pinfunction "2_2") (pintype "passive"))
    )
    (net (code "69") (name "M") (class "Default")
      (node (ref "K5") (pin "S1") (pinfunction "S_S1") (pintype "passive"))
      (node (ref "U4") (pin "5") (pinfunction "SEN_5") (pintype "output"))
      (node (ref "U4") (pin "6") (pinfunction "OUT_6") (pintype "output"))
    )
    (net (code "70") (name "N$4") (class "Default")
      (node (ref "IC11") (pin "61") (pinfunction "V7_61") (pintype "bidirectional"))
    )
    (net (code "71") (name "N$47") (class "Default")
      (node (ref "IC11") (pin "63") (pinfunction "V8_63") (pintype "bidirectional"))
    )
    (net (code "72") (name "NEGATIVE_IN(L{slash}M)") (class "Default")
      (node (ref "IN2(L/M)") (pin "3") (pinfunction "3_3") (pintype "bidirectional"))
      (node (ref "K4") (pin "P1") (pinfunction "P_P1") (pintype "passive"))
    )
    (net (code "73") (name "NEGATIVE_IN(R{slash}S)") (class "Default")
      (node (ref "IN1(R/S)") (pin "3") (pinfunction "3_3") (pintype "bidirectional"))
      (node (ref "K1") (pin "P1") (pinfunction "P_P1") (pintype "passive"))
    )
    (net (code "74") (name "NEGATIVE_OUT(L{slash}M)") (class "Default")
      (node (ref "K3") (pin "P1") (pinfunction "P_P1") (pintype "passive"))
      (node (ref "OUT2(L/M)") (pin "3") (pinfunction "3_3") (pintype "bidirectional"))
    )
    (net (code "75") (name "NGATIVE_OUT(R{slash}S)") (class "Default")
      (node (ref "K2") (pin "P1") (pinfunction "P_P1") (pintype "passive"))
      (node (ref "OUT1(R/S)") (pin "3") (pinfunction "3_3") (pintype "bidirectional"))
    )
    (net (code "76") (name "NRST") (class "Default")
      (node (ref "C44") (pin "2") (pinfunction "2_2") (pintype "passive"))
      (node (ref "IC10") (pin "25") (pinfunction "NRST_25") (pintype "bidirectional"))
      (node (ref "IC6") (pin "15") (pinfunction "NRST_15") (pintype "input"))
      (node (ref "PROG.") (pin "2") (pinfunction "2_2") (pintype "bidirectional"))
      (node (ref "S1") (pin "3") (pinfunction "3_3") (pintype "bidirectional"))
      (node (ref "S1") (pin "4") (pinfunction "4_4") (pintype "bidirectional"))
    )
    (net (code "77") (name "Net-(+3V3_OK-+)") (class "Default")
      (node (ref "+3V3_OK") (pin "2") (pinfunction "+_2") (pintype "passive"))
      (node (ref "R99") (pin "1") (pinfunction "1_1") (pintype "passive"))
    )
    (net (code "78") (name "Net-(+5V_OK-+)") (class "Default")
      (node (ref "+5V_OK") (pin "2") (pinfunction "+_2") (pintype "passive"))
      (node (ref "R100") (pin "1") (pinfunction "1_1") (pintype "passive"))
    )
    (net (code "79") (name "Net-(+12V_OK-+)") (class "Default")
      (node (ref "+12V_OK") (pin "2") (pinfunction "+_2") (pintype "passive"))
      (node (ref "R101") (pin "1") (pinfunction "1_1") (pintype "passive"))
    )
    (net (code "80") (name "Net-(+15V_OK-+)") (class "Default")
      (node (ref "+15V_OK") (pin "2") (pinfunction "+_2") (pintype "passive"))
      (node (ref "R98") (pin "1") (pinfunction "1_1") (pintype "passive"))
    )
    (net (code "81") (name "Net-(-15V_OK-+)") (class "Default")
      (node (ref "-15V_OK") (pin "2") (pinfunction "+_2") (pintype "passive"))
      (node (ref "R97") (pin "2") (pinfunction "2_2") (pintype "passive"))
    )
    (net (code "82") (name "Net-(C10-Pad1)") (class "Default")
      (node (ref "C10") (pin "1") (pinfunction "1_1") (pintype "passive"))
      (node (ref "C15") (pin "2") (pinfunction "2_2") (pintype "passive"))
      (node (ref "C9") (pin "2") (pinfunction "2_2") (pintype "passive"))
    )
    (net (code "83") (name "Net-(C16-Pad2)") (class "Default")
      (node (ref "C16") (pin "2") (pinfunction "2_2") (pintype "passive"))
      (node (ref "C17") (pin "1") (pinfunction "1_1") (pintype "passive"))
      (node (ref "C18") (pin "2") (pinfunction "2_2") (pintype "passive"))
    )
    (net (code "84") (name "Net-(C67-Pad2)") (class "Default")
      (node (ref "C67") (pin "2") (pinfunction "2_2") (pintype "passive"))
      (node (ref "R53") (pin "1") (pinfunction "1_1") (pintype "passive"))
    )
    (net (code "85") (name "Net-(C101-Pad1)") (class "Default")
      (node (ref "C101") (pin "1") (pinfunction "1_1") (pintype "passive"))
      (node (ref "R29") (pin "1") (pinfunction "1_1") (pintype "passive"))
      (node (ref "R88") (pin "1") (pinfunction "1_1") (pintype "passive"))
      (node (ref "R89") (pin "1") (pinfunction "1_1") (pintype "passive"))
      (node (ref "R90") (pin "1") (pinfunction "1_1") (pintype "passive"))
    )
    (net (code "86") (name "Net-(C102-Pad2)") (class "Default")
      (node (ref "C102") (pin "2") (pinfunction "2_2") (pintype "passive"))
      (node (ref "R52") (pin "1") (pinfunction "1_1") (pintype "passive"))
    )
    (net (code "87") (name "Net-(IC1A--IN)") (class "Default")
      (node (ref "IC1") (pin "1") (pinfunction "OUT_1") (pintype "output"))
      (node (ref "IC1") (pin "2") (pinfunction "-IN_2") (pintype "input"))
      (node (ref "U7") (pin "3") (pinfunction "IN+_3") (pintype "input"))
      (node (ref "U8") (pin "3") (pinfunction "IN+_3") (pintype "input"))
    )
    (net (code "88") (name "Net-(IC1B--IN)") (class "Default")
      (node (ref "IC1") (pin "6") (pinfunction "-IN_6") (pintype "input"))
      (node (ref "IC1") (pin "7") (pinfunction "OUT_7") (pintype "output"))
      (node (ref "U7") (pin "1") (pinfunction "REF_1") (pintype "passive"))
      (node (ref "U8") (pin "2") (pinfunction "IN-_2") (pintype "input"))
    )
    (net (code "89") (name "Net-(IC2-DIN)") (class "Default")
      (node (ref "IC2") (pin "8") (pinfunction "DIN_8") (pintype "bidirectional"))
      (node (ref "IC3") (pin "8") (pinfunction "DIN_8") (pintype "bidirectional"))
      (node (ref "R93") (pin "1") (pinfunction "1_1") (pintype "passive"))
    )
    (net (code "90") (name "Net-(IC2-SCLK)") (class "Default")
      (node (ref "IC2") (pin "10") (pinfunction "SCLK_10") (pintype "bidirectional"))
      (node (ref "IC3") (pin "10") (pinfunction "SCLK_10") (pintype "bidirectional"))
      (node (ref "R92") (pin "1") (pinfunction "1_1") (pintype "passive"))
    )
    (net (code "91") (name "Net-(IC2-VOUTA)") (class "Default")
      (node (ref "IC2") (pin "2") (pinfunction "VOUTA_2") (pintype "bidirectional"))
      (node (ref "R38") (pin "2") (pinfunction "2_2") (pintype "passive"))
    )
    (net (code "92") (name "Net-(IC2-VOUTB)") (class "Default")
      (node (ref "IC2") (pin "3") (pinfunction "VOUTB_3") (pintype "bidirectional"))
      (node (ref "R41") (pin "2") (pinfunction "2_2") (pintype "passive"))
    )
    (net (code "93") (name "Net-(IC2-VOUTC)") (class "Default")
      (node (ref "IC2") (pin "4") (pinfunction "VOUTC_4") (pintype "bidirectional"))
      (node (ref "R44") (pin "2") (pinfunction "2_2") (pintype "passive"))
    )
    (net (code "94") (name "Net-(IC2-VOUTD)") (class "Default")
      (node (ref "IC2") (pin "5") (pinfunction "VOUTD_5") (pintype "bidirectional"))
      (node (ref "R64") (pin "2") (pinfunction "2_2") (pintype "passive"))
    )
    (net (code "95") (name "Net-(IC2-~{SYNC})") (class "Default")
      (node (ref "IC2") (pin "9") (pinfunction "~{SYNC}_9") (pintype "bidirectional"))
      (node (ref "R94") (pin "1") (pinfunction "1_1") (pintype "passive"))
    )
    (net (code "96") (name "Net-(IC3-VOUTA)") (class "Default")
      (node (ref "IC3") (pin "2") (pinfunction "VOUTA_2") (pintype "bidirectional"))
      (node (ref "R74") (pin "1") (pinfunction "1_1") (pintype "passive"))
    )
    (net (code "97") (name "Net-(IC3-VOUTB)") (class "Default")
      (node (ref "IC3") (pin "3") (pinfunction "VOUTB_3") (pintype "bidirectional"))
      (node (ref "R75") (pin "1") (pinfunction "1_1") (pintype "passive"))
    )
    (net (code "98") (name "Net-(IC3-~{SYNC})") (class "Default")
      (node (ref "IC3") (pin "9") (pinfunction "~{SYNC}_9") (pintype "bidirectional"))
      (node (ref "R95") (pin "1") (pinfunction "1_1") (pintype "passive"))
    )
    (net (code "99") (name "Net-(IC4A--IN)") (class "Default")
      (node (ref "IC4") (pin "1") (pinfunction "OUT_1") (pintype "output"))
      (node (ref "IC4") (pin "2") (pinfunction "-IN_2") (pintype "input"))
      (node (ref "U4") (pin "3") (pinfunction "IN+_3") (pintype "input"))
      (node (ref "U6") (pin "3") (pinfunction "IN+_3") (pintype "input"))
    )
    (net (code "100") (name "Net-(IC5A--IN)") (class "Default")
      (node (ref "C38") (pin "1") (pinfunction "1_1") (pintype "passive"))
      (node (ref "IC5") (pin "2") (pinfunction "-IN_2") (pintype "input"))
      (node (ref "R28") (pin "1") (pinfunction "1_1") (pintype "passive"))
      (node (ref "STAGE(LEFT)") (pin "8") (pinfunction "OUT_8") (pintype "output"))
    )
    (net (code "101") (name "Net-(IC5B--IN)") (class "Default")
      (node (ref "C37") (pin "1") (pinfunction "1_1") (pintype "passive"))
      (node (ref "IC5") (pin "6") (pinfunction "-IN_6") (pintype "input"))
      (node (ref "R30") (pin "1") (pinfunction "1_1") (pintype "passive"))
      (node (ref "STAGE(RIGHT)") (pin "8") (pinfunction "OUT_8") (pintype "output"))
    )
    (net (code "102") (name "Net-(IC6-CRS_DV{slash}~{MODE2})") (class "Default")
      (node (ref "IC6") (pin "11") (pinfunction "CRS_DV/~{MODE2}_11") (pintype "bidirectional"))
      (node (ref "R21") (pin "2") (pinfunction "2_2") (pintype "passive"))
      (node (ref "R26") (pin "2") (pinfunction "2_2") (pintype "passive"))
    )
    (net (code "103") (name "Net-(IC6-RBIAS)") (class "Default")
      (node (ref "IC6") (pin "24") (pinfunction "RBIAS_24") (pintype "bidirectional"))
      (node (ref "R77") (pin "1") (pinfunction "1_1") (pintype "passive"))
    )
    (net (code "104") (name "Net-(IC6-RXD0{slash}~{MODE0})") (class "Default")
      (node (ref "IC6") (pin "8") (pinfunction "RXD0/~{MODE0}_8") (pintype "bidirectional"))
      (node (ref "R20") (pin "2") (pinfunction "2_2") (pintype "passive"))
      (node (ref "R25") (pin "2") (pinfunction "2_2") (pintype "passive"))
    )
    (net (code "105") (name "Net-(IC6-RXD1{slash}~{MODE1})") (class "Default")
      (node (ref "IC6") (pin "7") (pinfunction "RXD1/~{MODE1}_7") (pintype "bidirectional"))
      (node (ref "R18") (pin "2") (pinfunction "2_2") (pintype "passive"))
      (node (ref "R24") (pin "2") (pinfunction "2_2") (pintype "passive"))
    )
    (net (code "106") (name "Net-(IC6-RXER{slash}~{PHYAD0})") (class "Default")
      (node (ref "IC6") (pin "10") (pinfunction "RXER/~{PHYAD0}_10") (pintype "bidirectional"))
      (node (ref "R27") (pin "2") (pinfunction "2_2") (pintype "passive"))
    )
    (net (code "107") (name "Net-(IC6-VDDCR)") (class "Default")
      (node (ref "C88") (pin "2") (pinfunction "2_2") (pintype "passive"))
      (node (ref "C89") (pin "2") (pinfunction "2_2") (pintype "passive"))
      (node (ref "IC6") (pin "6") (pinfunction "VDDCR_6") (pintype "power_in"))
    )
    (net (code "108") (name "Net-(IC6-XTAL1{slash}CLKIN)") (class "Default")
      (node (ref "C100") (pin "2") (pinfunction "2_2") (pintype "passive"))
      (node (ref "IC6") (pin "5") (pinfunction "XTAL1/CLKIN_5") (pintype "input"))
      (node (ref "Y3") (pin "2") (pinfunction "2_2") (pintype "bidirectional"))
    )
    (net (code "109") (name "Net-(IC6-XTAL2)") (class "Default")
      (node (ref "C40") (pin "2") (pinfunction "2_2") (pintype "passive"))
      (node (ref "IC6") (pin "4") (pinfunction "XTAL2_4") (pintype "bidirectional"))
      (node (ref "Y3") (pin "1") (pinfunction "1_1") (pintype "bidirectional"))
    )
    (net (code "110") (name "Net-(IC7A--IN)") (class "Default")
      (node (ref "IC7") (pin "2") (pinfunction "-IN_2") (pintype "input"))
      (node (ref "R62") (pin "2") (pinfunction "2_2") (pintype "passive"))
      (node (ref "R71") (pin "1") (pinfunction "1_1") (pintype "passive"))
    )
    (net (code "111") (name "Net-(IC7B-+IN)") (class "Default")
      (node (ref "IC7") (pin "5") (pinfunction "+IN_5") (pintype "input"))
      (node (ref "R46") (pin "2") (pinfunction "2_2") (pintype "passive"))
      (node (ref "R73") (pin "1") (pinfunction "1_1") (pintype "passive"))
    )
    (net (code "112") (name "Net-(IC8A--IN)") (class "Default")
      (node (ref "C55") (pin "1") (pinfunction "1_1") (pintype "passive"))
      (node (ref "IC8") (pin "2") (pinfunction "-IN_2") (pintype "input"))
      (node (ref "R48") (pin "1") (pinfunction "1_1") (pintype "passive"))
      (node (ref "VCA1(LEFT)") (pin "8") (pinfunction "OUT_8") (pintype "output"))
    )
    (net (code "113") (name "Net-(IC8B--IN)") (class "Default")
      (node (ref "C56") (pin "1") (pinfunction "1_1") (pintype "passive"))
      (node (ref "IC8") (pin "6") (pinfunction "-IN_6") (pintype "input"))
      (node (ref "R49") (pin "1") (pinfunction "1_1") (pintype "passive"))
      (node (ref "VCA2(RIGHT)") (pin "8") (pinfunction "OUT_8") (pintype "output"))
    )
    (net (code "114") (name "Net-(IC9A--IN)") (class "Default")
      (node (ref "IC9") (pin "2") (pinfunction "-IN_2") (pintype "input"))
      (node (ref "R56") (pin "1") (pinfunction "1_1") (pintype "passive"))
      (node (ref "R57") (pin "2") (pinfunction "2_2") (pintype "passive"))
    )
    (net (code "115") (name "Net-(IC9B--IN)") (class "Default")
      (node (ref "IC9") (pin "6") (pinfunction "-IN_6") (pintype "input"))
      (node (ref "R54") (pin "1") (pinfunction "1_1") (pintype "passive"))
      (node (ref "R55") (pin "2") (pinfunction "2_2") (pintype "passive"))
    )
    (net (code "116") (name "Net-(IC10-PA9)") (class "Default")
      (node (ref "IC10") (pin "101") (pinfunction "PA9_101") (pintype "bidirectional"))
      (node (ref "R19") (pin "1") (pinfunction "1_1") (pintype "passive"))
    )
    (net (code "117") (name "Net-(IC10-VCAP_1)") (class "Default")
      (node (ref "C71") (pin "1") (pinfunction "1_1") (pintype "passive"))
      (node (ref "IC10") (pin "71") (pinfunction "VCAP_1_71") (pintype "bidirectional"))
    )
    (net (code "118") (name "Net-(IC10-VCAP_2)") (class "Default")
      (node (ref "C72") (pin "1") (pinfunction "1_1") (pintype "passive"))
      (node (ref "IC10") (pin "106") (pinfunction "VCAP_2_106") (pintype "bidirectional"))
    )
    (net (code "119") (name "Net-(IC10-VDDA)") (class "Default")
      (node (ref "C80") (pin "2") (pinfunction "2_2") (pintype "passive"))
      (node (ref "IC10") (pin "32") (pinfunction "VREF+_32") (pintype "bidirectional"))
      (node (ref "IC10") (pin "33") (pinfunction "VDDA_33") (pintype "bidirectional"))
    )
    (net (code "120") (name "Net-(IC11-REFCAPA)") (class "Default")
      (node (ref "C42") (pin "1") (pinfunction "1_1") (pintype "passive"))
      (node (ref "IC11") (pin "44") (pinfunction "REFCAPA_44") (pintype "bidirectional"))
      (node (ref "IC11") (pin "45") (pinfunction "REFCAPB_45") (pintype "bidirectional"))
    )
    (net (code "121") (name "Net-(IC11-REFIN{slash}REFOUT)") (class "Default")
      (node (ref "C51") (pin "1") (pinfunction "1_1") (pintype "passive"))
      (node (ref "IC11") (pin "42") (pinfunction "REFIN/REFOUT_42") (pintype "bidirectional"))
    )
    (net (code "122") (name "Net-(IC11-REF_SELECT)") (class "Default")
      (node (ref "IC11") (pin "34") (pinfunction "REF_SELECT_34") (pintype "bidirectional"))
      (node (ref "R35") (pin "2") (pinfunction "2_2") (pintype "passive"))
    )
    (net (code "123") (name "Net-(IC11-REGCAP_1)") (class "Default")
      (node (ref "C52") (pin "1") (pinfunction "1_1") (pintype "passive"))
      (node (ref "IC11") (pin "36") (pinfunction "REGCAP_1_36") (pintype "bidirectional"))
    )
    (net (code "124") (name "Net-(IC11-REGCAP_2)") (class "Default")
      (node (ref "C59") (pin "1") (pinfunction "1_1") (pintype "passive"))
      (node (ref "IC11") (pin "39") (pinfunction "REGCAP_2_39") (pintype "bidirectional"))
    )
    (net (code "125") (name "Net-(IC11-~{PAR}{slash}SER_SEL)") (class "Default")
      (node (ref "IC11") (pin "6") (pinfunction "~{PAR}/SER_SEL_6") (pintype "bidirectional"))
      (node (ref "R14") (pin "1") (pinfunction "1_1") (pintype "passive"))
    )
    (net (code "126") (name "Net-(IC14A--IN)") (class "Default")
      (node (ref "IC14") (pin "2") (pinfunction "-IN_2") (pintype "input"))
      (node (ref "R70") (pin "2") (pinfunction "2_2") (pintype "passive"))
      (node (ref "R72") (pin "1") (pinfunction "1_1") (pintype "passive"))
    )
    (net (code "127") (name "Net-(IC14B-+IN)") (class "Default")
      (node (ref "IC14") (pin "5") (pinfunction "+IN_5") (pintype "input"))
      (node (ref "R58") (pin "2") (pinfunction "2_2") (pintype "passive"))
      (node (ref "R59") (pin "1") (pinfunction "1_1") (pintype "passive"))
    )
    (net (code "128") (name "Net-(IC15A-+IN)") (class "Default")
      (node (ref "IC15") (pin "3") (pinfunction "+IN_3") (pintype "input"))
      (node (ref "R60") (pin "2") (pinfunction "2_2") (pintype "passive"))
      (node (ref "R61") (pin "1") (pinfunction "1_1") (pintype "passive"))
    )
    (net (code "129") (name "Net-(IC16A--IN)") (class "Default")
      (node (ref "IC16") (pin "1") (pinfunction "OUT_1") (pintype "output"))
      (node (ref "IC16") (pin "2") (pinfunction "-IN_2") (pintype "input"))
      (node (ref "U4") (pin "1") (pinfunction "REF_1") (pintype "passive"))
      (node (ref "U6") (pin "2") (pinfunction "IN-_2") (pintype "input"))
    )
    (net (code "130") (name "Net-(IN_LEFT-IN+)") (class "Default")
      (node (ref "C17") (pin "2") (pinfunction "2_2") (pintype "passive"))
      (node (ref "IN_LEFT") (pin "3") (pinfunction "IN+_3") (pintype "input"))
      (node (ref "K4") (pin "S2") (pinfunction "S_S2") (pintype "passive"))
    )
    (net (code "131") (name "Net-(IN_LEFT-IN-)") (class "Default")
      (node (ref "C16") (pin "1") (pinfunction "1_1") (pintype "passive"))
      (node (ref "IN_LEFT") (pin "2") (pinfunction "IN-_2") (pintype "input"))
      (node (ref "K4") (pin "S1") (pinfunction "S_S1") (pintype "passive"))
    )
    (net (code "132") (name "Net-(IN_RIGHT-IN+)") (class "Default")
      (node (ref "C10") (pin "2") (pinfunction "2_2") (pintype "passive"))
      (node (ref "IN_RIGHT") (pin "3") (pinfunction "IN+_3") (pintype "input"))
      (node (ref "K1") (pin "S2") (pinfunction "S_S2") (pintype "passive"))
    )
    (net (code "133") (name "Net-(IN_RIGHT-IN-)") (class "Default")
      (node (ref "C9") (pin "1") (pinfunction "1_1") (pintype "passive"))
      (node (ref "IN_RIGHT") (pin "2") (pinfunction "IN-_2") (pintype "input"))
      (node (ref "K1") (pin "S1") (pinfunction "S_S1") (pintype "passive"))
    )
    (net (code "134") (name "Net-(J1-13)") (class "Default")
      (node (ref "C101") (pin "2") (pinfunction "2_2") (pintype "passive"))
      (node (ref "J1") (pin "MP1") (pinfunction "13_MP1") (pintype "bidirectional"))
      (node (ref "J1") (pin "MP2") (pinfunction "14_MP2") (pintype "bidirectional"))
      (node (ref "R91") (pin "2") (pinfunction "2_2") (pintype "passive"))
    )
    (net (code "135") (name "Net-(J1-GREEN_K)") (class "Default")
      (node (ref "J1") (pin "11") (pinfunction "GREEN_K_11") (pintype "bidirectional"))
      (node (ref "R84") (pin "2") (pinfunction "2_2") (pintype "passive"))
    )
    (net (code "136") (name "Net-(J1-Pad7)") (class "Default")
      (node (ref "J1") (pin "7") (pinfunction "7_7") (pintype "bidirectional"))
      (node (ref "R29") (pin "2") (pinfunction "2_2") (pintype "passive"))
    )
    (net (code "137") (name "Net-(J1-Pad8)") (class "Default")
      (node (ref "J1") (pin "8") (pinfunction "8_8") (pintype "bidirectional"))
      (node (ref "R88") (pin "2") (pinfunction "2_2") (pintype "passive"))
    )
    (net (code "138") (name "Net-(J1-YELLOW_K)") (class "Default")
      (node (ref "J1") (pin "9") (pinfunction "YELLOW_K_9") (pintype "bidirectional"))
      (node (ref "R83") (pin "2") (pinfunction "2_2") (pintype "passive"))
    )
    (net (code "139") (name "Net-(K1B-O)") (class "Default")
      (node (ref "K1") (pin "Q1") (pinfunction "O_Q1") (pintype "passive"))
      (node (ref "K2") (pin "Q1") (pinfunction "O_Q1") (pintype "passive"))
    )
    (net (code "140") (name "Net-(K1C-O)") (class "Default")
      (node (ref "K1") (pin "Q2") (pinfunction "O_Q2") (pintype "passive"))
      (node (ref "K2") (pin "Q2") (pinfunction "O_Q2") (pintype "passive"))
    )
    (net (code "141") (name "Net-(K2B-S)") (class "Default")
      (node (ref "K2") (pin "S1") (pinfunction "S_S1") (pintype "passive"))
      (node (ref "OUT_RIGHT") (pin "1") (pinfunction "OUT-_1") (pintype "output"))
      (node (ref "OUT_RIGHT") (pin "2") (pinfunction "SEN-_2") (pintype "passive"))
    )
    (net (code "142") (name "Net-(K2C-S)") (class "Default")
      (node (ref "K2") (pin "S2") (pinfunction "S_S2") (pintype "passive"))
      (node (ref "OUT_RIGHT") (pin "7") (pinfunction "SEN+_7") (pintype "output"))
      (node (ref "OUT_RIGHT") (pin "8") (pinfunction "OUT+_8") (pintype "output"))
    )
    (net (code "143") (name "Net-(K3B-O)") (class "Default")
      (node (ref "K3") (pin "Q1") (pinfunction "O_Q1") (pintype "passive"))
      (node (ref "K4") (pin "Q1") (pinfunction "O_Q1") (pintype "passive"))
    )
    (net (code "144") (name "Net-(K3B-S)") (class "Default")
      (node (ref "K3") (pin "S1") (pinfunction "S_S1") (pintype "passive"))
      (node (ref "OUT_LEFT") (pin "1") (pinfunction "OUT-_1") (pintype "output"))
      (node (ref "OUT_LEFT") (pin "2") (pinfunction "SEN-_2") (pintype "passive"))
    )
    (net (code "145") (name "Net-(K3C-O)") (class "Default")
      (node (ref "K3") (pin "Q2") (pinfunction "O_Q2") (pintype "passive"))
      (node (ref "K4") (pin "Q2") (pinfunction "O_Q2") (pintype "passive"))
    )
    (net (code "146") (name "Net-(K3C-S)") (class "Default")
      (node (ref "K3") (pin "S2") (pinfunction "S_S2") (pintype "passive"))
      (node (ref "OUT_LEFT") (pin "7") (pinfunction "SEN+_7") (pintype "output"))
      (node (ref "OUT_LEFT") (pin "8") (pinfunction "OUT+_8") (pintype "output"))
    )
    (net (code "147") (name "Net-(K6B-P)") (class "Default")
      (node (ref "K6") (pin "P1") (pinfunction "P_P1") (pintype "passive"))
      (node (ref "K7") (pin "S1") (pinfunction "S_S1") (pintype "passive"))
      (node (ref "K8") (pin "Q1") (pinfunction "O_Q1") (pintype "passive"))
    )
    (net (code "148") (name "Net-(K6B-S)") (class "Default")
      (node (ref "K6") (pin "S1") (pinfunction "S_S1") (pintype "passive"))
      (node (ref "U7") (pin "5") (pinfunction "SEN_5") (pintype "output"))
      (node (ref "U7") (pin "6") (pinfunction "OUT_6") (pintype "output"))
    )
    (net (code "149") (name "Net-(K6C-P)") (class "Default")
      (node (ref "K6") (pin "P2") (pinfunction "P_P2") (pintype "passive"))
      (node (ref "K7") (pin "Q1") (pinfunction "O_Q1") (pintype "passive"))
      (node (ref "K8") (pin "S1") (pinfunction "S_S1") (pintype "passive"))
    )
    (net (code "150") (name "Net-(K6C-S)") (class "Default")
      (node (ref "K6") (pin "S2") (pinfunction "S_S2") (pintype "passive"))
      (node (ref "U8") (pin "5") (pinfunction "SEN_5") (pintype "output"))
      (node (ref "U8") (pin "6") (pinfunction "OUT_6") (pintype "output"))
    )
    (net (code "151") (name "Net-(LD1--)") (class "Default")
      (node (ref "LD1") (pin "1") (pinfunction "-_1") (pintype "passive"))
      (node (ref "R5") (pin "2") (pinfunction "2_2") (pintype "passive"))
    )
    (net (code "152") (name "Net-(LD2--)") (class "Default")
      (node (ref "LD2") (pin "1") (pinfunction "-_1") (pintype "passive"))
      (node (ref "R6") (pin "2") (pinfunction "2_2") (pintype "passive"))
    )
    (net (code "153") (name "Net-(LD3--)") (class "Default")
      (node (ref "LD3") (pin "1") (pinfunction "-_1") (pintype "passive"))
      (node (ref "R13") (pin "2") (pinfunction "2_2") (pintype "passive"))
    )
    (net (code "154") (name "Net-(LED1--)") (class "Default")
      (node (ref "LED1") (pin "1") (pinfunction "-_1") (pintype "passive"))
      (node (ref "R7") (pin "2") (pinfunction "2_2") (pintype "passive"))
    )
    (net (code "155") (name "Net-(LED2--)") (class "Default")
      (node (ref "LED2") (pin "1") (pinfunction "-_1") (pintype "passive"))
      (node (ref "R33") (pin "2") (pinfunction "2_2") (pintype "passive"))
    )
    (net (code "156") (name "Net-(LED3--)") (class "Default")
      (node (ref "LED3") (pin "1") (pinfunction "-_1") (pintype "passive"))
      (node (ref "R8") (pin "2") (pinfunction "2_2") (pintype "passive"))
    )
    (net (code "157") (name "Net-(LED4--)") (class "Default")
      (node (ref "LED4") (pin "1") (pinfunction "-_1") (pintype "passive"))
      (node (ref "R34") (pin "2") (pinfunction "2_2") (pintype "passive"))
    )
    (net (code "158") (name "Net-(LED5--)") (class "Default")
      (node (ref "LED5") (pin "1") (pinfunction "-_1") (pintype "passive"))
      (node (ref "R9") (pin "2") (pinfunction "2_2") (pintype "passive"))
    )
    (net (code "159") (name "Net-(LED6--)") (class "Default")
      (node (ref "LED6") (pin "1") (pinfunction "-_1") (pintype "passive"))
      (node (ref "R10") (pin "2") (pinfunction "2_2") (pintype "passive"))
    )
    (net (code "160") (name "Net-(LED7--)") (class "Default")
      (node (ref "LED7") (pin "1") (pinfunction "-_1") (pintype "passive"))
      (node (ref "R11") (pin "2") (pinfunction "2_2") (pintype "passive"))
    )
    (net (code "161") (name "Net-(LED8--)") (class "Default")
      (node (ref "LED8") (pin "1") (pinfunction "-_1") (pintype "passive"))
      (node (ref "R12") (pin "2") (pinfunction "2_2") (pintype "passive"))
    )
    (net (code "162") (name "Net-(STAGE(LEFT)-IN)") (class "Default")
      (node (ref "R36") (pin "2") (pinfunction "2_2") (pintype "passive"))
      (node (ref "STAGE(LEFT)") (pin "1") (pinfunction "IN_1") (pintype "input"))
    )
    (net (code "163") (name "Net-(STAGE(LEFT)-V-)") (class "Default")
      (node (ref "C47") (pin "1") (pinfunction "1_1") (pintype "passive"))
      (node (ref "R31") (pin "2") (pinfunction "2_2") (pintype "passive"))
      (node (ref "STAGE(LEFT)") (pin "5") (pinfunction "V-_5") (pintype "power_in"))
    )
    (net (code "164") (name "Net-(STAGE(RIGHT)-IN)") (class "Default")
      (node (ref "R37") (pin "2") (pinfunction "2_2") (pintype "passive"))
      (node (ref "STAGE(RIGHT)") (pin "1") (pinfunction "IN_1") (pintype "input"))
    )
    (net (code "165") (name "Net-(STAGE(RIGHT)-V-)") (class "Default")
      (node (ref "C43") (pin "1") (pinfunction "1_1") (pintype "passive"))
      (node (ref "R32") (pin "2") (pinfunction "2_2") (pintype "passive"))
      (node (ref "STAGE(RIGHT)") (pin "5") (pinfunction "V-_5") (pintype "power_in"))
    )
    (net (code "166") (name "Net-(T1-NC_4)") (class "Default")
      (node (ref "R89") (pin "2") (pinfunction "2_2") (pintype "passive"))
      (node (ref "T1") (pin "12") (pinfunction "NC_4_12") (pintype "bidirectional"))
    )
    (net (code "167") (name "Net-(T1-NC_6)") (class "Default")
      (node (ref "R90") (pin "2") (pinfunction "2_2") (pintype "passive"))
      (node (ref "T1") (pin "15") (pinfunction "NC_6_15") (pintype "bidirectional"))
    )
    (net (code "168") (name "Net-(T1-RX+)") (class "Default")
      (node (ref "J1") (pin "3") (pinfunction "3_3") (pintype "bidirectional"))
      (node (ref "T1") (pin "11") (pinfunction "RX+_11") (pintype "bidirectional"))
    )
    (net (code "169") (name "Net-(T1-RX-)") (class "Default")
      (node (ref "J1") (pin "6") (pinfunction "6_6") (pintype "bidirectional"))
      (node (ref "T1") (pin "9") (pinfunction "RX-_9") (pintype "bidirectional"))
    )
    (net (code "170") (name "Net-(T1-TX+)") (class "Default")
      (node (ref "J1") (pin "1") (pinfunction "1_1") (pintype "bidirectional"))
      (node (ref "T1") (pin "16") (pinfunction "TX+_16") (pintype "bidirectional"))
    )
    (net (code "171") (name "Net-(T1-TX-)") (class "Default")
      (node (ref "J1") (pin "2") (pinfunction "2_2") (pintype "bidirectional"))
      (node (ref "T1") (pin "14") (pinfunction "TX-_14") (pintype "bidirectional"))
    )
    (net (code "172") (name "Net-(VCA1(LEFT)-IN)") (class "Default")
      (node (ref "R52") (pin "2") (pinfunction "2_2") (pintype "passive"))
      (node (ref "VCA1(LEFT)") (pin "1") (pinfunction "IN_1") (pintype "input"))
    )
    (net (code "173") (name "Net-(VCA1(LEFT)-V-)") (class "Default")
      (node (ref "C61") (pin "1") (pinfunction "1_1") (pintype "passive"))
      (node (ref "R50") (pin "2") (pinfunction "2_2") (pintype "passive"))
      (node (ref "VCA1(LEFT)") (pin "5") (pinfunction "V-_5") (pintype "power_in"))
    )
    (net (code "174") (name "Net-(VCA2(RIGHT)-IN)") (class "Default")
      (node (ref "R53") (pin "2") (pinfunction "2_2") (pintype "passive"))
      (node (ref "VCA2(RIGHT)") (pin "1") (pinfunction "IN_1") (pintype "input"))
    )
    (net (code "175") (name "Net-(VCA2(RIGHT)-V-)") (class "Default")
      (node (ref "C58") (pin "1") (pinfunction "1_1") (pintype "passive"))
      (node (ref "R51") (pin "2") (pinfunction "2_2") (pintype "passive"))
      (node (ref "VCA2(RIGHT)") (pin "5") (pinfunction "V-_5") (pintype "power_in"))
    )
    (net (code "176") (name "OS0") (class "Default")
      (node (ref "IC10") (pin "98") (pinfunction "PC8_98") (pintype "bidirectional"))
      (node (ref "IC11") (pin "3") (pinfunction "OS0_3") (pintype "bidirectional"))
    )
    (net (code "177") (name "OS1") (class "Default")
      (node (ref "IC10") (pin "99") (pinfunction "PC9_99") (pintype "bidirectional"))
      (node (ref "IC11") (pin "4") (pinfunction "OS1_4") (pintype "bidirectional"))
    )
    (net (code "178") (name "OS2") (class "Default")
      (node (ref "IC10") (pin "111") (pinfunction "PC10_111") (pintype "bidirectional"))
      (node (ref "IC11") (pin "5") (pinfunction "OS2_5") (pintype "bidirectional"))
    )
    (net (code "179") (name "OUT1_DRIVER") (class "Default")
      (node (ref "K1") (pin "2") (pinfunction "2_2") (pintype "passive"))
      (node (ref "K2") (pin "2") (pinfunction "2_2") (pintype "passive"))
      (node (ref "R33") (pin "1") (pinfunction "1_1") (pintype "passive"))
      (node (ref "R7") (pin "1") (pinfunction "1_1") (pintype "passive"))
      (node (ref "U12") (pin "16") (pinfunction "OUT1_16") (pintype "bidirectional"))
    )
    (net (code "180") (name "OUT2_DRIVER") (class "Default")
      (node (ref "K3") (pin "2") (pinfunction "2_2") (pintype "passive"))
      (node (ref "K4") (pin "2") (pinfunction "2_2") (pintype "passive"))
      (node (ref "R34") (pin "1") (pinfunction "1_1") (pintype "passive"))
      (node (ref "R8") (pin "1") (pinfunction "1_1") (pintype "passive"))
      (node (ref "U12") (pin "15") (pinfunction "OUT2_15") (pintype "bidirectional"))
    )
    (net (code "181") (name "OUT3_DRIVER") (class "Default")
      (node (ref "K5") (pin "2") (pinfunction "2_2") (pintype "passive"))
      (node (ref "R9") (pin "1") (pinfunction "1_1") (pintype "passive"))
      (node (ref "U12") (pin "14") (pinfunction "OUT3_14") (pintype "bidirectional"))
    )
    (net (code "182") (name "OUT4_DRIVER") (class "Default")
      (node (ref "K6") (pin "2") (pinfunction "2_2") (pintype "passive"))
      (node (ref "R10") (pin "1") (pinfunction "1_1") (pintype "passive"))
      (node (ref "U12") (pin "13") (pinfunction "OUT4_13") (pintype "bidirectional"))
    )
    (net (code "183") (name "OUT5_DRIVER") (class "Default")
      (node (ref "K7") (pin "2") (pinfunction "2_2") (pintype "passive"))
      (node (ref "R11") (pin "1") (pinfunction "1_1") (pintype "passive"))
      (node (ref "U12") (pin "12") (pinfunction "OUT5_12") (pintype "bidirectional"))
    )
    (net (code "184") (name "OUT6_DRIVER") (class "Default")
      (node (ref "K8") (pin "2") (pinfunction "2_2") (pintype "passive"))
      (node (ref "R12") (pin "1") (pinfunction "1_1") (pintype "passive"))
      (node (ref "U12") (pin "11") (pinfunction "OUT6_11") (pintype "bidirectional"))
    )
    (net (code "185") (name "OUT_L{slash}M") (class "Default")
      (node (ref "K8") (pin "P1") (pinfunction "P_P1") (pintype "passive"))
      (node (ref "OUT_LEFT") (pin "4") (pinfunction "IN_4") (pintype "input"))
    )
    (net (code "186") (name "OUT_R{slash}S") (class "Default")
      (node (ref "K7") (pin "P1") (pinfunction "P_P1") (pintype "passive"))
      (node (ref "OUT_RIGHT") (pin "4") (pinfunction "IN_4") (pintype "input"))
    )
    (net (code "187") (name "POSITIVE_IN(L{slash}M)") (class "Default")
      (node (ref "IN2(L/M)") (pin "2") (pinfunction "2_2") (pintype "bidirectional"))
      (node (ref "K4") (pin "P2") (pinfunction "P_P2") (pintype "passive"))
    )
    (net (code "188") (name "POSITIVE_IN(R{slash}S)") (class "Default")
      (node (ref "IN1(R/S)") (pin "2") (pinfunction "2_2") (pintype "bidirectional"))
      (node (ref "K1") (pin "P2") (pinfunction "P_P2") (pintype "passive"))
    )
    (net (code "189") (name "POSITIVE_OUT(L{slash}M)") (class "Default")
      (node (ref "K3") (pin "P2") (pinfunction "P_P2") (pintype "passive"))
      (node (ref "OUT2(L/M)") (pin "2") (pinfunction "2_2") (pintype "bidirectional"))
    )
    (net (code "190") (name "POSITIVE_OUT(R{slash}S)") (class "Default")
      (node (ref "K2") (pin "P2") (pinfunction "P_P2") (pintype "passive"))
      (node (ref "OUT1(R/S)") (pin "2") (pinfunction "2_2") (pintype "bidirectional"))
    )
    (net (code "191") (name "R") (class "Default")
      (node (ref "IC16") (pin "3") (pinfunction "+IN_3") (pintype "input"))
      (node (ref "IN_RIGHT") (pin "5") (pinfunction "SEN_5") (pintype "output"))
      (node (ref "IN_RIGHT") (pin "6") (pinfunction "OUT_6") (pintype "output"))
      (node (ref "K5") (pin "Q2") (pinfunction "O_Q2") (pintype "passive"))
    )
    (net (code "192") (name "RANGE") (class "Default")
      (node (ref "IC10") (pin "112") (pinfunction "PC11_112") (pintype "bidirectional"))
      (node (ref "IC11") (pin "8") (pinfunction "RANGE_8") (pintype "bidirectional"))
    )
    (net (code "193") (name "RD") (class "Default")
      (node (ref "IC10") (pin "116") (pinfunction "PD2_116") (pintype "bidirectional"))
      (node (ref "IC11") (pin "12") (pinfunction "~{RD}/SCLK_12") (pintype "bidirectional"))
    )
    (net (code "194") (name "RD_N") (class "Default")
      (node (ref "IC13") (pin "6") (pinfunction "I/O4_6") (pintype "bidirectional"))
      (node (ref "IC6") (pin "22") (pinfunction "RXN_22") (pintype "bidirectional"))
      (node (ref "R82") (pin "1") (pinfunction "1_1") (pintype "passive"))
      (node (ref "T1") (pin "8") (pinfunction "RD-_8") (pintype "bidirectional"))
    )
    (net (code "195") (name "RD_P") (class "Default")
      (node (ref "IC13") (pin "1") (pinfunction "I/O1_1") (pintype "bidirectional"))
      (node (ref "IC6") (pin "23") (pinfunction "RXP_23") (pintype "bidirectional"))
      (node (ref "R81") (pin "1") (pinfunction "1_1") (pintype "passive"))
      (node (ref "T1") (pin "6") (pinfunction "RD+_6") (pintype "bidirectional"))
    )
    (net (code "196") (name "RELAIS1") (class "Default")
      (node (ref "IC10") (pin "57") (pinfunction "PG1_57") (pintype "bidirectional"))
      (node (ref "U12") (pin "1") (pinfunction "IN1_1") (pintype "bidirectional"))
    )
    (net (code "197") (name "RELAIS2") (class "Default")
      (node (ref "IC10") (pin "56") (pinfunction "PG0_56") (pintype "bidirectional"))
      (node (ref "U12") (pin "2") (pinfunction "IN2_2") (pintype "bidirectional"))
    )
    (net (code "198") (name "RELAIS3") (class "Default")
      (node (ref "IC10") (pin "132") (pinfunction "PG15_132") (pintype "bidirectional"))
      (node (ref "U12") (pin "3") (pinfunction "IN3_3") (pintype "bidirectional"))
    )
    (net (code "199") (name "RELAIS4") (class "Default")
      (node (ref "IC10") (pin "125") (pinfunction "PG10_125") (pintype "bidirectional"))
      (node (ref "U12") (pin "4") (pinfunction "IN4_4") (pintype "bidirectional"))
    )
    (net (code "200") (name "RELAIS5") (class "Default")
      (node (ref "IC10") (pin "127") (pinfunction "PG12_127") (pintype "bidirectional"))
      (node (ref "U12") (pin "5") (pinfunction "IN5_5") (pintype "bidirectional"))
    )
    (net (code "201") (name "RELAIS6") (class "Default")
      (node (ref "IC10") (pin "124") (pinfunction "PG9_124") (pintype "bidirectional"))
      (node (ref "U12") (pin "6") (pinfunction "IN6_6") (pintype "bidirectional"))
    )
    (net (code "202") (name "RESET") (class "Default")
      (node (ref "IC10") (pin "87") (pinfunction "PG2_87") (pintype "bidirectional"))
      (node (ref "IC11") (pin "11") (pinfunction "RESET_11") (pintype "bidirectional"))
    )
    (net (code "203") (name "RMII_CRS_DV") (class "Default")
      (node (ref "IC10") (pin "43") (pinfunction "PA7_43") (pintype "bidirectional"))
      (node (ref "R26") (pin "1") (pinfunction "1_1") (pintype "passive"))
    )
    (net (code "204") (name "RMII_MDC") (class "Default")
      (node (ref "IC10") (pin "27") (pinfunction "PC1_27") (pintype "bidirectional"))
      (node (ref "IC6") (pin "13") (pinfunction "MDC_13") (pintype "bidirectional"))
    )
    (net (code "205") (name "RMII_MDIO") (class "Default")
      (node (ref "IC10") (pin "36") (pinfunction "PA2_36") (pintype "bidirectional"))
      (node (ref "IC6") (pin "12") (pinfunction "MDIO_12") (pintype "bidirectional"))
      (node (ref "R22") (pin "2") (pinfunction "2_2") (pintype "passive"))
    )
    (net (code "206") (name "RMII_REF_CLK") (class "Default")
      (node (ref "IC10") (pin "35") (pinfunction "PA1_35") (pintype "bidirectional"))
      (node (ref "IC6") (pin "14") (pinfunction "NINT/REFCLKO_14") (pintype "output"))
      (node (ref "R23") (pin "1") (pinfunction "1_1") (pintype "passive"))
    )
    (net (code "207") (name "RMII_RXD0") (class "Default")
      (node (ref "IC10") (pin "44") (pinfunction "PC4_44") (pintype "bidirectional"))
      (node (ref "R25") (pin "1") (pinfunction "1_1") (pintype "passive"))
    )
    (net (code "208") (name "RMII_RXD1") (class "Default")
      (node (ref "IC10") (pin "45") (pinfunction "PC5_45") (pintype "bidirectional"))
      (node (ref "R24") (pin "1") (pinfunction "1_1") (pintype "passive"))
    )
    (net (code "209") (name "RMII_TXD0") (class "Default")
      (node (ref "IC10") (pin "128") (pinfunction "PG13_128") (pintype "bidirectional"))
      (node (ref "IC6") (pin "17") (pinfunction "TXD0_17") (pintype "bidirectional"))
    )
    (net (code "210") (name "RMII_TXD1") (class "Default")
      (node (ref "IC10") (pin "74") (pinfunction "PB13_74") (pintype "bidirectional"))
      (node (ref "IC6") (pin "18") (pinfunction "TXD1_18") (pintype "bidirectional"))
    )
    (net (code "211") (name "RMII_TX_EN") (class "Default")
      (node (ref "IC10") (pin "126") (pinfunction "PG11_126") (pintype "bidirectional"))
      (node (ref "IC6") (pin "16") (pinfunction "TXEN_16") (pintype "bidirectional"))
    )
    (net (code "212") (name "R{slash}S_IN(VCA2_IN)") (class "Default")
      (node (ref "C67") (pin "1") (pinfunction "1_1") (pintype "passive"))
      (node (ref "IC11") (pin "51") (pinfunction "V2_51") (pintype "bidirectional"))
      (node (ref "K5") (pin "P2") (pinfunction "P_P2") (pintype "passive"))
    )
    (net (code "213") (name "R{slash}S_OUT(OUT_STAGE_RIGHT)") (class "Default")
      (node (ref "C37") (pin "2") (pinfunction "2_2") (pintype "passive"))
      (node (ref "IC1") (pin "5") (pinfunction "+IN_5") (pintype "input"))
      (node (ref "IC11") (pin "59") (pinfunction "V6_59") (pintype "bidirectional"))
      (node (ref "IC5") (pin "7") (pinfunction "OUT_7") (pintype "output"))
      (node (ref "K6") (pin "Q2") (pinfunction "O_Q2") (pintype "passive"))
      (node (ref "R30") (pin "2") (pinfunction "2_2") (pintype "passive"))
    )
    (net (code "214") (name "R{slash}S_OUT(VCA2_OUT)") (class "Default")
      (node (ref "C56") (pin "2") (pinfunction "2_2") (pintype "passive"))
      (node (ref "IC11") (pin "55") (pinfunction "V4_55") (pintype "bidirectional"))
      (node (ref "IC8") (pin "7") (pinfunction "OUT_7") (pintype "output"))
      (node (ref "R37") (pin "1") (pinfunction "1_1") (pintype "passive"))
      (node (ref "R49") (pin "2") (pinfunction "2_2") (pintype "passive"))
    )
    (net (code "215") (name "S") (class "Default")
      (node (ref "K5") (pin "S2") (pinfunction "S_S2") (pintype "passive"))
      (node (ref "U6") (pin "5") (pinfunction "SEN_5") (pintype "output"))
      (node (ref "U6") (pin "6") (pinfunction "OUT_6") (pintype "output"))
    )
    (net (code "216") (name "SCLK_DAC") (class "Default")
      (node (ref "IC10") (pin "69") (pinfunction "PB10_69") (pintype "bidirectional"))
      (node (ref "R92") (pin "2") (pinfunction "2_2") (pintype "passive"))
    )
    (net (code "217") (name "SWCLK") (class "Default")
      (node (ref "IC10") (pin "109") (pinfunction "PA14_109") (pintype "bidirectional"))
      (node (ref "PROG.") (pin "1") (pinfunction "1_1") (pintype "bidirectional"))
    )
    (net (code "218") (name "SWDIO") (class "Default")
      (node (ref "IC10") (pin "105") (pinfunction "PA13_105") (pintype "bidirectional"))
      (node (ref "PROG.") (pin "3") (pinfunction "3_3") (pintype "bidirectional"))
    )
    (net (code "219") (name "SYM1") (class "Default")
      (node (ref "R38") (pin "1") (pinfunction "1_1") (pintype "passive"))
      (node (ref "R40") (pin "2") (pinfunction "2_2") (pintype "passive"))
      (node (ref "VCA1(LEFT)") (pin "4") (pinfunction "SYM_4") (pintype "passive"))
    )
    (net (code "220") (name "SYM2") (class "Default")
      (node (ref "R41") (pin "1") (pinfunction "1_1") (pintype "passive"))
      (node (ref "R43") (pin "2") (pinfunction "2_2") (pintype "passive"))
      (node (ref "VCA2(RIGHT)") (pin "4") (pinfunction "SYM_4") (pintype "passive"))
    )
    (net (code "221") (name "SYM3") (class "Default")
      (node (ref "R44") (pin "1") (pinfunction "1_1") (pintype "passive"))
      (node (ref "R63") (pin "2") (pinfunction "2_2") (pintype "passive"))
      (node (ref "STAGE(LEFT)") (pin "4") (pinfunction "SYM_4") (pintype "passive"))
    )
    (net (code "222") (name "SYM4") (class "Default")
      (node (ref "R64") (pin "1") (pinfunction "1_1") (pintype "passive"))
      (node (ref "R66") (pin "2") (pinfunction "2_2") (pintype "passive"))
      (node (ref "STAGE(RIGHT)") (pin "4") (pinfunction "SYM_4") (pintype "passive"))
    )
    (net (code "223") (name "TD_N") (class "Default")
      (node (ref "IC13") (pin "4") (pinfunction "I/O3_4") (pintype "bidirectional"))
      (node (ref "IC6") (pin "20") (pinfunction "TXN_20") (pintype "bidirectional"))
      (node (ref "R80") (pin "1") (pinfunction "1_1") (pintype "passive"))
      (node (ref "T1") (pin "3") (pinfunction "TD-_3") (pintype "bidirectional"))
    )
    (net (code "224") (name "TD_P") (class "Default")
      (node (ref "IC13") (pin "3") (pinfunction "I/O2_3") (pintype "bidirectional"))
      (node (ref "IC6") (pin "21") (pinfunction "TXP_21") (pintype "bidirectional"))
      (node (ref "R79") (pin "1") (pinfunction "1_1") (pintype "passive"))
      (node (ref "T1") (pin "1") (pinfunction "TD+_1") (pintype "bidirectional"))
    )
    (net (code "225") (name "USART3_RX") (class "Default")
      (node (ref "IC10") (pin "77") (pinfunction "PD8_77") (pintype "bidirectional"))
    )
    (net (code "226") (name "USART3_TX") (class "Default")
      (node (ref "IC10") (pin "78") (pinfunction "PD9_78") (pintype "bidirectional"))
    )
    (net (code "227") (name "USART6_RX") (class "Default")
      (node (ref "DISPLAY") (pin "2") (pinfunction "2_2") (pintype "bidirectional"))
      (node (ref "IC10") (pin "97") (pinfunction "PC7_97") (pintype "bidirectional"))
    )
    (net (code "228") (name "USART6_TX") (class "Default")
      (node (ref "DISPLAY") (pin "1") (pinfunction "1_1") (pintype "bidirectional"))
      (node (ref "IC10") (pin "96") (pinfunction "PC6_96") (pintype "bidirectional"))
    )
    (net (code "229") (name "USB_ID") (class "Default")
      (node (ref "IC10") (pin "102") (pinfunction "PA10_102") (pintype "bidirectional"))
    )
    (net (code "230") (name "USB_N") (class "Default")
      (node (ref "IC10") (pin "103") (pinfunction "PA11_103") (pintype "bidirectional"))
      (node (ref "IC12") (pin "3") (pinfunction "3_3") (pintype "bidirectional"))
      (node (ref "X1") (pin "2") (pinfunction "2_2") (pintype "bidirectional"))
    )
    (net (code "231") (name "USB_OVERCURRENT") (class "Default")
      (node (ref "IC10") (pin "92") (pinfunction "PG7_92") (pintype "bidirectional"))
    )
    (net (code "232") (name "USB_P") (class "Default")
      (node (ref "IC10") (pin "104") (pinfunction "PA12_104") (pintype "bidirectional"))
      (node (ref "IC12") (pin "6") (pinfunction "6_6") (pintype "bidirectional"))
      (node (ref "X1") (pin "3") (pinfunction "3_3") (pintype "bidirectional"))
    )
    (net (code "233") (name "USB_POWERSWITCHON") (class "Default")
      (node (ref "IC10") (pin "91") (pinfunction "PG6_91") (pintype "bidirectional"))
    )
    (net (code "234") (name "USB_SOF") (class "Default")
      (node (ref "IC10") (pin "100") (pinfunction "PA8_100") (pintype "bidirectional"))
    )
    (net (code "235") (name "USB_VBUS") (class "Default")
      (node (ref "IC12") (pin "1") (pinfunction "1_1") (pintype "bidirectional"))
      (node (ref "R19") (pin "2") (pinfunction "2_2") (pintype "passive"))
      (node (ref "X1") (pin "1") (pinfunction "1_1") (pintype "bidirectional"))
    )
    (net (code "236") (name "V+") (class "Default")
      (node (ref "ANALOG_VOLT") (pin "1") (pinfunction "1_1") (pintype "bidirectional"))
      (node (ref "C104") (pin "1") (pinfunction "1_1") (pintype "passive"))
      (node (ref "C12") (pin "1") (pinfunction "1_1") (pintype "passive"))
      (node (ref "C21") (pin "1") (pinfunction "1_1") (pintype "passive"))
      (node (ref "C25") (pin "1") (pinfunction "1_1") (pintype "passive"))
      (node (ref "C27") (pin "1") (pinfunction "1_1") (pintype "passive"))
      (node (ref "C29") (pin "1") (pinfunction "1_1") (pintype "passive"))
      (node (ref "C3") (pin "1") (pinfunction "1_1") (pintype "passive"))
      (node (ref "C30") (pin "1") (pinfunction "1_1") (pintype "passive"))
      (node (ref "C4") (pin "1") (pinfunction "1_1") (pintype "passive"))
      (node (ref "C45") (pin "1") (pinfunction "1_1") (pintype "passive"))
      (node (ref "C46") (pin "1") (pinfunction "1_1") (pintype "passive"))
      (node (ref "C48") (pin "1") (pinfunction "1_1") (pintype "passive"))
      (node (ref "C50") (pin "1") (pinfunction "1_1") (pintype "passive"))
      (node (ref "C54") (pin "1") (pinfunction "1_1") (pintype "passive"))
      (node (ref "C6") (pin "1") (pinfunction "1_1") (pintype "passive"))
      (node (ref "C60") (pin "1") (pinfunction "1_1") (pintype "passive"))
      (node (ref "C62") (pin "1") (pinfunction "1_1") (pintype "passive"))
      (node (ref "C63") (pin "1") (pinfunction "1_1") (pintype "passive"))
      (node (ref "C8") (pin "1") (pinfunction "1_1") (pintype "passive"))
      (node (ref "C95") (pin "1") (pinfunction "1_1") (pintype "passive"))
      (node (ref "C97") (pin "1") (pinfunction "1_1") (pintype "passive"))
      (node (ref "IC1") (pin "8") (pinfunction "V+_8") (pintype "power_in"))
      (node (ref "IC14") (pin "8") (pinfunction "V+_8") (pintype "power_in"))
      (node (ref "IC15") (pin "8") (pinfunction "V+_8") (pintype "power_in"))
      (node (ref "IC16") (pin "8") (pinfunction "V+_8") (pintype "power_in"))
      (node (ref "IC4") (pin "8") (pinfunction "V+_8") (pintype "power_in"))
      (node (ref "IC5") (pin "8") (pinfunction "V+_8") (pintype "power_in"))
      (node (ref "IC7") (pin "8") (pinfunction "V+_8") (pintype "power_in"))
      (node (ref "IC8") (pin "8") (pinfunction "V+_8") (pintype "power_in"))
      (node (ref "IC9") (pin "8") (pinfunction "V+_8") (pintype "power_in"))
      (node (ref "IN_LEFT") (pin "7") (pinfunction "V+_7") (pintype "power_in"))
      (node (ref "IN_RIGHT") (pin "7") (pinfunction "V+_7") (pintype "power_in"))
      (node (ref "OUT_LEFT") (pin "6") (pinfunction "V+_6") (pintype "power_in"))
      (node (ref "OUT_RIGHT") (pin "6") (pinfunction "V+_6") (pintype "power_in"))
      (node (ref "R3") (pin "2") (pinfunction "2_2") (pintype "passive"))
      (node (ref "R67") (pin "2") (pinfunction "2_2") (pintype "passive"))
      (node (ref "R98") (pin "2") (pinfunction "2_2") (pintype "passive"))
      (node (ref "STAGE(LEFT)") (pin "7") (pinfunction "V+_7") (pintype "power_in"))
      (node (ref "STAGE(RIGHT)") (pin "7") (pinfunction "V+_7") (pintype "power_in"))
      (node (ref "U4") (pin "7") (pinfunction "V+_7") (pintype "power_in"))
      (node (ref "U6") (pin "7") (pinfunction "V+_7") (pintype "power_in"))
      (node (ref "U7") (pin "7") (pinfunction "V+_7") (pintype "power_in"))
      (node (ref "U8") (pin "7") (pinfunction "V+_7") (pintype "power_in"))
      (node (ref "VCA1(LEFT)") (pin "7") (pinfunction "V+_7") (pintype "power_in"))
      (node (ref "VCA2(RIGHT)") (pin "7") (pinfunction "V+_7") (pintype "power_in"))
    )
    (net (code "237") (name "V-") (class "Default")
      (node (ref "ANALOG_VOLT") (pin "2") (pinfunction "2_2") (pintype "bidirectional"))
      (node (ref "C1") (pin "1") (pinfunction "1_1") (pintype "passive"))
      (node (ref "C11") (pin "1") (pinfunction "1_1") (pintype "passive"))
      (node (ref "C13") (pin "1") (pinfunction "1_1") (pintype "passive"))
      (node (ref "C2") (pin "1") (pinfunction "1_1") (pintype "passive"))
      (node (ref "C20") (pin "1") (pinfunction "1_1") (pintype "passive"))
      (node (ref "C23") (pin "1") (pinfunction "1_1") (pintype "passive"))
      (node (ref "C26") (pin "1") (pinfunction "1_1") (pintype "passive"))
      (node (ref "C28") (pin "1") (pinfunction "1_1") (pintype "passive"))
      (node (ref "C35") (pin "1") (pinfunction "1_1") (pintype "passive"))
      (node (ref "C49") (pin "1") (pinfunction "1_1") (pintype "passive"))
      (node (ref "C5") (pin "1") (pinfunction "1_1") (pintype "passive"))
      (node (ref "C53") (pin "1") (pinfunction "1_1") (pintype "passive"))
      (node (ref "C57") (pin "1") (pinfunction "1_1") (pintype "passive"))
      (node (ref "C68") (pin "1") (pinfunction "1_1") (pintype "passive"))
      (node (ref "C7") (pin "1") (pinfunction "1_1") (pintype "passive"))
      (node (ref "C96") (pin "1") (pinfunction "1_1") (pintype "passive"))
      (node (ref "C98") (pin "1") (pinfunction "1_1") (pintype "passive"))
      (node (ref "IC1") (pin "4") (pinfunction "V-_4") (pintype "power_in"))
      (node (ref "IC14") (pin "4") (pinfunction "V-_4") (pintype "power_in"))
      (node (ref "IC15") (pin "4") (pinfunction "V-_4") (pintype "power_in"))
      (node (ref "IC16") (pin "4") (pinfunction "V-_4") (pintype "power_in"))
      (node (ref "IC4") (pin "4") (pinfunction "V-_4") (pintype "power_in"))
      (node (ref "IC5") (pin "4") (pinfunction "V-_4") (pintype "power_in"))
      (node (ref "IC7") (pin "4") (pinfunction "V-_4") (pintype "power_in"))
      (node (ref "IC8") (pin "4") (pinfunction "V-_4") (pintype "power_in"))
      (node (ref "IC9") (pin "4") (pinfunction "V-_4") (pintype "power_in"))
      (node (ref "IN_LEFT") (pin "4") (pinfunction "V-_4") (pintype "power_in"))
      (node (ref "IN_RIGHT") (pin "4") (pinfunction "V-_4") (pintype "power_in"))
      (node (ref "OUT_LEFT") (pin "5") (pinfunction "V-_5") (pintype "power_in"))
      (node (ref "OUT_RIGHT") (pin "5") (pinfunction "V-_5") (pintype "power_in"))
      (node (ref "R2") (pin "1") (pinfunction "1_1") (pintype "passive"))
      (node (ref "R31") (pin "1") (pinfunction "1_1") (pintype "passive"))
      (node (ref "R32") (pin "1") (pinfunction "1_1") (pintype "passive"))
      (node (ref "R40") (pin "1") (pinfunction "1_1") (pintype "passive"))
      (node (ref "R43") (pin "1") (pinfunction "1_1") (pintype "passive"))
      (node (ref "R50") (pin "1") (pinfunction "1_1") (pintype "passive"))
      (node (ref "R51") (pin "1") (pinfunction "1_1") (pintype "passive"))
      (node (ref "R63") (pin "1") (pinfunction "1_1") (pintype "passive"))
      (node (ref "R66") (pin "1") (pinfunction "1_1") (pintype "passive"))
      (node (ref "R97") (pin "1") (pinfunction "1_1") (pintype "passive"))
      (node (ref "U4") (pin "4") (pinfunction "V-_4") (pintype "power_in"))
      (node (ref "U6") (pin "4") (pinfunction "V-_4") (pintype "power_in"))
      (node (ref "U7") (pin "4") (pinfunction "V-_4") (pintype "power_in"))
      (node (ref "U8") (pin "4") (pinfunction "V-_4") (pintype "power_in"))
    )
    (net (code "238") (name "unconnected-(IC10-PA15-Pad110)") (class "Default")
      (node (ref "IC10") (pin "110") (pinfunction "PA15_110") (pintype "bidirectional"))
    )
    (net (code "239") (name "unconnected-(IC10-PB2-Pad48)") (class "Default")
      (node (ref "IC10") (pin "48") (pinfunction "PB2_48") (pintype "bidirectional"))
    )
    (net (code "240") (name "unconnected-(IC10-PB3-Pad133)") (class "Default")
      (node (ref "IC10") (pin "133") (pinfunction "PB3_133") (pintype "bidirectional"))
    )
    (net (code "241") (name "unconnected-(IC10-PB6-Pad136)") (class "Default")
      (node (ref "IC10") (pin "136") (pinfunction "PB6_136") (pintype "bidirectional"))
    )
    (net (code "242") (name "unconnected-(IC10-PB8-Pad139)") (class "Default")
      (node (ref "IC10") (pin "139") (pinfunction "PB8_139") (pintype "bidirectional"))
    )
    (net (code "243") (name "unconnected-(IC10-PB9-Pad140)") (class "Default")
      (node (ref "IC10") (pin "140") (pinfunction "PB9_140") (pintype "bidirectional"))
    )
    (net (code "244") (name "unconnected-(IC10-PB11-Pad70)") (class "Default")
      (node (ref "IC10") (pin "70") (pinfunction "PB11_70") (pintype "bidirectional"))
    )
    (net (code "245") (name "unconnected-(IC10-PB12-Pad73)") (class "Default")
      (node (ref "IC10") (pin "73") (pinfunction "PB12_73") (pintype "bidirectional"))
    )
    (net (code "246") (name "unconnected-(IC10-PB15-Pad76)") (class "Default")
      (node (ref "IC10") (pin "76") (pinfunction "PB15_76") (pintype "bidirectional"))
    )
    (net (code "247") (name "unconnected-(IC10-PC2-Pad28)") (class "Default")
      (node (ref "IC10") (pin "28") (pinfunction "PC2_28") (pintype "bidirectional"))
    )
    (net (code "248") (name "unconnected-(IC10-PC13-Pad7)") (class "Default")
      (node (ref "IC10") (pin "7") (pinfunction "PC13_7") (pintype "bidirectional"))
    )
    (net (code "249") (name "unconnected-(IC10-PD0-Pad114)") (class "Default")
      (node (ref "IC10") (pin "114") (pinfunction "PD0_114") (pintype "bidirectional"))
    )
    (net (code "250") (name "unconnected-(IC10-PD3-Pad117)") (class "Default")
      (node (ref "IC10") (pin "117") (pinfunction "PD3_117") (pintype "bidirectional"))
    )
    (net (code "251") (name "unconnected-(IC10-PD4-Pad118)") (class "Default")
      (node (ref "IC10") (pin "118") (pinfunction "PD4_118") (pintype "bidirectional"))
    )
    (net (code "252") (name "unconnected-(IC10-PD5-Pad119)") (class "Default")
      (node (ref "IC10") (pin "119") (pinfunction "PD5_119") (pintype "bidirectional"))
    )
    (net (code "253") (name "unconnected-(IC10-PD10-Pad79)") (class "Default")
      (node (ref "IC10") (pin "79") (pinfunction "PD10_79") (pintype "bidirectional"))
    )
    (net (code "254") (name "unconnected-(IC10-PD11-Pad80)") (class "Default")
      (node (ref "IC10") (pin "80") (pinfunction "PD11_80") (pintype "bidirectional"))
    )
    (net (code "255") (name "unconnected-(IC10-PD12-Pad81)") (class "Default")
      (node (ref "IC10") (pin "81") (pinfunction "PD12_81") (pintype "bidirectional"))
    )
    (net (code "256") (name "unconnected-(IC10-PD13-Pad82)") (class "Default")
      (node (ref "IC10") (pin "82") (pinfunction "PD13_82") (pintype "bidirectional"))
    )
    (net (code "257") (name "unconnected-(IC10-PD14-Pad85)") (class "Default")
      (node (ref "IC10") (pin "85") (pinfunction "PD14_85") (pintype "bidirectional"))
    )
    (net (code "258") (name "unconnected-(IC10-PD15-Pad86)") (class "Default")
      (node (ref "IC10") (pin "86") (pinfunction "PD15_86") (pintype "bidirectional"))
    )
    (net (code "259") (name "unconnected-(IC10-PDR_ON-Pad143)") (class "Default")
      (node (ref "IC10") (pin "143") (pinfunction "PDR_ON_143") (pintype "bidirectional"))
    )
    (net (code "260") (name "unconnected-(IC10-PF0-Pad10)") (class "Default")
      (node (ref "IC10") (pin "10") (pinfunction "PF0_10") (pintype "bidirectional"))
    )
    (net (code "261") (name "unconnected-(IC10-PF1-Pad11)") (class "Default")
      (node (ref "IC10") (pin "11") (pinfunction "PF1_11") (pintype "bidirectional"))
    )
    (net (code "262") (name "unconnected-(IC10-PF2-Pad12)") (class "Default")
      (node (ref "IC10") (pin "12") (pinfunction "PF2_12") (pintype "bidirectional"))
    )
    (net (code "263") (name "unconnected-(IC10-PF3-Pad13)") (class "Default")
      (node (ref "IC10") (pin "13") (pinfunction "PF3_13") (pintype "bidirectional"))
    )
    (net (code "264") (name "unconnected-(IC10-PF4-Pad14)") (class "Default")
      (node (ref "IC10") (pin "14") (pinfunction "PF4_14") (pintype "bidirectional"))
    )
    (net (code "265") (name "unconnected-(IC10-PF5-Pad15)") (class "Default")
      (node (ref "IC10") (pin "15") (pinfunction "PF5_15") (pintype "bidirectional"))
    )
    (net (code "266") (name "unconnected-(IC10-PF6-Pad18)") (class "Default")
      (node (ref "IC10") (pin "18") (pinfunction "PF6_18") (pintype "bidirectional"))
    )
    (net (code "267") (name "unconnected-(IC10-PF7-Pad19)") (class "Default")
      (node (ref "IC10") (pin "19") (pinfunction "PF7_19") (pintype "bidirectional"))
    )
    (net (code "268") (name "unconnected-(IC10-PF8-Pad20)") (class "Default")
      (node (ref "IC10") (pin "20") (pinfunction "PF8_20") (pintype "bidirectional"))
    )
    (net (code "269") (name "unconnected-(IC10-PF10-Pad22)") (class "Default")
      (node (ref "IC10") (pin "22") (pinfunction "PF10_22") (pintype "bidirectional"))
    )
    (net (code "270") (name "unconnected-(IC10-PF11-Pad49)") (class "Default")
      (node (ref "IC10") (pin "49") (pinfunction "PF11_49") (pintype "bidirectional"))
    )
    (net (code "271") (name "unconnected-(IC10-PF12-Pad50)") (class "Default")
      (node (ref "IC10") (pin "50") (pinfunction "PF12_50") (pintype "bidirectional"))
    )
    (net (code "272") (name "unconnected-(IC10-PF13-Pad53)") (class "Default")
      (node (ref "IC10") (pin "53") (pinfunction "PF13_53") (pintype "bidirectional"))
    )
    (net (code "273") (name "unconnected-(IC10-PF14-Pad54)") (class "Default")
      (node (ref "IC10") (pin "54") (pinfunction "PF14_54") (pintype "bidirectional"))
    )
    (net (code "274") (name "unconnected-(IC10-PF15-Pad55)") (class "Default")
      (node (ref "IC10") (pin "55") (pinfunction "PF15_55") (pintype "bidirectional"))
    )
    (net (code "275") (name "unconnected-(IC10-PG4-Pad89)") (class "Default")
      (node (ref "IC10") (pin "89") (pinfunction "PG4_89") (pintype "bidirectional"))
    )
    (net (code "276") (name "unconnected-(IC10-PG5-Pad90)") (class "Default")
      (node (ref "IC10") (pin "90") (pinfunction "PG5_90") (pintype "bidirectional"))
    )
    (net (code "277") (name "unconnected-(IC10-PG8-Pad93)") (class "Default")
      (node (ref "IC10") (pin "93") (pinfunction "PG8_93") (pintype "bidirectional"))
    )
    (net (code "278") (name "unconnected-(IC10-PG14-Pad129)") (class "Default")
      (node (ref "IC10") (pin "129") (pinfunction "PG14_129") (pintype "bidirectional"))
    )
    (net (code "279") (name "unconnected-(IC11-AGND_3-Pad35)") (class "Default")
      (node (ref "IC11") (pin "35") (pinfunction "AGND_3_35") (pintype "bidirectional"))
    )
    (net (code "280") (name "unconnected-(IC11-~{STBY}-Pad7)") (class "Default")
      (node (ref "IC11") (pin "7") (pinfunction "~{STBY}_7") (pintype "bidirectional"))
    )
    (net (code "281") (name "unconnected-(IC12-Pad4)") (class "Default")
      (node (ref "IC12") (pin "4") (pinfunction "4_4") (pintype "bidirectional"))
    )
    (net (code "282") (name "unconnected-(J1-Pad4)") (class "Default")
      (node (ref "J1") (pin "4") (pinfunction "4_4") (pintype "bidirectional"))
    )
    (net (code "283") (name "unconnected-(J1-Pad5)") (class "Default")
      (node (ref "J1") (pin "5") (pinfunction "5_5") (pintype "bidirectional"))
    )
    (net (code "284") (name "unconnected-(K7C-O-PadQ2)") (class "Default")
      (node (ref "K7") (pin "Q2") (pinfunction "O_Q2") (pintype "passive"))
    )
    (net (code "285") (name "unconnected-(K7C-P-PadP2)") (class "Default")
      (node (ref "K7") (pin "P2") (pinfunction "P_P2") (pintype "passive"))
    )
    (net (code "286") (name "unconnected-(K7C-S-PadS2)") (class "Default")
      (node (ref "K7") (pin "S2") (pinfunction "S_S2") (pintype "passive"))
    )
    (net (code "287") (name "unconnected-(K8C-O-PadQ2)") (class "Default")
      (node (ref "K8") (pin "Q2") (pinfunction "O_Q2") (pintype "passive"))
    )
    (net (code "288") (name "unconnected-(K8C-P-PadP2)") (class "Default")
      (node (ref "K8") (pin "P2") (pinfunction "P_P2") (pintype "passive"))
    )
    (net (code "289") (name "unconnected-(K8C-S-PadS2)") (class "Default")
      (node (ref "K8") (pin "S2") (pinfunction "S_S2") (pintype "passive"))
    )
    (net (code "290") (name "unconnected-(T1-NC_1-Pad4)") (class "Default")
      (node (ref "T1") (pin "4") (pinfunction "NC_1_4") (pintype "bidirectional"))
    )
    (net (code "291") (name "unconnected-(T1-NC_2-Pad5)") (class "Default")
      (node (ref "T1") (pin "5") (pinfunction "NC_2_5") (pintype "bidirectional"))
    )
    (net (code "292") (name "unconnected-(T1-NC_3-Pad10)") (class "Default")
      (node (ref "T1") (pin "10") (pinfunction "NC_3_10") (pintype "bidirectional"))
    )
    (net (code "293") (name "unconnected-(T1-NC_5-Pad13)") (class "Default")
      (node (ref "T1") (pin "13") (pinfunction "NC_5_13") (pintype "bidirectional"))
    )
    (net (code "294") (name "unconnected-(U12-IN7-Pad7)") (class "Default")
      (node (ref "U12") (pin "7") (pinfunction "IN7_7") (pintype "bidirectional"))
    )
    (net (code "295") (name "unconnected-(U12-OUT7-Pad10)") (class "Default")
      (node (ref "U12") (pin "10") (pinfunction "OUT7_10") (pintype "bidirectional"))
    )
  )
)
